# v1_0.net
KiCad netlist of a schematic drawn in EAGLE
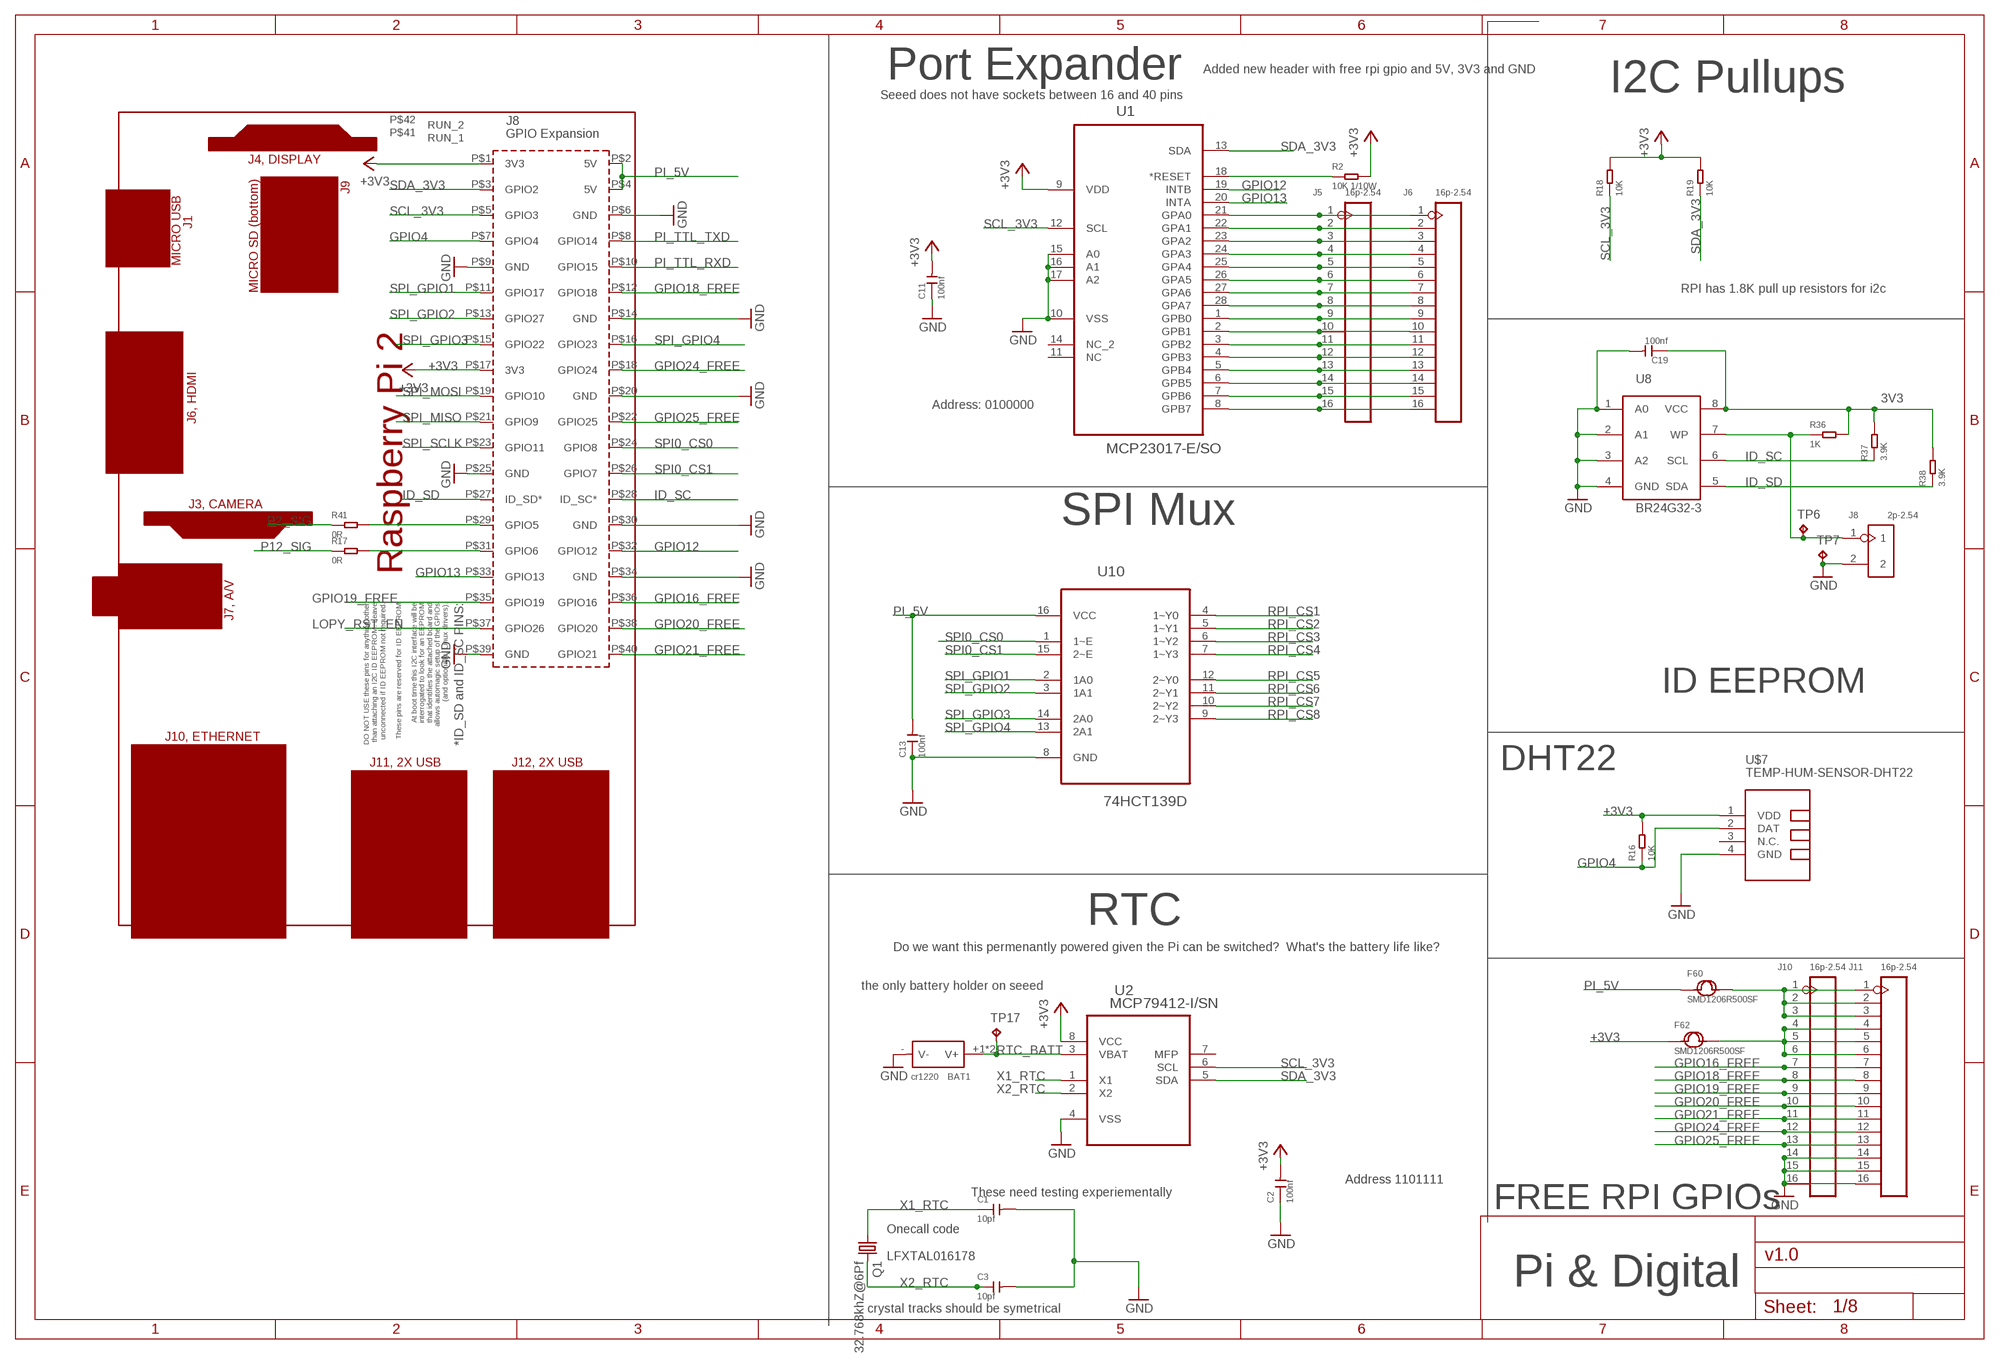
[diagram p0: schematic, sheet 1]
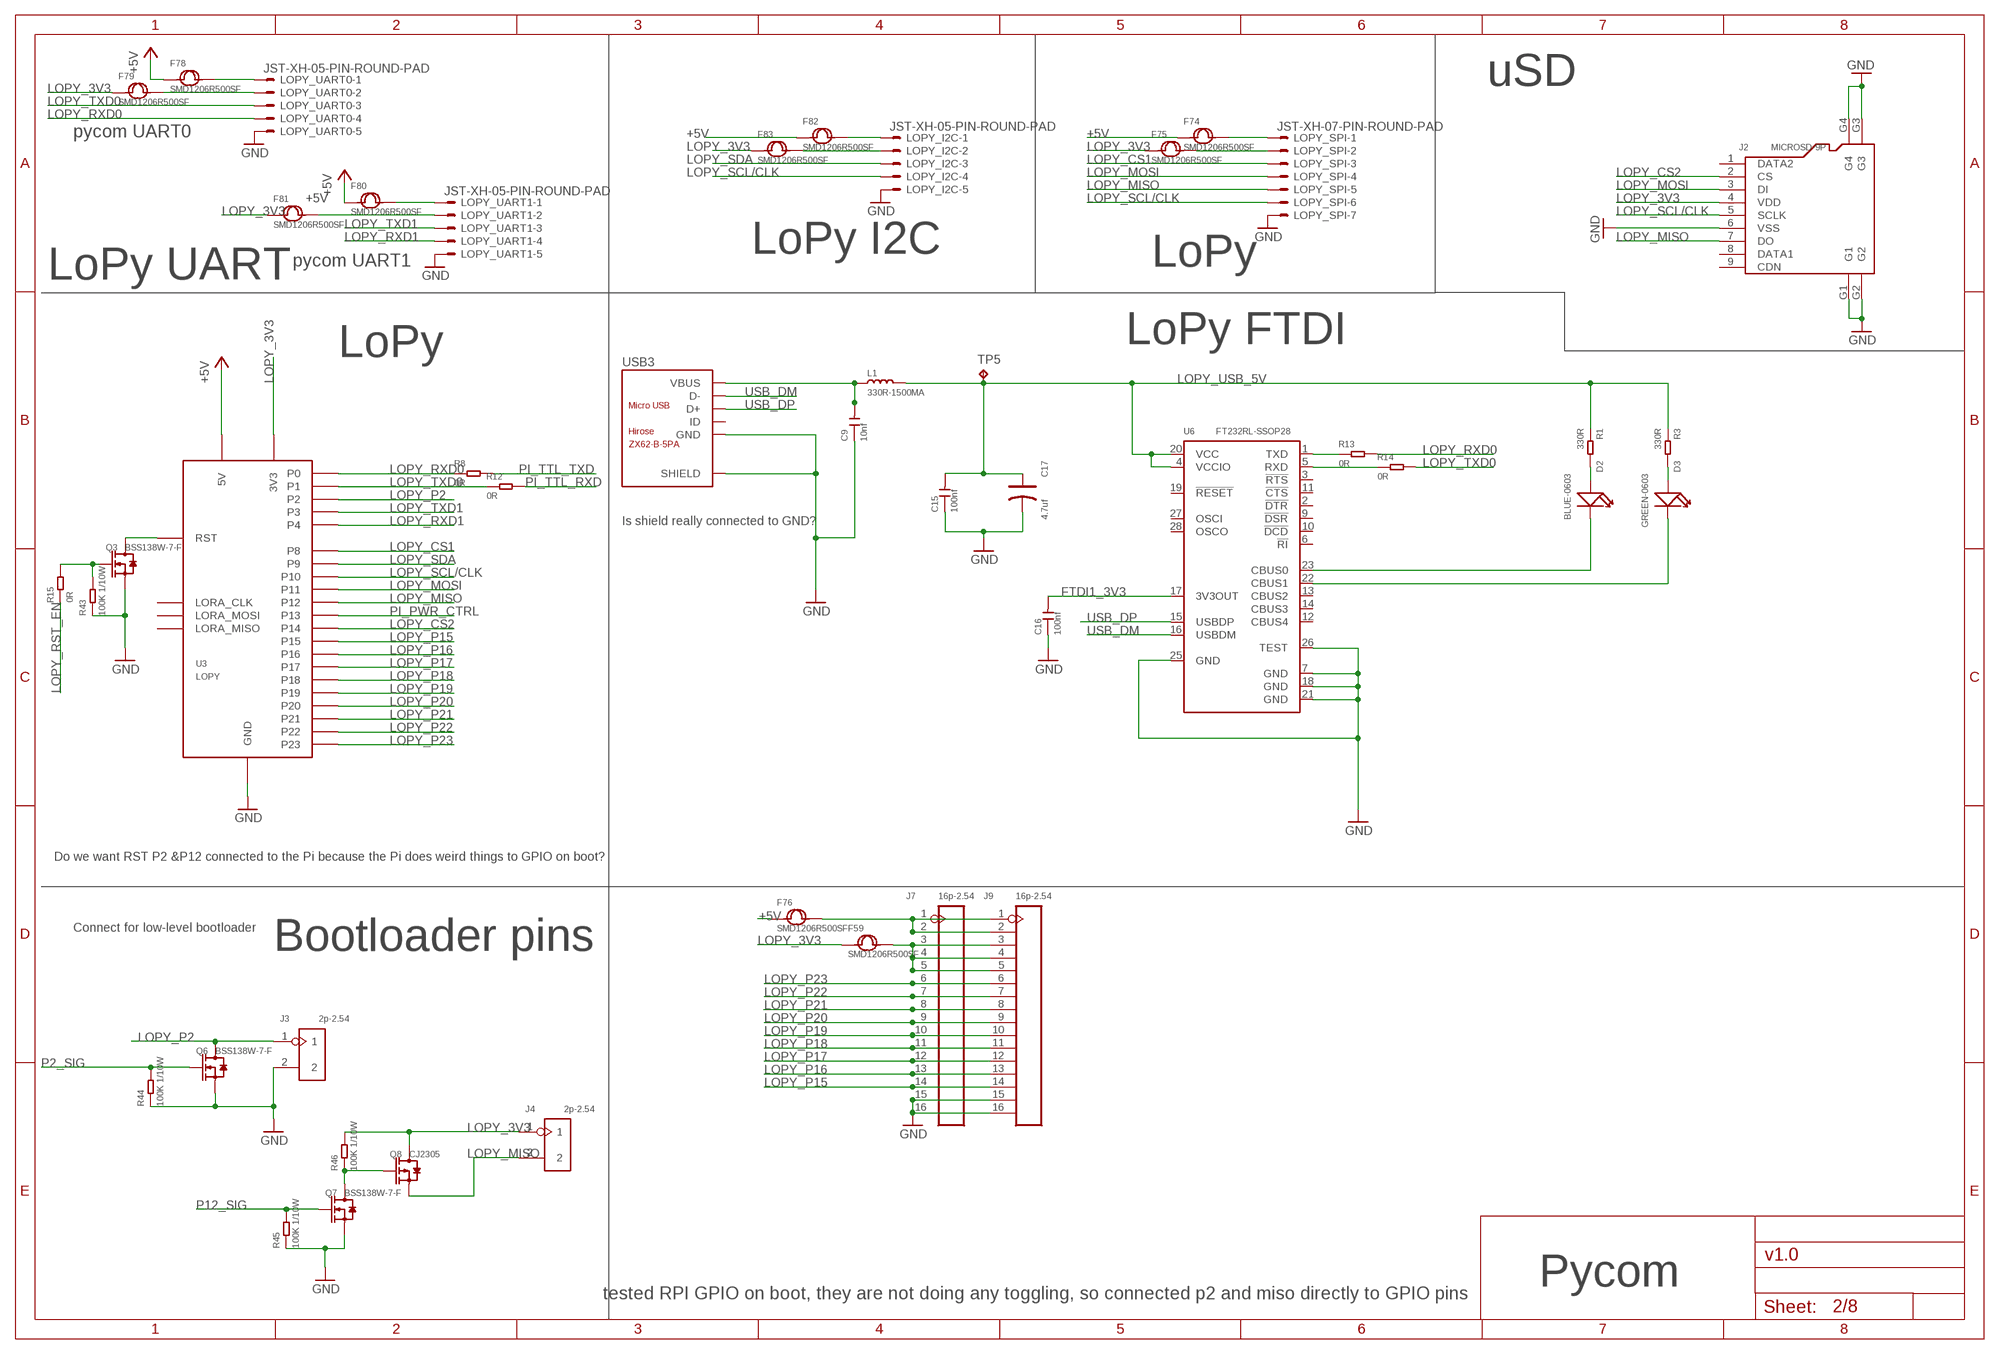
[diagram p1: schematic, sheet 2]
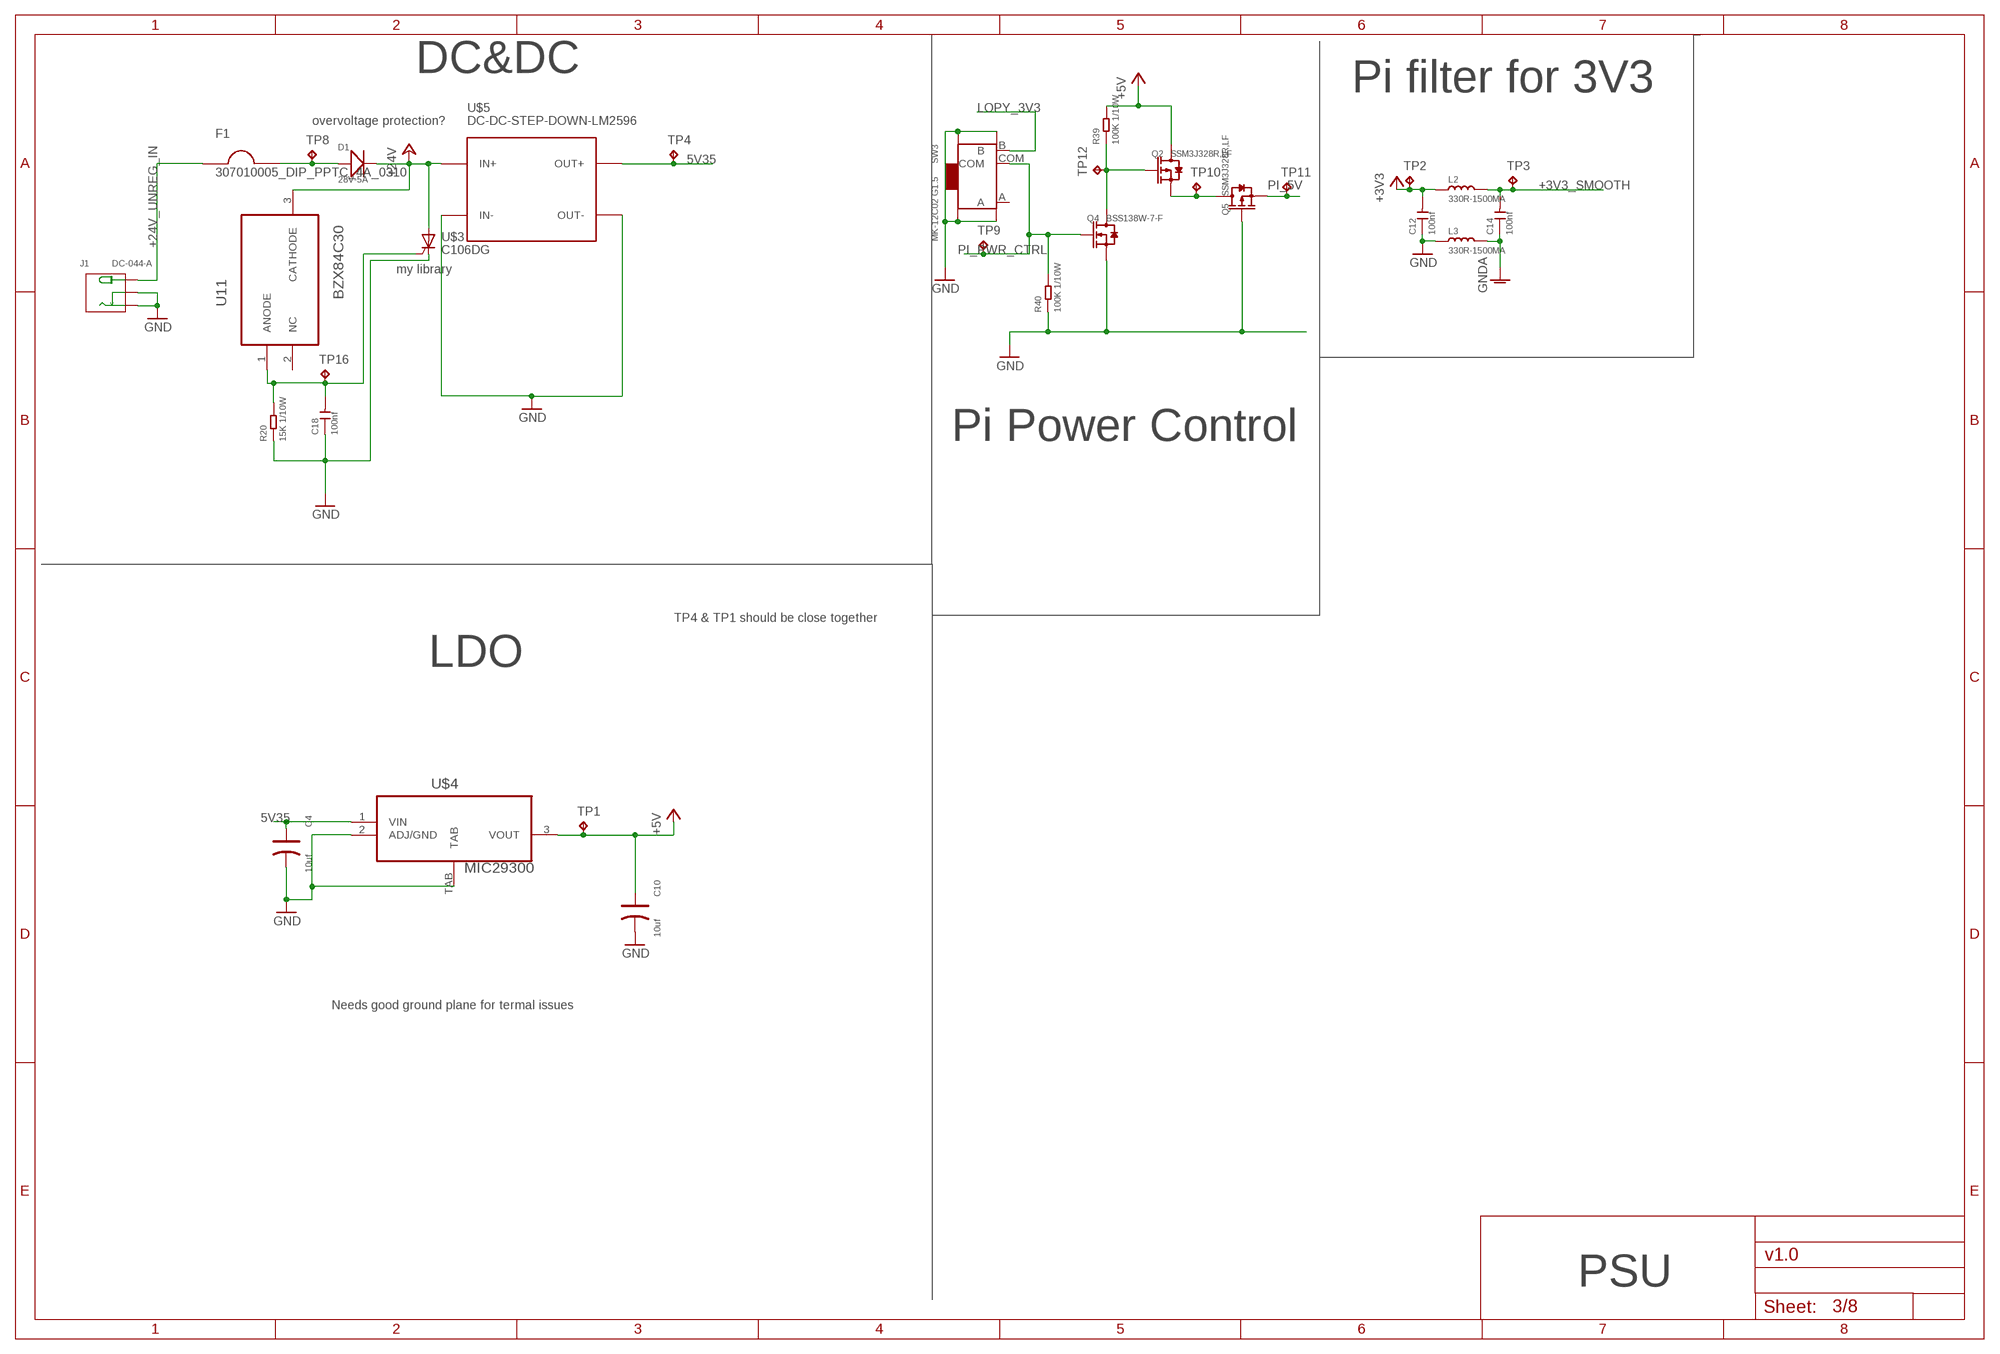
[diagram p2: schematic, sheet 3]
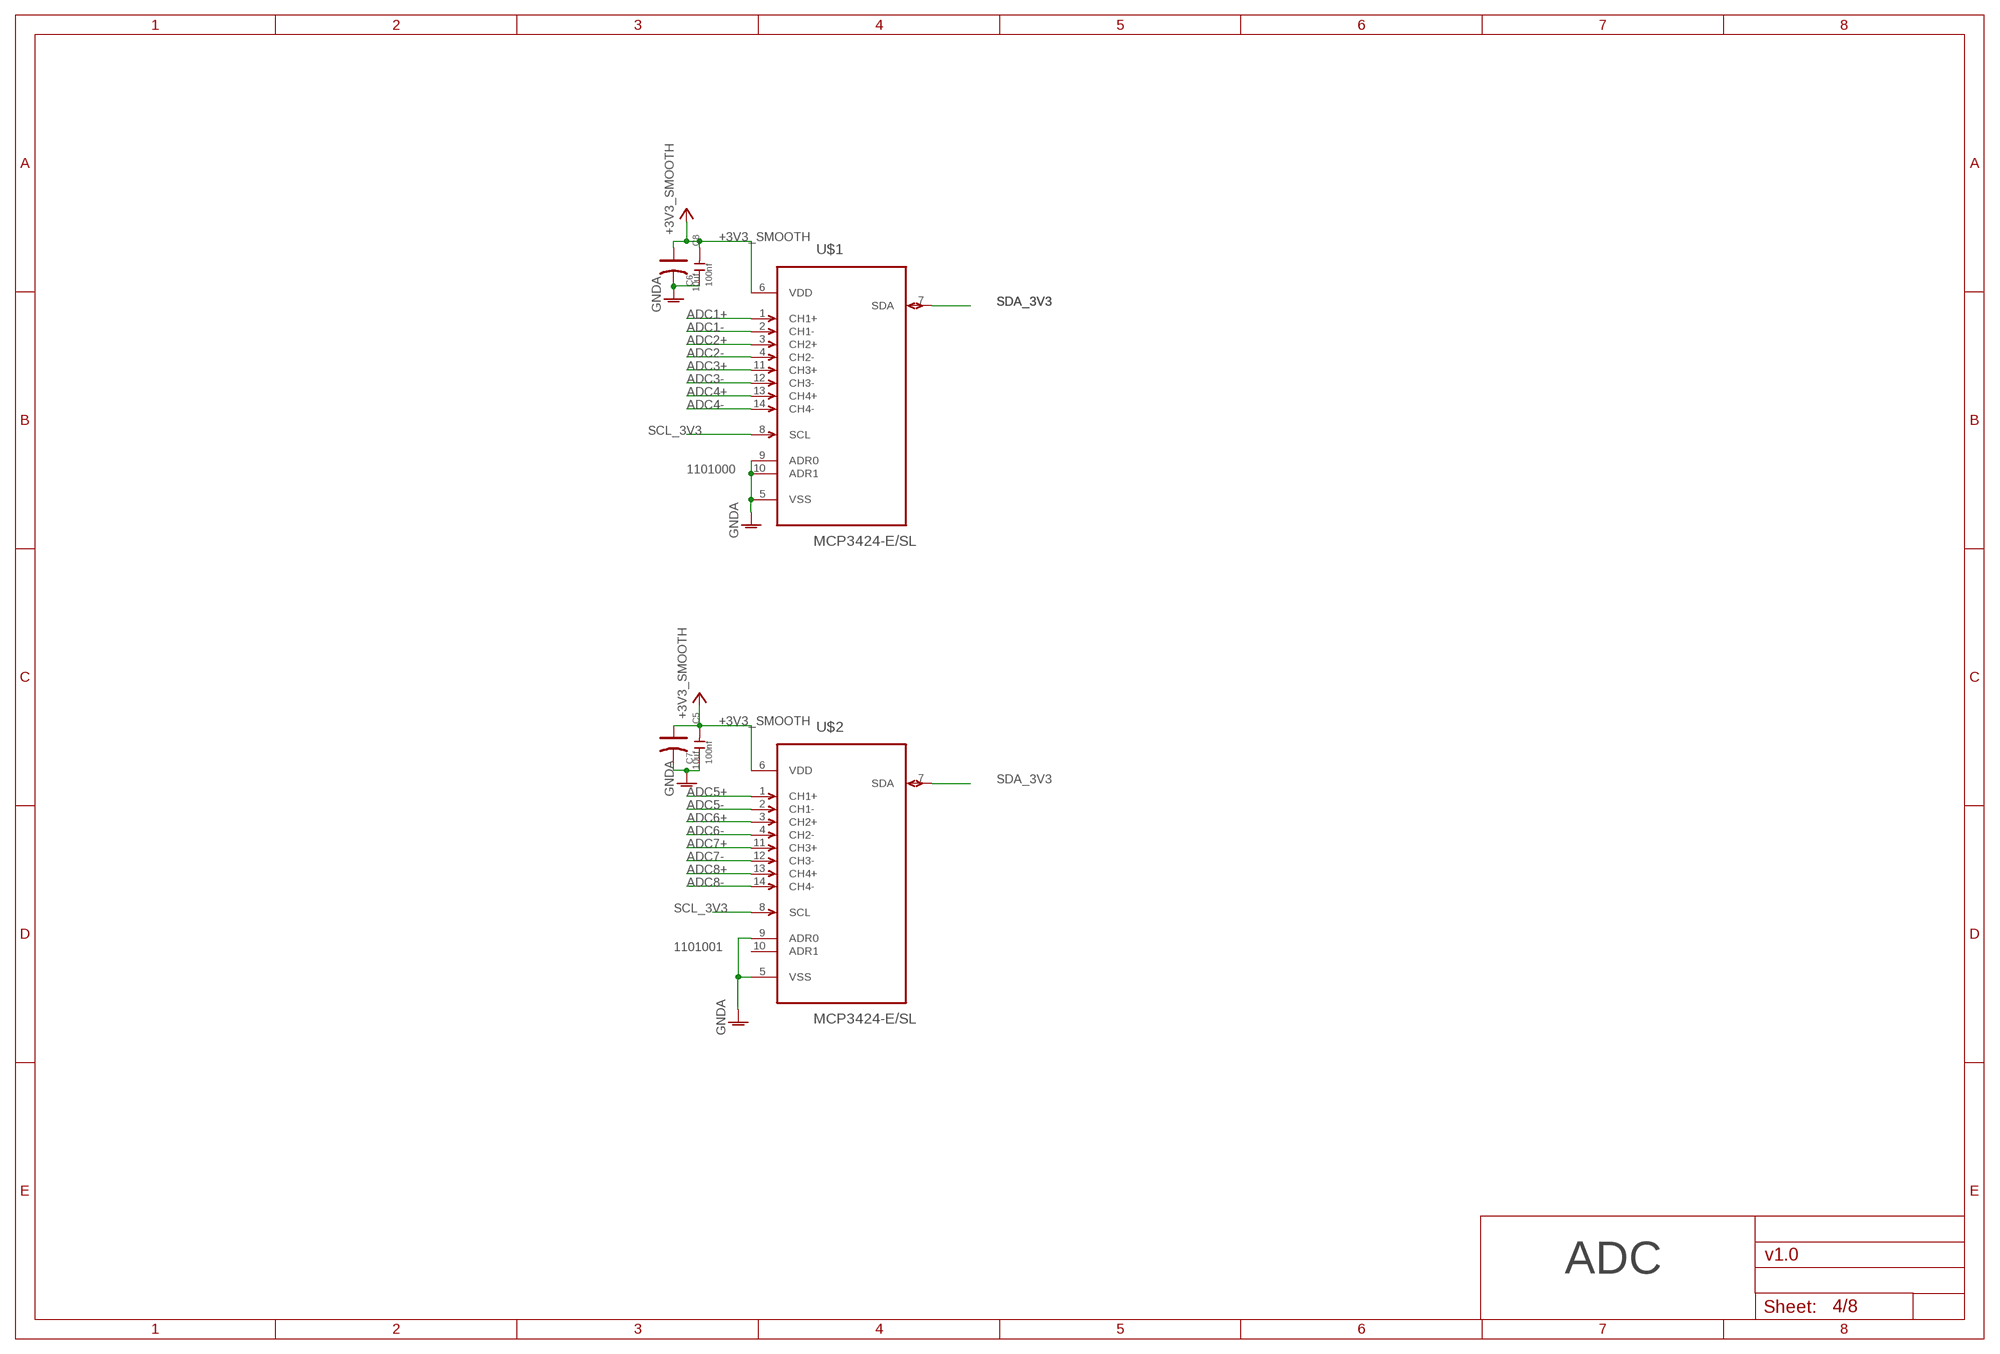
[diagram p3: schematic, sheet 4]
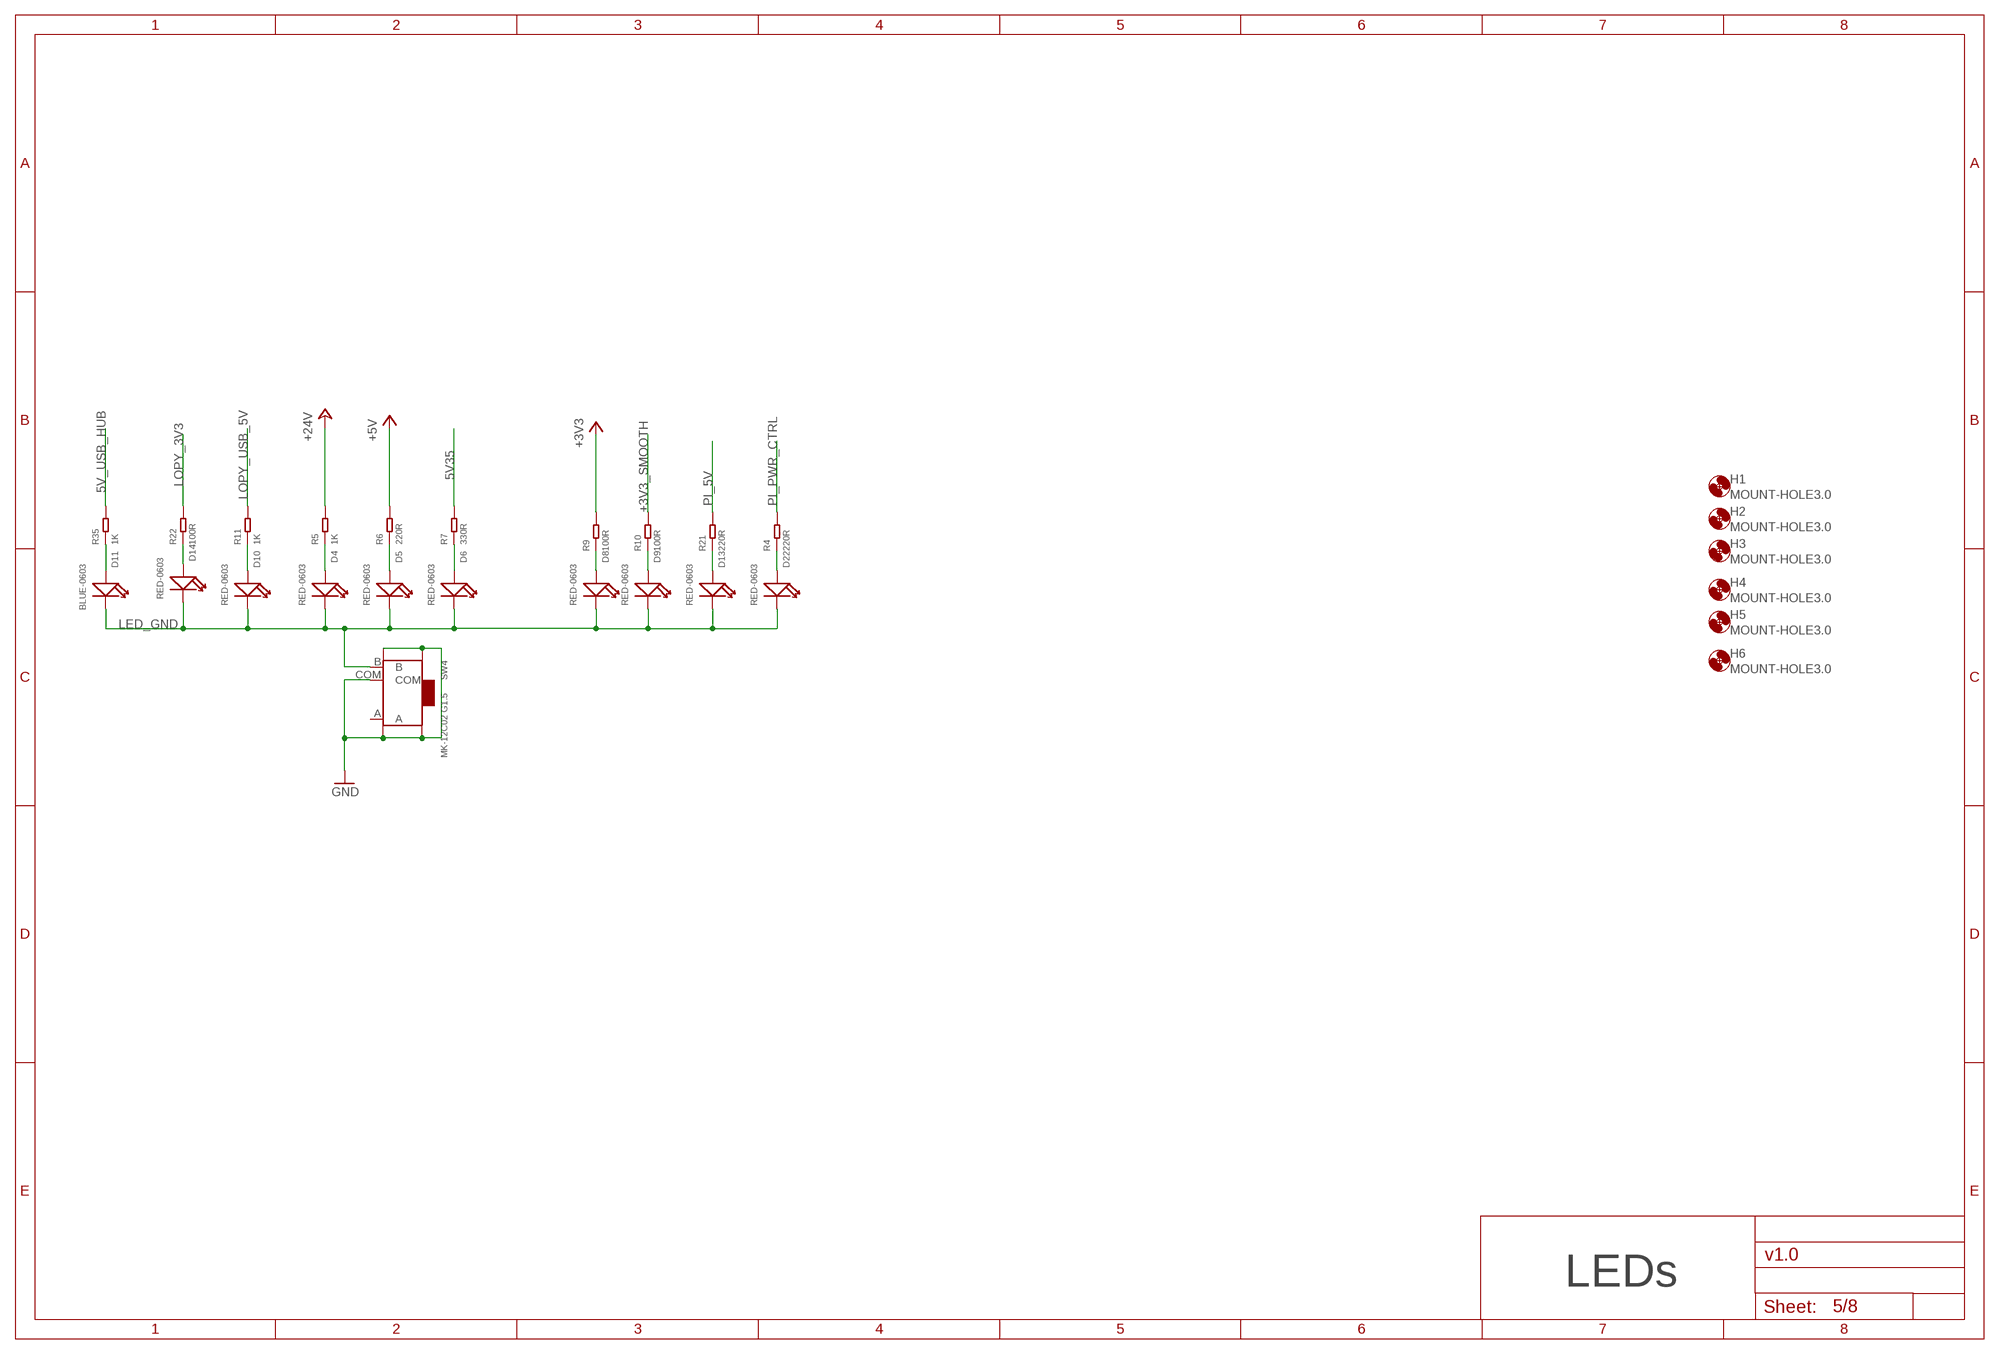
[diagram p4: schematic, sheet 5]
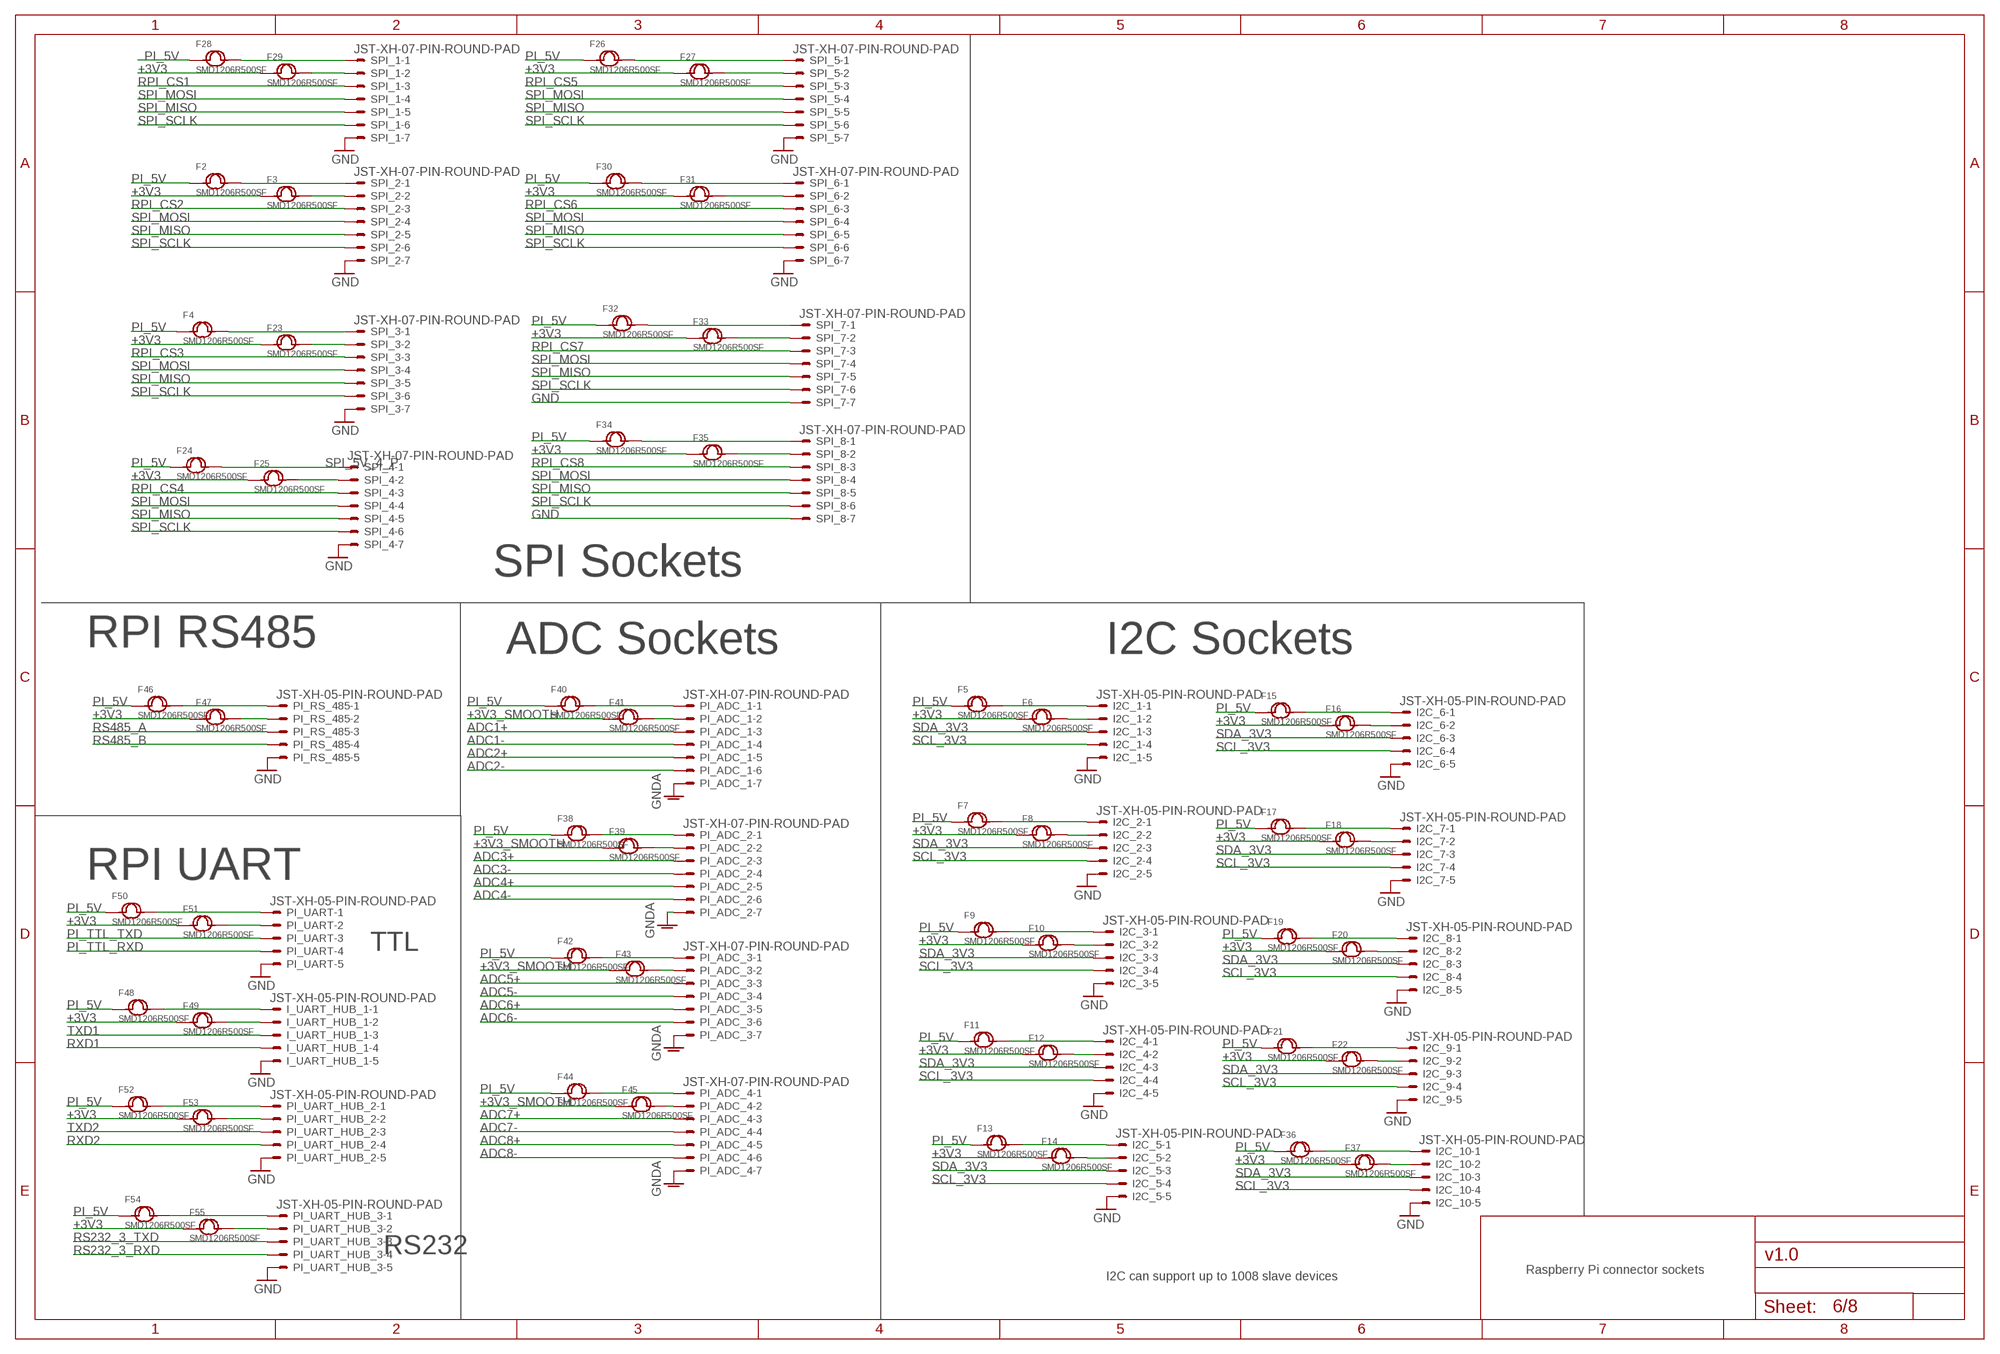
[diagram p5: schematic, sheet 6]
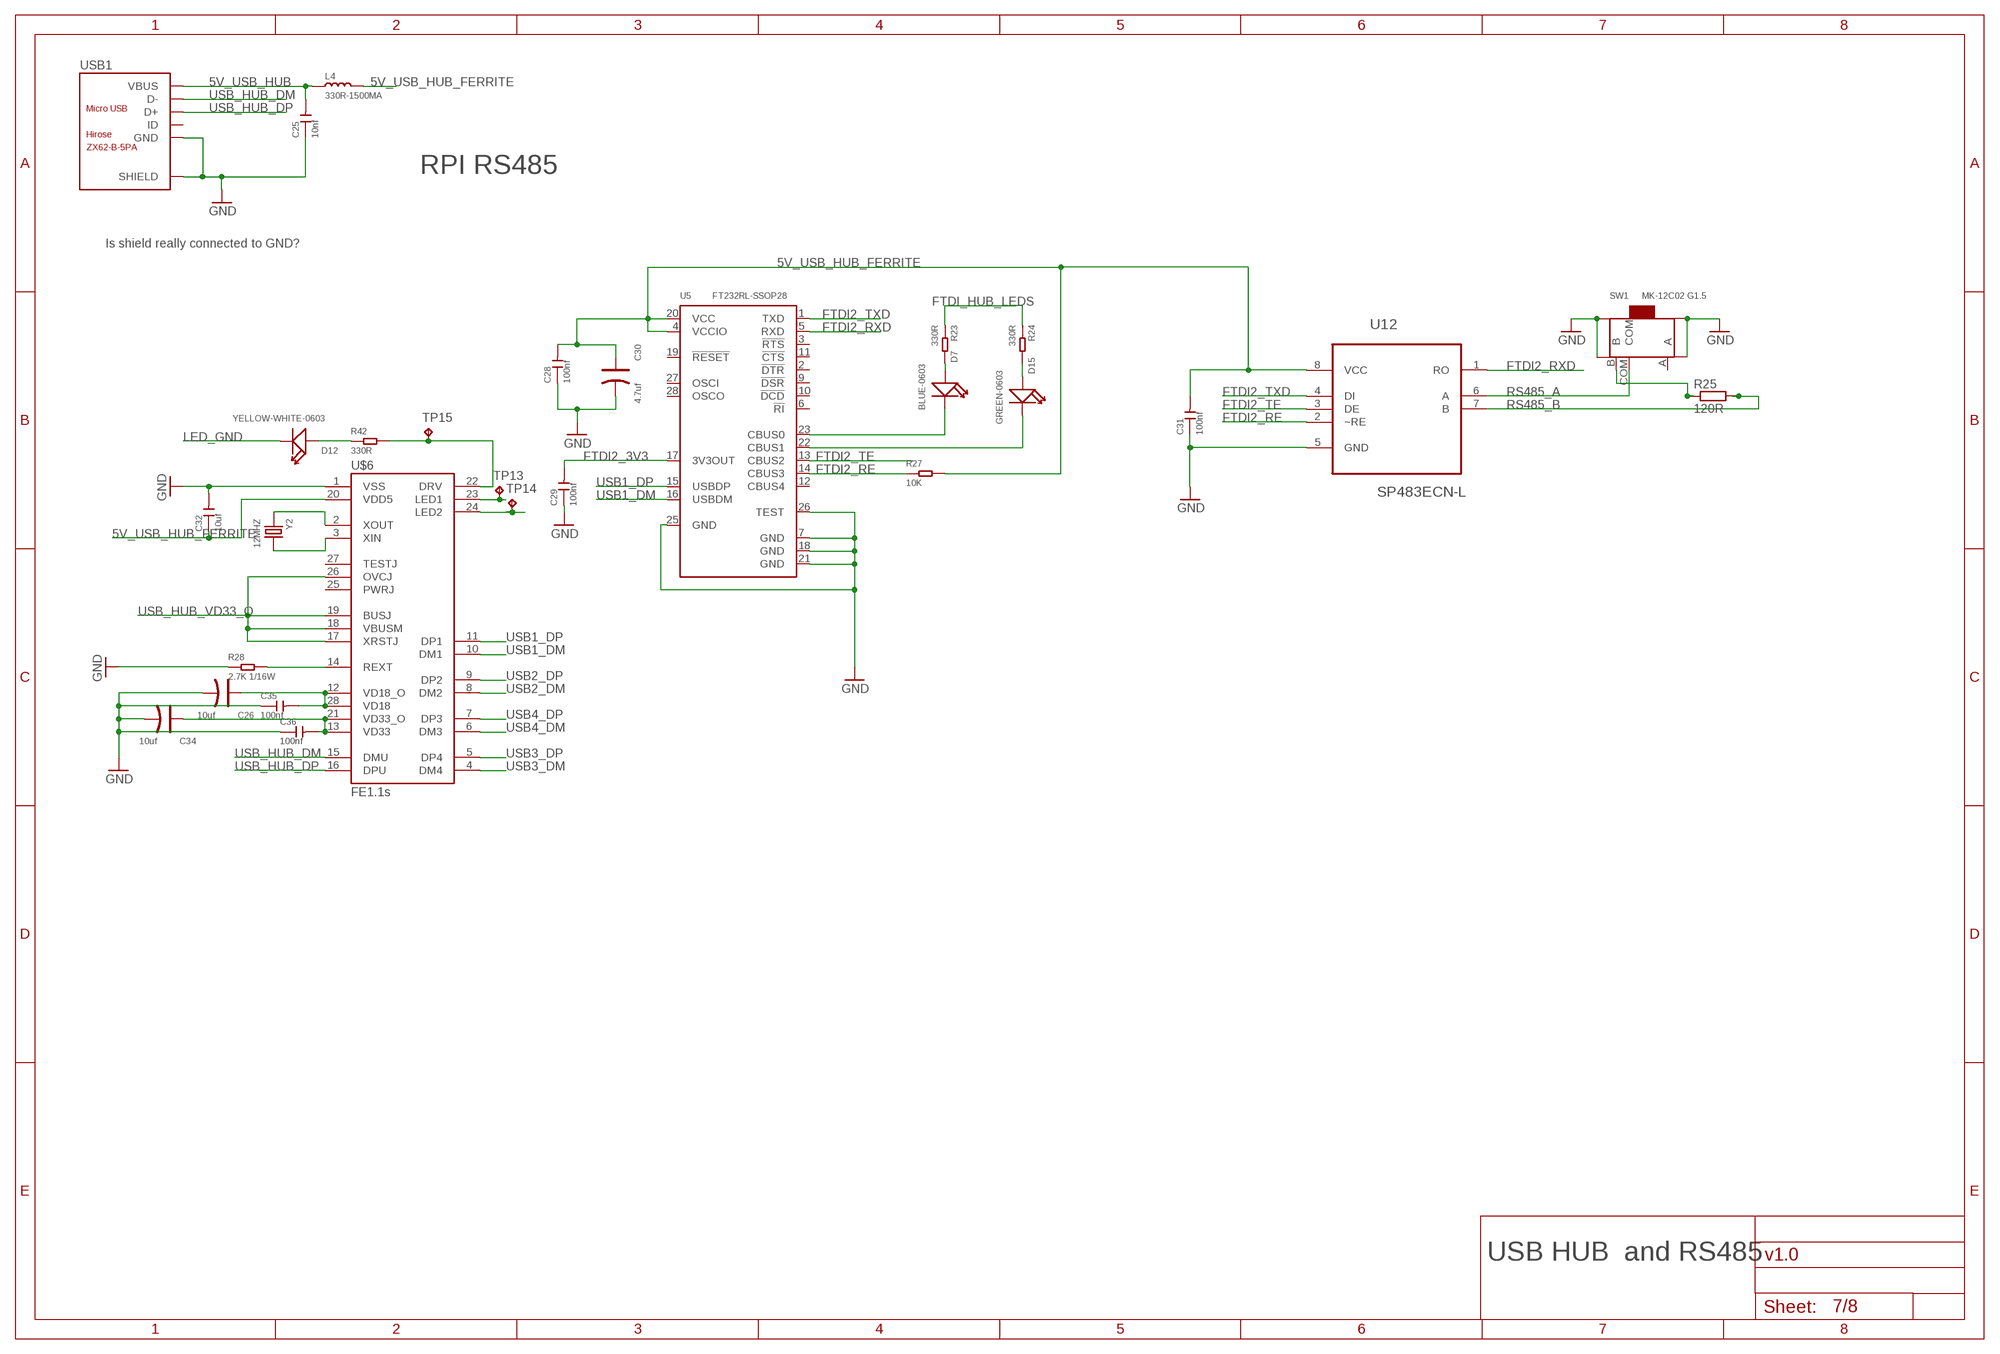
[diagram p6: schematic, sheet 7]
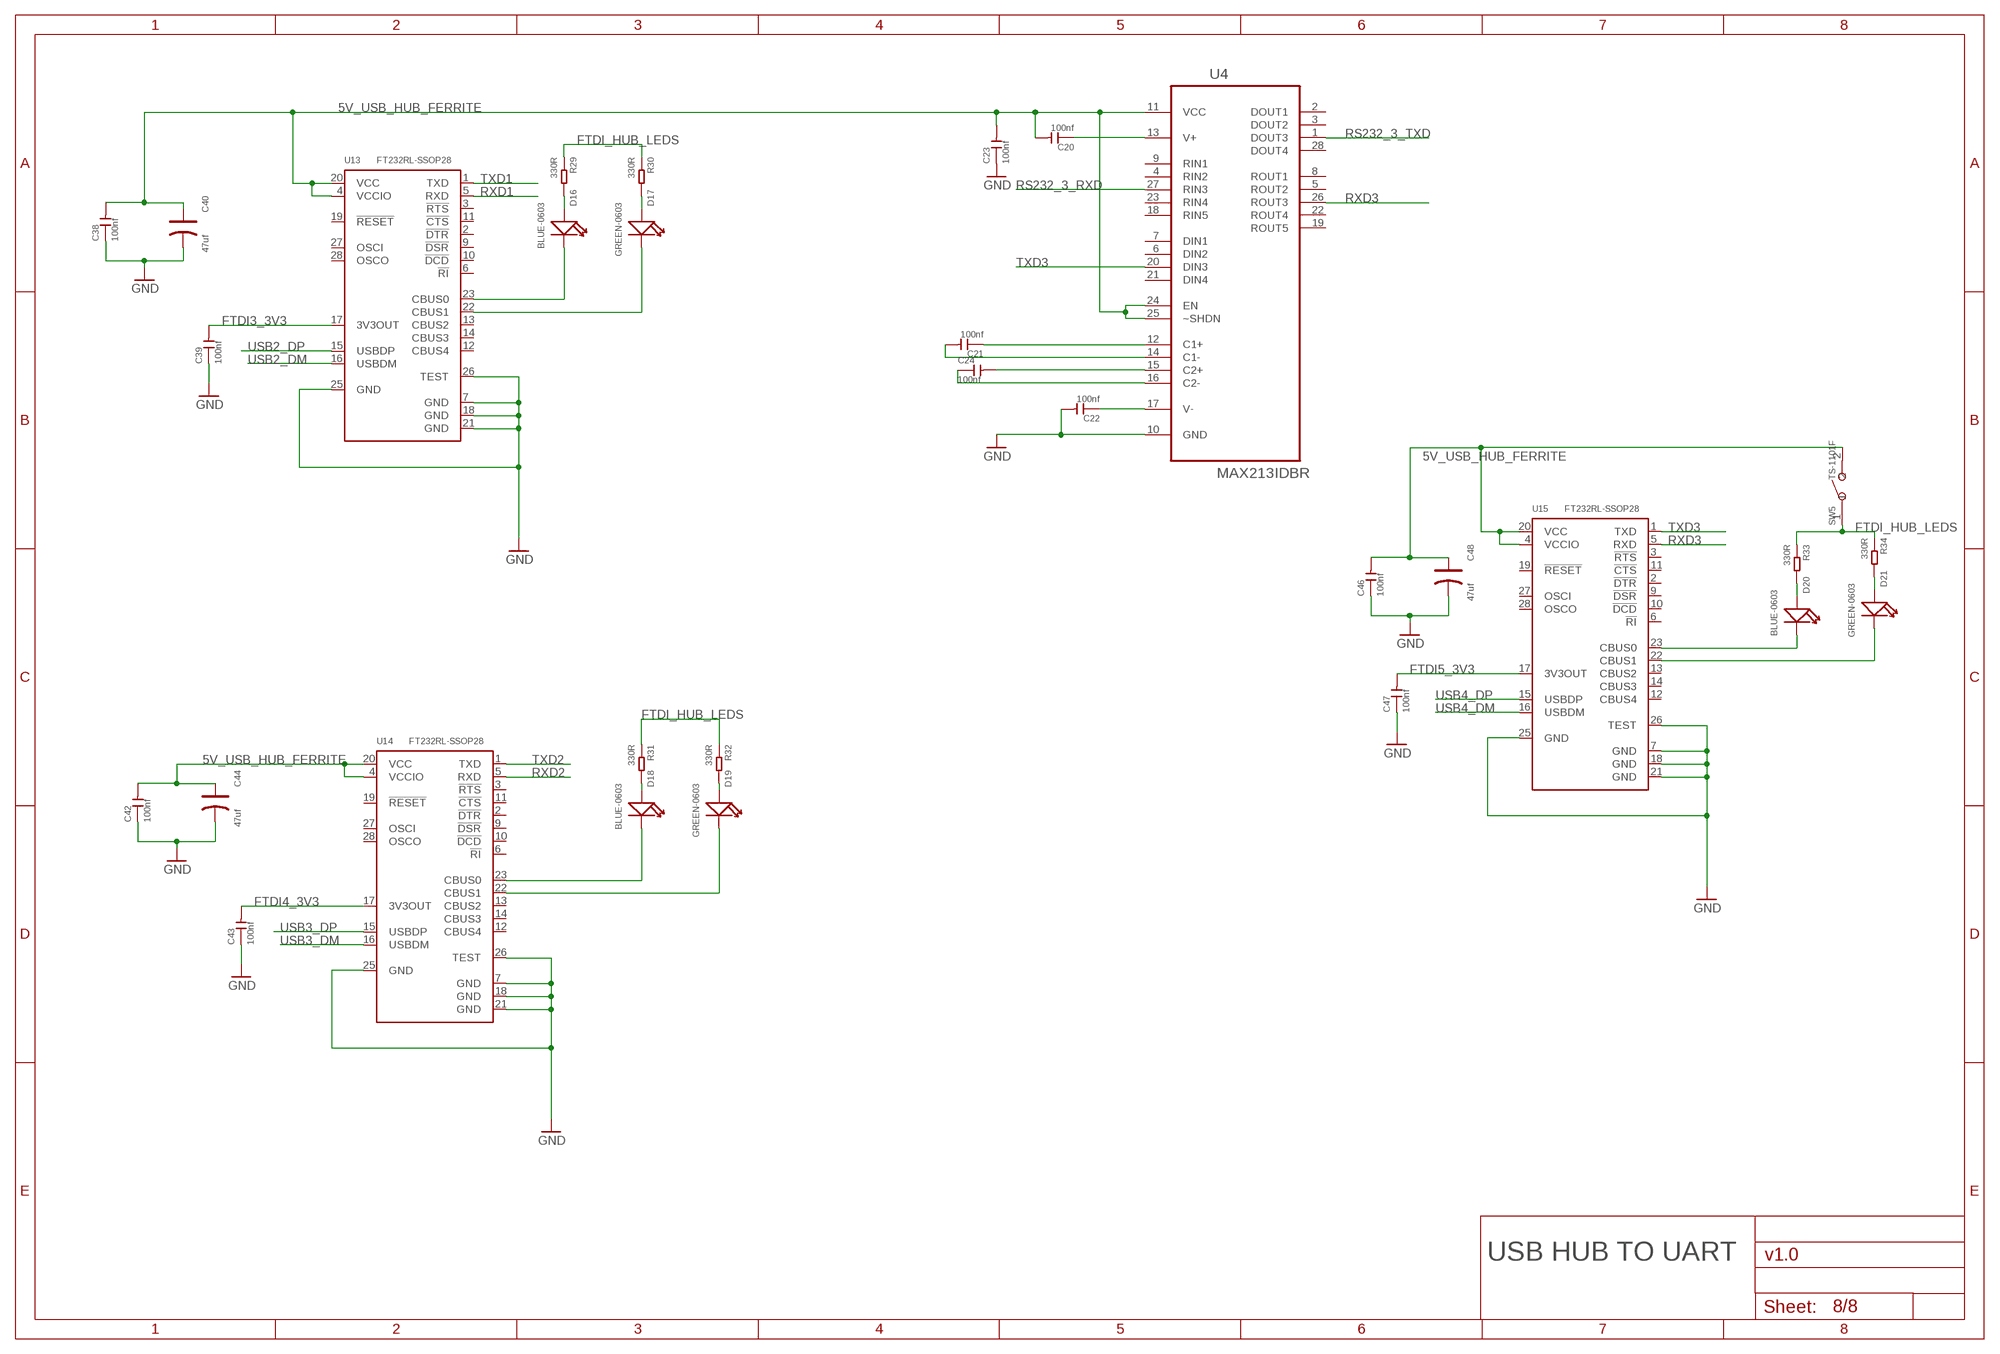
[diagram p7: schematic, sheet 8]

(export (version "E")
  (design (tool "Eeschema 10.0.6"))
  (components
    (comp (ref "D4")
      (value "RED-0603")
      (footprint "eagle-import:LED-0603")
      (fields (field (name "MPN") "19-217-R6C-AL1M2VY-3T"))
      (libsource (lib "eagle-import") (part "LED-SMD-RED-DIFFUSED(0603)"))
    )
    (comp (ref "D5")
      (value "RED-0603")
      (footprint "eagle-import:LED-0603")
      (fields (field (name "MPN") "19-217-R6C-AL1M2VY-3T"))
      (libsource (lib "eagle-import") (part "LED-SMD-RED-DIFFUSED(0603)"))
    )
    (comp (ref "D6")
      (value "RED-0603")
      (footprint "eagle-import:LED-0603")
      (fields (field (name "MPN") "19-217-R6C-AL1M2VY-3T"))
      (libsource (lib "eagle-import") (part "LED-SMD-RED-DIFFUSED(0603)"))
    )
    (comp (ref "D8")
      (value "RED-0603")
      (footprint "eagle-import:LED-0603")
      (fields (field (name "MPN") "19-217-R6C-AL1M2VY-3T"))
      (libsource (lib "eagle-import") (part "LED-SMD-RED-DIFFUSED(0603)"))
    )
    (comp (ref "D9")
      (value "RED-0603")
      (footprint "eagle-import:LED-0603")
      (fields (field (name "MPN") "19-217-R6C-AL1M2VY-3T"))
      (libsource (lib "eagle-import") (part "LED-SMD-RED-DIFFUSED(0603)"))
    )
    (comp (ref "D10")
      (value "RED-0603")
      (footprint "eagle-import:LED-0603")
      (fields (field (name "MPN") "19-217-R6C-AL1M2VY-3T"))
      (libsource (lib "eagle-import") (part "LED-SMD-RED-DIFFUSED(0603)"))
    )
    (comp (ref "D11")
      (value "BLUE-0603")
      (footprint "eagle-import:LED-0603")
      (fields (field (name "MPN") "19-217-BHC-ZL1M2RY-3T"))
      (libsource (lib "eagle-import") (part "SMD-LED-CLEAR-BLUE(0603)"))
    )
    (comp (ref "D13")
      (value "RED-0603")
      (footprint "eagle-import:LED-0603")
      (fields (field (name "MPN") "19-217-R6C-AL1M2VY-3T"))
      (libsource (lib "eagle-import") (part "LED-SMD-RED-DIFFUSED(0603)"))
    )
    (comp (ref "D14")
      (value "RED-0603")
      (footprint "eagle-import:LED-0603")
      (fields (field (name "MPN") "19-217-R6C-AL1M2VY-3T"))
      (libsource (lib "eagle-import") (part "LED-SMD-RED-DIFFUSED(0603)"))
    )
    (comp (ref "D22")
      (value "RED-0603")
      (footprint "eagle-import:LED-0603")
      (fields (field (name "MPN") "19-217-R6C-AL1M2VY-3T"))
      (libsource (lib "eagle-import") (part "LED-SMD-RED-DIFFUSED(0603)"))
    )
    (comp (ref "H1")
      (value "MOUNT-HOLE3.0")
      (footprint "eagle-import:3,0")
      (libsource (lib "eagle-import") (part "MOUNT-HOLE3.0"))
    )
    (comp (ref "H2")
      (value "MOUNT-HOLE3.0")
      (footprint "eagle-import:3,0")
      (libsource (lib "eagle-import") (part "MOUNT-HOLE3.0"))
    )
    (comp (ref "H3")
      (value "MOUNT-HOLE3.0")
      (footprint "eagle-import:3,0")
      (libsource (lib "eagle-import") (part "MOUNT-HOLE3.0"))
    )
    (comp (ref "H4")
      (value "MOUNT-HOLE3.0")
      (footprint "eagle-import:3,0")
      (libsource (lib "eagle-import") (part "MOUNT-HOLE3.0"))
    )
    (comp (ref "H5")
      (value "MOUNT-HOLE3.0")
      (footprint "eagle-import:3,0")
      (libsource (lib "eagle-import") (part "MOUNT-HOLE3.0"))
    )
    (comp (ref "H6")
      (value "MOUNT-HOLE3.0")
      (footprint "eagle-import:3,0")
      (libsource (lib "eagle-import") (part "MOUNT-HOLE3.0"))
    )
    (comp (ref "R4")
      (value "220R")
      (footprint "eagle-import:R0603")
      (fields (field (name "MPN") "RC0603JR-07220RL"))
      (libsource (lib "eagle-import") (part "SMD-RES-220R-5%-1/10W(0603)"))
    )
    (comp (ref "R5")
      (value "1K")
      (footprint "eagle-import:R0603")
      (fields (field (name "MPN") "RC0603FR-071KL"))
      (libsource (lib "eagle-import") (part "SMD-RES-1K-1%-1/10W(0603)"))
    )
    (comp (ref "R6")
      (value "220R")
      (footprint "eagle-import:R0603")
      (fields (field (name "MPN") "RC0603JR-07220RL"))
      (libsource (lib "eagle-import") (part "SMD-RES-220R-5%-1/10W(0603)"))
    )
    (comp (ref "R7")
      (value "330R")
      (footprint "eagle-import:R0603")
      (fields (field (name "MPN") "RC0603FR-07330RL"))
      (libsource (lib "eagle-import") (part "Seeed-Resistor_474_SMD-RES-330R-1%-1/10W(0603)"))
    )
    (comp (ref "R9")
      (value "100R")
      (footprint "eagle-import:R0603")
      (fields (field (name "MPN") "RC0603JR-07100RL"))
      (libsource (lib "eagle-import") (part "SMD-RES-100R-5%-1/10W(0603)"))
    )
    (comp (ref "R10")
      (value "100R")
      (footprint "eagle-import:R0603")
      (fields (field (name "MPN") "RC0603JR-07100RL"))
      (libsource (lib "eagle-import") (part "SMD-RES-100R-5%-1/10W(0603)"))
    )
    (comp (ref "R11")
      (value "1K")
      (footprint "eagle-import:R0603")
      (fields (field (name "MPN") "RC0603FR-071KL"))
      (libsource (lib "eagle-import") (part "SMD-RES-1K-1%-1/10W(0603)"))
    )
    (comp (ref "R21")
      (value "220R")
      (footprint "eagle-import:R0603")
      (fields (field (name "MPN") "RC0603JR-07220RL"))
      (libsource (lib "eagle-import") (part "SMD-RES-220R-5%-1/10W(0603)"))
    )
    (comp (ref "R22")
      (value "100R")
      (footprint "eagle-import:R0603")
      (fields (field (name "MPN") "RC0603JR-07100RL"))
      (libsource (lib "eagle-import") (part "SMD-RES-100R-5%-1/10W(0603)"))
    )
    (comp (ref "R35")
      (value "1K")
      (footprint "eagle-import:R0603")
      (fields (field (name "MPN") "RC0603FR-071KL"))
      (libsource (lib "eagle-import") (part "SMD-RES-1K-1%-1/10W(0603)"))
    )
    (comp (ref "SW4")
      (value "MK-12C02 G1.5")
      (footprint "eagle-import:SW7-SMD-L6.7X2.7X3.2MM")
      (libsource (lib "eagle-import") (part "SMD-TOGGLE-SWITCH-ON-ON(3+4P-6.7X2.7MM)"))
    )
    (comp (ref "F2")
      (value "SMD1206R500SF")
      (footprint "eagle-import:F1206")
      (libsource (lib "eagle-import") (part "SMD-PPTC-500MA(1206)"))
    )
    (comp (ref "F3")
      (value "SMD1206R500SF")
      (footprint "eagle-import:F1206")
      (libsource (lib "eagle-import") (part "SMD-PPTC-500MA(1206)"))
    )
    (comp (ref "F4")
      (value "SMD1206R500SF")
      (footprint "eagle-import:F1206")
      (libsource (lib "eagle-import") (part "SMD-PPTC-500MA(1206)"))
    )
    (comp (ref "F5")
      (value "SMD1206R500SF")
      (footprint "eagle-import:F1206")
      (libsource (lib "eagle-import") (part "SMD-PPTC-500MA(1206)"))
    )
    (comp (ref "F6")
      (value "SMD1206R500SF")
      (footprint "eagle-import:F1206")
      (libsource (lib "eagle-import") (part "SMD-PPTC-500MA(1206)"))
    )
    (comp (ref "F7")
      (value "SMD1206R500SF")
      (footprint "eagle-import:F1206")
      (libsource (lib "eagle-import") (part "SMD-PPTC-500MA(1206)"))
    )
    (comp (ref "F8")
      (value "SMD1206R500SF")
      (footprint "eagle-import:F1206")
      (libsource (lib "eagle-import") (part "SMD-PPTC-500MA(1206)"))
    )
    (comp (ref "F9")
      (value "SMD1206R500SF")
      (footprint "eagle-import:F1206")
      (libsource (lib "eagle-import") (part "SMD-PPTC-500MA(1206)"))
    )
    (comp (ref "F10")
      (value "SMD1206R500SF")
      (footprint "eagle-import:F1206")
      (libsource (lib "eagle-import") (part "SMD-PPTC-500MA(1206)"))
    )
    (comp (ref "F11")
      (value "SMD1206R500SF")
      (footprint "eagle-import:F1206")
      (libsource (lib "eagle-import") (part "SMD-PPTC-500MA(1206)"))
    )
    (comp (ref "F12")
      (value "SMD1206R500SF")
      (footprint "eagle-import:F1206")
      (libsource (lib "eagle-import") (part "SMD-PPTC-500MA(1206)"))
    )
    (comp (ref "F13")
      (value "SMD1206R500SF")
      (footprint "eagle-import:F1206")
      (libsource (lib "eagle-import") (part "SMD-PPTC-500MA(1206)"))
    )
    (comp (ref "F14")
      (value "SMD1206R500SF")
      (footprint "eagle-import:F1206")
      (libsource (lib "eagle-import") (part "SMD-PPTC-500MA(1206)"))
    )
    (comp (ref "F15")
      (value "SMD1206R500SF")
      (footprint "eagle-import:F1206")
      (libsource (lib "eagle-import") (part "SMD-PPTC-500MA(1206)"))
    )
    (comp (ref "F16")
      (value "SMD1206R500SF")
      (footprint "eagle-import:F1206")
      (libsource (lib "eagle-import") (part "SMD-PPTC-500MA(1206)"))
    )
    (comp (ref "F17")
      (value "SMD1206R500SF")
      (footprint "eagle-import:F1206")
      (libsource (lib "eagle-import") (part "SMD-PPTC-500MA(1206)"))
    )
    (comp (ref "F18")
      (value "SMD1206R500SF")
      (footprint "eagle-import:F1206")
      (libsource (lib "eagle-import") (part "SMD-PPTC-500MA(1206)"))
    )
    (comp (ref "F19")
      (value "SMD1206R500SF")
      (footprint "eagle-import:F1206")
      (libsource (lib "eagle-import") (part "SMD-PPTC-500MA(1206)"))
    )
    (comp (ref "F20")
      (value "SMD1206R500SF")
      (footprint "eagle-import:F1206")
      (libsource (lib "eagle-import") (part "SMD-PPTC-500MA(1206)"))
    )
    (comp (ref "F21")
      (value "SMD1206R500SF")
      (footprint "eagle-import:F1206")
      (libsource (lib "eagle-import") (part "SMD-PPTC-500MA(1206)"))
    )
    (comp (ref "F22")
      (value "SMD1206R500SF")
      (footprint "eagle-import:F1206")
      (libsource (lib "eagle-import") (part "SMD-PPTC-500MA(1206)"))
    )
    (comp (ref "F23")
      (value "SMD1206R500SF")
      (footprint "eagle-import:F1206")
      (libsource (lib "eagle-import") (part "SMD-PPTC-500MA(1206)"))
    )
    (comp (ref "F24")
      (value "SMD1206R500SF")
      (footprint "eagle-import:F1206")
      (libsource (lib "eagle-import") (part "SMD-PPTC-500MA(1206)"))
    )
    (comp (ref "F25")
      (value "SMD1206R500SF")
      (footprint "eagle-import:F1206")
      (libsource (lib "eagle-import") (part "SMD-PPTC-500MA(1206)"))
    )
    (comp (ref "F26")
      (value "SMD1206R500SF")
      (footprint "eagle-import:F1206")
      (libsource (lib "eagle-import") (part "SMD-PPTC-500MA(1206)"))
    )
    (comp (ref "F27")
      (value "SMD1206R500SF")
      (footprint "eagle-import:F1206")
      (libsource (lib "eagle-import") (part "SMD-PPTC-500MA(1206)"))
    )
    (comp (ref "F28")
      (value "SMD1206R500SF")
      (footprint "eagle-import:F1206")
      (libsource (lib "eagle-import") (part "SMD-PPTC-500MA(1206)"))
    )
    (comp (ref "F29")
      (value "SMD1206R500SF")
      (footprint "eagle-import:F1206")
      (libsource (lib "eagle-import") (part "SMD-PPTC-500MA(1206)"))
    )
    (comp (ref "F30")
      (value "SMD1206R500SF")
      (footprint "eagle-import:F1206")
      (libsource (lib "eagle-import") (part "SMD-PPTC-500MA(1206)"))
    )
    (comp (ref "F31")
      (value "SMD1206R500SF")
      (footprint "eagle-import:F1206")
      (libsource (lib "eagle-import") (part "SMD-PPTC-500MA(1206)"))
    )
    (comp (ref "F32")
      (value "SMD1206R500SF")
      (footprint "eagle-import:F1206")
      (libsource (lib "eagle-import") (part "SMD-PPTC-500MA(1206)"))
    )
    (comp (ref "F33")
      (value "SMD1206R500SF")
      (footprint "eagle-import:F1206")
      (libsource (lib "eagle-import") (part "SMD-PPTC-500MA(1206)"))
    )
    (comp (ref "F34")
      (value "SMD1206R500SF")
      (footprint "eagle-import:F1206")
      (libsource (lib "eagle-import") (part "SMD-PPTC-500MA(1206)"))
    )
    (comp (ref "F35")
      (value "SMD1206R500SF")
      (footprint "eagle-import:F1206")
      (libsource (lib "eagle-import") (part "SMD-PPTC-500MA(1206)"))
    )
    (comp (ref "F36")
      (value "SMD1206R500SF")
      (footprint "eagle-import:F1206")
      (libsource (lib "eagle-import") (part "SMD-PPTC-500MA(1206)"))
    )
    (comp (ref "F37")
      (value "SMD1206R500SF")
      (footprint "eagle-import:F1206")
      (libsource (lib "eagle-import") (part "SMD-PPTC-500MA(1206)"))
    )
    (comp (ref "F38")
      (value "SMD1206R500SF")
      (footprint "eagle-import:F1206")
      (libsource (lib "eagle-import") (part "SMD-PPTC-500MA(1206)"))
    )
    (comp (ref "F39")
      (value "SMD1206R500SF")
      (footprint "eagle-import:F1206")
      (libsource (lib "eagle-import") (part "SMD-PPTC-500MA(1206)"))
    )
    (comp (ref "F40")
      (value "SMD1206R500SF")
      (footprint "eagle-import:F1206")
      (libsource (lib "eagle-import") (part "SMD-PPTC-500MA(1206)"))
    )
    (comp (ref "F41")
      (value "SMD1206R500SF")
      (footprint "eagle-import:F1206")
      (libsource (lib "eagle-import") (part "SMD-PPTC-500MA(1206)"))
    )
    (comp (ref "F42")
      (value "SMD1206R500SF")
      (footprint "eagle-import:F1206")
      (libsource (lib "eagle-import") (part "SMD-PPTC-500MA(1206)"))
    )
    (comp (ref "F43")
      (value "SMD1206R500SF")
      (footprint "eagle-import:F1206")
      (libsource (lib "eagle-import") (part "SMD-PPTC-500MA(1206)"))
    )
    (comp (ref "F44")
      (value "SMD1206R500SF")
      (footprint "eagle-import:F1206")
      (libsource (lib "eagle-import") (part "SMD-PPTC-500MA(1206)"))
    )
    (comp (ref "F45")
      (value "SMD1206R500SF")
      (footprint "eagle-import:F1206")
      (libsource (lib "eagle-import") (part "SMD-PPTC-500MA(1206)"))
    )
    (comp (ref "F46")
      (value "SMD1206R500SF")
      (footprint "eagle-import:F1206")
      (libsource (lib "eagle-import") (part "SMD-PPTC-500MA(1206)"))
    )
    (comp (ref "F47")
      (value "SMD1206R500SF")
      (footprint "eagle-import:F1206")
      (libsource (lib "eagle-import") (part "SMD-PPTC-500MA(1206)"))
    )
    (comp (ref "F48")
      (value "SMD1206R500SF")
      (footprint "eagle-import:F1206")
      (libsource (lib "eagle-import") (part "SMD-PPTC-500MA(1206)"))
    )
    (comp (ref "F49")
      (value "SMD1206R500SF")
      (footprint "eagle-import:F1206")
      (libsource (lib "eagle-import") (part "SMD-PPTC-500MA(1206)"))
    )
    (comp (ref "F50")
      (value "SMD1206R500SF")
      (footprint "eagle-import:F1206")
      (libsource (lib "eagle-import") (part "SMD-PPTC-500MA(1206)"))
    )
    (comp (ref "F51")
      (value "SMD1206R500SF")
      (footprint "eagle-import:F1206")
      (libsource (lib "eagle-import") (part "SMD-PPTC-500MA(1206)"))
    )
    (comp (ref "F52")
      (value "SMD1206R500SF")
      (footprint "eagle-import:F1206")
      (libsource (lib "eagle-import") (part "SMD-PPTC-500MA(1206)"))
    )
    (comp (ref "F53")
      (value "SMD1206R500SF")
      (footprint "eagle-import:F1206")
      (libsource (lib "eagle-import") (part "SMD-PPTC-500MA(1206)"))
    )
    (comp (ref "F54")
      (value "SMD1206R500SF")
      (footprint "eagle-import:F1206")
      (libsource (lib "eagle-import") (part "SMD-PPTC-500MA(1206)"))
    )
    (comp (ref "F55")
      (value "SMD1206R500SF")
      (footprint "eagle-import:F1206")
      (libsource (lib "eagle-import") (part "SMD-PPTC-500MA(1206)"))
    )
    (comp (ref "I2C_1")
      (value "JST-XH-05-PIN-ROUND-PAD")
      (footprint "eagle-import:JST-XH-05-PACKAGE-ROUND-PAD")
      (libsource (lib "eagle-import") (part "JST-XH-05-PIN-ROUND-PAD"))
    )
    (comp (ref "I2C_2")
      (value "JST-XH-05-PIN-ROUND-PAD")
      (footprint "eagle-import:JST-XH-05-PACKAGE-ROUND-PAD")
      (libsource (lib "eagle-import") (part "JST-XH-05-PIN-ROUND-PAD"))
    )
    (comp (ref "I2C_3")
      (value "JST-XH-05-PIN-ROUND-PAD")
      (footprint "eagle-import:JST-XH-05-PACKAGE-ROUND-PAD")
      (libsource (lib "eagle-import") (part "JST-XH-05-PIN-ROUND-PAD"))
    )
    (comp (ref "I2C_4")
      (value "JST-XH-05-PIN-ROUND-PAD")
      (footprint "eagle-import:JST-XH-05-PACKAGE-ROUND-PAD")
      (libsource (lib "eagle-import") (part "JST-XH-05-PIN-ROUND-PAD"))
    )
    (comp (ref "I2C_5")
      (value "JST-XH-05-PIN-ROUND-PAD")
      (footprint "eagle-import:JST-XH-05-PACKAGE-ROUND-PAD")
      (libsource (lib "eagle-import") (part "JST-XH-05-PIN-ROUND-PAD"))
    )
    (comp (ref "I2C_6")
      (value "JST-XH-05-PIN-ROUND-PAD")
      (footprint "eagle-import:JST-XH-05-PACKAGE-ROUND-PAD")
      (libsource (lib "eagle-import") (part "JST-XH-05-PIN-ROUND-PAD"))
    )
    (comp (ref "I2C_7")
      (value "JST-XH-05-PIN-ROUND-PAD")
      (footprint "eagle-import:JST-XH-05-PACKAGE-ROUND-PAD")
      (libsource (lib "eagle-import") (part "JST-XH-05-PIN-ROUND-PAD"))
    )
    (comp (ref "I2C_8")
      (value "JST-XH-05-PIN-ROUND-PAD")
      (footprint "eagle-import:JST-XH-05-PACKAGE-ROUND-PAD")
      (libsource (lib "eagle-import") (part "JST-XH-05-PIN-ROUND-PAD"))
    )
    (comp (ref "I2C_9")
      (value "JST-XH-05-PIN-ROUND-PAD")
      (footprint "eagle-import:JST-XH-05-PACKAGE-ROUND-PAD")
      (libsource (lib "eagle-import") (part "JST-XH-05-PIN-ROUND-PAD"))
    )
    (comp (ref "I2C_10")
      (value "JST-XH-05-PIN-ROUND-PAD")
      (footprint "eagle-import:JST-XH-05-PACKAGE-ROUND-PAD")
      (libsource (lib "eagle-import") (part "JST-XH-05-PIN-ROUND-PAD"))
    )
    (comp (ref "I_UART_HUB_1")
      (value "JST-XH-05-PIN-ROUND-PAD")
      (footprint "eagle-import:JST-XH-05-PACKAGE-ROUND-PAD")
      (libsource (lib "eagle-import") (part "JST-XH-05-PIN-ROUND-PAD"))
    )
    (comp (ref "PI_ADC_1")
      (value "JST-XH-07-PIN-ROUND-PAD")
      (footprint "eagle-import:JST-XH-07-PACKAGE-ROUND-PAD")
      (libsource (lib "eagle-import") (part "JST-XH-07-PIN-ROUND-PAD"))
    )
    (comp (ref "PI_ADC_2")
      (value "JST-XH-07-PIN-ROUND-PAD")
      (footprint "eagle-import:JST-XH-07-PACKAGE-ROUND-PAD")
      (libsource (lib "eagle-import") (part "JST-XH-07-PIN-ROUND-PAD"))
    )
    (comp (ref "PI_ADC_3")
      (value "JST-XH-07-PIN-ROUND-PAD")
      (footprint "eagle-import:JST-XH-07-PACKAGE-ROUND-PAD")
      (libsource (lib "eagle-import") (part "JST-XH-07-PIN-ROUND-PAD"))
    )
    (comp (ref "PI_ADC_4")
      (value "JST-XH-07-PIN-ROUND-PAD")
      (footprint "eagle-import:JST-XH-07-PACKAGE-ROUND-PAD")
      (libsource (lib "eagle-import") (part "JST-XH-07-PIN-ROUND-PAD"))
    )
    (comp (ref "PI_RS_485")
      (value "JST-XH-05-PIN-ROUND-PAD")
      (footprint "eagle-import:JST-XH-05-PACKAGE-ROUND-PAD")
      (libsource (lib "eagle-import") (part "JST-XH-05-PIN-ROUND-PAD"))
    )
    (comp (ref "PI_UART")
      (value "JST-XH-05-PIN-ROUND-PAD")
      (footprint "eagle-import:JST-XH-05-PACKAGE-ROUND-PAD")
      (libsource (lib "eagle-import") (part "JST-XH-05-PIN-ROUND-PAD"))
    )
    (comp (ref "PI_UART_HUB_2")
      (value "JST-XH-05-PIN-ROUND-PAD")
      (footprint "eagle-import:JST-XH-05-PACKAGE-ROUND-PAD")
      (libsource (lib "eagle-import") (part "JST-XH-05-PIN-ROUND-PAD"))
    )
    (comp (ref "PI_UART_HUB_3")
      (value "JST-XH-05-PIN-ROUND-PAD")
      (footprint "eagle-import:JST-XH-05-PACKAGE-ROUND-PAD")
      (libsource (lib "eagle-import") (part "JST-XH-05-PIN-ROUND-PAD"))
    )
    (comp (ref "SPI_1")
      (value "JST-XH-07-PIN-ROUND-PAD")
      (footprint "eagle-import:JST-XH-07-PACKAGE-ROUND-PAD")
      (libsource (lib "eagle-import") (part "JST-XH-07-PIN-ROUND-PAD"))
    )
    (comp (ref "SPI_2")
      (value "JST-XH-07-PIN-ROUND-PAD")
      (footprint "eagle-import:JST-XH-07-PACKAGE-ROUND-PAD")
      (libsource (lib "eagle-import") (part "JST-XH-07-PIN-ROUND-PAD"))
    )
    (comp (ref "SPI_3")
      (value "JST-XH-07-PIN-ROUND-PAD")
      (footprint "eagle-import:JST-XH-07-PACKAGE-ROUND-PAD")
      (libsource (lib "eagle-import") (part "JST-XH-07-PIN-ROUND-PAD"))
    )
    (comp (ref "SPI_4")
      (value "JST-XH-07-PIN-ROUND-PAD")
      (footprint "eagle-import:JST-XH-07-PACKAGE-ROUND-PAD")
      (libsource (lib "eagle-import") (part "JST-XH-07-PIN-ROUND-PAD"))
    )
    (comp (ref "SPI_5")
      (value "JST-XH-07-PIN-ROUND-PAD")
      (footprint "eagle-import:JST-XH-07-PACKAGE-ROUND-PAD")
      (libsource (lib "eagle-import") (part "JST-XH-07-PIN-ROUND-PAD"))
    )
    (comp (ref "SPI_6")
      (value "JST-XH-07-PIN-ROUND-PAD")
      (footprint "eagle-import:JST-XH-07-PACKAGE-ROUND-PAD")
      (libsource (lib "eagle-import") (part "JST-XH-07-PIN-ROUND-PAD"))
    )
    (comp (ref "SPI_7")
      (value "JST-XH-07-PIN-ROUND-PAD")
      (footprint "eagle-import:JST-XH-07-PACKAGE-ROUND-PAD")
      (libsource (lib "eagle-import") (part "JST-XH-07-PIN-ROUND-PAD"))
    )
    (comp (ref "SPI_8")
      (value "JST-XH-07-PIN-ROUND-PAD")
      (footprint "eagle-import:JST-XH-07-PACKAGE-ROUND-PAD")
      (libsource (lib "eagle-import") (part "JST-XH-07-PIN-ROUND-PAD"))
    )
    (comp (ref "BAT1")
      (value "cr1220")
      (footprint "eagle-import:BAT2P-13.5-CR1220")
      (libsource (lib "eagle-import") (part "DIP-BATTERY-CELL-HOLDER(1220)"))
    )
    (comp (ref "C1")
      (value "10pf")
      (footprint "eagle-import:C0603")
      (fields (field (name "MPN") "CC0603JRNPO9BN100"))
      (libsource (lib "eagle-import") (part "CERAMIC-10PF-50V-5%-NPO(0603)"))
    )
    (comp (ref "C2")
      (value "100nf")
      (footprint "eagle-import:C0603")
      (fields (field (name "MPN") "CC0603KRX7R9BB104"))
      (libsource (lib "eagle-import") (part "Seeed-Capacitor-2016_450_CERAMIC-100NF-50V-10%-X7R(0603)"))
    )
    (comp (ref "C3")
      (value "10pf")
      (footprint "eagle-import:C0603")
      (fields (field (name "MPN") "CC0603JRNPO9BN100"))
      (libsource (lib "eagle-import") (part "CERAMIC-10PF-50V-5%-NPO(0603)"))
    )
    (comp (ref "C11")
      (value "100nf")
      (footprint "eagle-import:C0603")
      (fields (field (name "MPN") "CC0603KRX7R9BB104"))
      (libsource (lib "eagle-import") (part "Seeed-Capacitor-2016_450_CERAMIC-100NF-50V-10%-X7R(0603)"))
    )
    (comp (ref "C13")
      (value "100nf")
      (footprint "eagle-import:C0603")
      (fields (field (name "MPN") "CC0603KRX7R9BB104"))
      (libsource (lib "eagle-import") (part "Seeed-Capacitor-2016_450_CERAMIC-100NF-50V-10%-X7R(0603)"))
    )
    (comp (ref "C19")
      (value "100nf")
      (footprint "eagle-import:C0603")
      (fields (field (name "MPN") "CC0603KRX7R9BB104"))
      (libsource (lib "eagle-import") (part "CERAMIC-100NF-50V-10%-X7R(0603)"))
    )
    (comp (ref "F60")
      (value "SMD1206R500SF")
      (footprint "eagle-import:F1206")
      (libsource (lib "eagle-import") (part "SMD-PPTC-500MA(1206)"))
    )
    (comp (ref "F62")
      (value "SMD1206R500SF")
      (footprint "eagle-import:F1206")
      (libsource (lib "eagle-import") (part "SMD-PPTC-500MA(1206)"))
    )
    (comp (ref "J5")
      (value "16p-2.54")
      (footprint "eagle-import:H16-2.54")
      (fields (field (name "MPN") "P125-1116A0BS116AX"))
      (libsource (lib "eagle-import") (part "DIP-BLACK-MALE-HEADER-VERT(16P-2.54)"))
    )
    (comp (ref "J6")
      (value "16p-2.54")
      (footprint "eagle-import:H16-2.54")
      (fields (field (name "MPN") "P125-1116A0BS116AX"))
      (libsource (lib "eagle-import") (part "DIP-BLACK-MALE-HEADER-VERT(16P-2.54)"))
    )
    (comp (ref "J8")
      (value "2p-2.54")
      (footprint "eagle-import:H2-2.54")
      (fields (field (name "MPN") "RF130-1023ABS0741"))
      (libsource (lib "eagle-import") (part "DIP-BLACK-ROUND-FEMALE-HEADER-VERT(2P-2.54)"))
    )
    (comp (ref "J10")
      (value "16p-2.54")
      (footprint "eagle-import:H16-2.54")
      (fields (field (name "MPN") "P125-1116A0BS116AX"))
      (libsource (lib "eagle-import") (part "DIP-BLACK-MALE-HEADER-VERT(16P-2.54)"))
    )
    (comp (ref "J11")
      (value "16p-2.54")
      (footprint "eagle-import:H16-2.54")
      (fields (field (name "MPN") "P125-1116A0BS116AX"))
      (libsource (lib "eagle-import") (part "DIP-BLACK-MALE-HEADER-VERT(16P-2.54)"))
    )
    (comp (ref "PCB1")
      (value "RPI2")
      (footprint "eagle-import:RPI2")
      (libsource (lib "eagle-import") (part "RPI2"))
    )
    (comp (ref "Q1")
      (value "32.768khZ@6Pf")
      (footprint "eagle-import:85SMX")
      (libsource (lib "eagle-import") (part "LFXTAL016178"))
    )
    (comp (ref "R2")
      (value "10K 1/10W")
      (footprint "eagle-import:R0603")
      (fields (field (name "MPN") "RC0603JR-0710KL"))
      (libsource (lib "eagle-import") (part "SMD-RES-10K-5%-1/10W(0603)"))
    )
    (comp (ref "R16")
      (value "10K")
      (footprint "eagle-import:R0603")
      (fields (field (name "MPN") "RC0603FR-0710KL"))
      (libsource (lib "eagle-import") (part "SMD-RES-10K-1%-1/10W(0603)"))
    )
    (comp (ref "R17")
      (value "0R")
      (footprint "eagle-import:R0603")
      (fields (field (name "MPN") "RC0603JR-070RL"))
      (libsource (lib "eagle-import") (part "Seeed-Resistor_474_SMD-RES-0R-5%-1/10W(0603)"))
    )
    (comp (ref "R18")
      (value "10K")
      (footprint "eagle-import:R0603")
      (fields (field (name "MPN") "RC0603FR-0710KL"))
      (libsource (lib "eagle-import") (part "SMD-RES-10K-1%-1/10W(0603)"))
    )
    (comp (ref "R19")
      (value "10K")
      (footprint "eagle-import:R0603")
      (fields (field (name "MPN") "RC0603FR-0710KL"))
      (libsource (lib "eagle-import") (part "SMD-RES-10K-1%-1/10W(0603)"))
    )
    (comp (ref "R36")
      (value "1K")
      (footprint "eagle-import:R0603")
      (fields (field (name "MPN") "RC0603FR-071KL"))
      (libsource (lib "eagle-import") (part "Seeed-Resistor_474_SMD-RES-1K-1%-1/10W(0603)"))
    )
    (comp (ref "R37")
      (value "3.9K")
      (footprint "eagle-import:R0603")
      (fields (field (name "MPN") "RC0603JR-073K9L"))
      (libsource (lib "eagle-import") (part "SMD-RES-3.9K-5%-1/10W(0603)"))
    )
    (comp (ref "R38")
      (value "3.9K")
      (footprint "eagle-import:R0603")
      (fields (field (name "MPN") "RC0603JR-073K9L"))
      (libsource (lib "eagle-import") (part "SMD-RES-3.9K-5%-1/10W(0603)"))
    )
    (comp (ref "R41")
      (value "0R")
      (footprint "eagle-import:R0603")
      (fields (field (name "MPN") "RC0603JR-070RL"))
      (libsource (lib "eagle-import") (part "Seeed-Resistor_474_SMD-RES-0R-5%-1/10W(0603)"))
    )
    (comp (ref "TP6")
      (value "TPB2,54")
      (footprint "eagle-import:B2,54")
      (libsource (lib "eagle-import") (part "TPB2,54"))
    )
    (comp (ref "TP7")
      (value "TPB2,54")
      (footprint "eagle-import:B2,54")
      (libsource (lib "eagle-import") (part "TPB2,54"))
    )
    (comp (ref "TP17")
      (value "TPB2,54")
      (footprint "eagle-import:B2,54")
      (libsource (lib "eagle-import") (part "TPB2,54"))
    )
    (comp (ref "U$7")
      (value "TEMP-HUM-SENSOR-DHT22")
      (footprint "eagle-import:TEMP-HUM-SENSOR-DHT22")
      (libsource (lib "eagle-import") (part "TEMP-HUM-SENSOR-DHT22"))
    )
    (comp (ref "U1")
      (value "MCP23017-E/SO")
      (footprint "eagle-import:SOIC127P1032X265-28N")
      (libsource (lib "eagle-import") (part "MCP23017-E/SO"))
    )
    (comp (ref "U2")
      (value "MCP79412-I/SN")
      (footprint "eagle-import:SOIC127P600X175-8N")
      (libsource (lib "eagle-import") (part "MCP79412-I/SN"))
    )
    (comp (ref "U8")
      (value "BR24G32-3")
      (footprint "eagle-import:SOP8")
      (libsource (lib "eagle-import") (part "BR24G32-3"))
    )
    (comp (ref "U10")
      (value "74HCT139D")
      (footprint "eagle-import:SOIC127P600X175-16N")
      (libsource (lib "eagle-import") (part "74HCT139D"))
    )
    (comp (ref "C5")
      (value "10uf")
      (footprint "eagle-import:AVX-A")
      (fields (field (name "MPN") "TAJA106K010RNJ"))
      (libsource (lib "eagle-import") (part "TANTALUM-SMD-10UF-10V-10%(AVX-A)"))
    )
    (comp (ref "C6")
      (value "100nf")
      (footprint "eagle-import:C0603")
      (fields (field (name "MPN") "CC0603KRX7R9BB104"))
      (libsource (lib "eagle-import") (part "Seeed-Capacitor-2016_450_CERAMIC-100NF-50V-10%-X7R(0603)"))
    )
    (comp (ref "C7")
      (value "100nf")
      (footprint "eagle-import:C0603")
      (fields (field (name "MPN") "CC0603KRX7R9BB104"))
      (libsource (lib "eagle-import") (part "Seeed-Capacitor-2016_450_CERAMIC-100NF-50V-10%-X7R(0603)"))
    )
    (comp (ref "C8")
      (value "10uf")
      (footprint "eagle-import:AVX-A")
      (fields (field (name "MPN") "TAJA106K010RNJ"))
      (libsource (lib "eagle-import") (part "TANTALUM-SMD-10UF-10V-10%(AVX-A)"))
    )
    (comp (ref "U$1")
      (value "MCP3424-E/SL")
      (footprint "eagle-import:SOIC127P600X175-14N")
      (libsource (lib "eagle-import") (part "MCP3424-E/SL"))
    )
    (comp (ref "U$2")
      (value "MCP3424-E/SL")
      (footprint "eagle-import:SOIC127P600X175-14N")
      (libsource (lib "eagle-import") (part "MCP3424-E/SL"))
    )
    (comp (ref "C20")
      (value "100nf")
      (footprint "eagle-import:C0603")
      (fields (field (name "MPN") "CC0603KRX7R9BB104"))
      (libsource (lib "eagle-import") (part "Seeed-Capacitor_464_CERAMIC-100NF-50V-10%-X7R(0603)"))
    )
    (comp (ref "C21")
      (value "100nf")
      (footprint "eagle-import:C0603")
      (fields (field (name "MPN") "CC0603KRX7R9BB104"))
      (libsource (lib "eagle-import") (part "Seeed-Capacitor_464_CERAMIC-100NF-50V-10%-X7R(0603)"))
    )
    (comp (ref "C22")
      (value "100nf")
      (footprint "eagle-import:C0603")
      (fields (field (name "MPN") "CC0603KRX7R9BB104"))
      (libsource (lib "eagle-import") (part "Seeed-Capacitor_464_CERAMIC-100NF-50V-10%-X7R(0603)"))
    )
    (comp (ref "C23")
      (value "100nf")
      (footprint "eagle-import:C0603")
      (fields (field (name "MPN") "CC0603KRX7R9BB104"))
      (libsource (lib "eagle-import") (part "Seeed-Capacitor_464_CERAMIC-100NF-50V-10%-X7R(0603)"))
    )
    (comp (ref "C24")
      (value "100nf")
      (footprint "eagle-import:C0603")
      (fields (field (name "MPN") "CC0603KRX7R9BB104"))
      (libsource (lib "eagle-import") (part "Seeed-Capacitor_464_CERAMIC-100NF-50V-10%-X7R(0603)"))
    )
    (comp (ref "C38")
      (value "100nf")
      (footprint "eagle-import:C0603")
      (fields (field (name "MPN") "CC0603KRX7R9BB104"))
      (libsource (lib "eagle-import") (part "CERAMIC-100NF-50V-10%-X7R(0603)"))
    )
    (comp (ref "C39")
      (value "100nf")
      (footprint "eagle-import:C0603")
      (fields (field (name "MPN") "CC0603KRX7R9BB104"))
      (libsource (lib "eagle-import") (part "CERAMIC-100NF-50V-10%-X7R(0603)"))
    )
    (comp (ref "C40")
      (value "47uf")
      (footprint "eagle-import:AVX-A")
      (fields (field (name "MPN") "TAJA476*006#NJ"))
      (libsource (lib "eagle-import") (part "TANTALUM-SMD-47UF-6.3V(AVX-A)"))
    )
    (comp (ref "C42")
      (value "100nf")
      (footprint "eagle-import:C0603")
      (fields (field (name "MPN") "CC0603KRX7R9BB104"))
      (libsource (lib "eagle-import") (part "CERAMIC-100NF-50V-10%-X7R(0603)"))
    )
    (comp (ref "C43")
      (value "100nf")
      (footprint "eagle-import:C0603")
      (fields (field (name "MPN") "CC0603KRX7R9BB104"))
      (libsource (lib "eagle-import") (part "CERAMIC-100NF-50V-10%-X7R(0603)"))
    )
    (comp (ref "C44")
      (value "47uf")
      (footprint "eagle-import:AVX-A")
      (fields (field (name "MPN") "TAJA476*006#NJ"))
      (libsource (lib "eagle-import") (part "TANTALUM-SMD-47UF-6.3V(AVX-A)"))
    )
    (comp (ref "C46")
      (value "100nf")
      (footprint "eagle-import:C0603")
      (fields (field (name "MPN") "CC0603KRX7R9BB104"))
      (libsource (lib "eagle-import") (part "CERAMIC-100NF-50V-10%-X7R(0603)"))
    )
    (comp (ref "C47")
      (value "100nf")
      (footprint "eagle-import:C0603")
      (fields (field (name "MPN") "CC0603KRX7R9BB104"))
      (libsource (lib "eagle-import") (part "CERAMIC-100NF-50V-10%-X7R(0603)"))
    )
    (comp (ref "C48")
      (value "47uf")
      (footprint "eagle-import:AVX-A")
      (fields (field (name "MPN") "TAJA476*006#NJ"))
      (libsource (lib "eagle-import") (part "TANTALUM-SMD-47UF-6.3V(AVX-A)"))
    )
    (comp (ref "D16")
      (value "BLUE-0603")
      (footprint "eagle-import:LED-0603")
      (fields (field (name "MPN") "19-217-BHC-ZL1M2RY-3T"))
      (libsource (lib "eagle-import") (part "Seeed-LED_472_SMD-LED-CLEAR-BLUE(0603)"))
    )
    (comp (ref "D17")
      (value "GREEN-0603")
      (footprint "eagle-import:LED-0603")
      (fields (field (name "MPN") "19-217-G7C-AN1P2-3T"))
      (libsource (lib "eagle-import") (part "SMD-LED-CLEAR-GREEN(0603)"))
    )
    (comp (ref "D18")
      (value "BLUE-0603")
      (footprint "eagle-import:LED-0603")
      (fields (field (name "MPN") "19-217-BHC-ZL1M2RY-3T"))
      (libsource (lib "eagle-import") (part "Seeed-LED_472_SMD-LED-CLEAR-BLUE(0603)"))
    )
    (comp (ref "D19")
      (value "GREEN-0603")
      (footprint "eagle-import:LED-0603")
      (fields (field (name "MPN") "19-217-G7C-AN1P2-3T"))
      (libsource (lib "eagle-import") (part "SMD-LED-CLEAR-GREEN(0603)"))
    )
    (comp (ref "D20")
      (value "BLUE-0603")
      (footprint "eagle-import:LED-0603")
      (fields (field (name "MPN") "19-217-BHC-ZL1M2RY-3T"))
      (libsource (lib "eagle-import") (part "Seeed-LED_472_SMD-LED-CLEAR-BLUE(0603)"))
    )
    (comp (ref "D21")
      (value "GREEN-0603")
      (footprint "eagle-import:LED-0603")
      (fields (field (name "MPN") "19-217-G7C-AN1P2-3T"))
      (libsource (lib "eagle-import") (part "SMD-LED-CLEAR-GREEN(0603)"))
    )
    (comp (ref "R29")
      (value "330R")
      (footprint "eagle-import:R0603")
      (fields (field (name "MPN") "RC0603FR-07330RL"))
      (libsource (lib "eagle-import") (part "Seeed-Resistor_474_SMD-RES-330R-1%-1/10W(0603)"))
    )
    (comp (ref "R30")
      (value "330R")
      (footprint "eagle-import:R0603")
      (fields (field (name "MPN") "RC0603FR-07330RL"))
      (libsource (lib "eagle-import") (part "Seeed-Resistor_474_SMD-RES-330R-1%-1/10W(0603)"))
    )
    (comp (ref "R31")
      (value "330R")
      (footprint "eagle-import:R0603")
      (fields (field (name "MPN") "RC0603FR-07330RL"))
      (libsource (lib "eagle-import") (part "Seeed-Resistor_474_SMD-RES-330R-1%-1/10W(0603)"))
    )
    (comp (ref "R32")
      (value "330R")
      (footprint "eagle-import:R0603")
      (fields (field (name "MPN") "RC0603FR-07330RL"))
      (libsource (lib "eagle-import") (part "Seeed-Resistor_474_SMD-RES-330R-1%-1/10W(0603)"))
    )
    (comp (ref "R33")
      (value "330R")
      (footprint "eagle-import:R0603")
      (fields (field (name "MPN") "RC0603FR-07330RL"))
      (libsource (lib "eagle-import") (part "Seeed-Resistor_474_SMD-RES-330R-1%-1/10W(0603)"))
    )
    (comp (ref "R34")
      (value "330R")
      (footprint "eagle-import:R0603")
      (fields (field (name "MPN") "RC0603FR-07330RL"))
      (libsource (lib "eagle-import") (part "Seeed-Resistor_474_SMD-RES-330R-1%-1/10W(0603)"))
    )
    (comp (ref "SW5")
      (value "TS-1101F")
      (footprint "eagle-import:SW2-5.0-6.0X3.0X4.3MM")
      (libsource (lib "eagle-import") (part "DIP-BUTTON(2P-6.0X3.0X4.3MM)-TS-1101F"))
    )
    (comp (ref "U4")
      (value "MAX213IDBR")
      (footprint "eagle-import:SOP65P780X200-28N")
      (libsource (lib "eagle-import") (part "MAX213IDBR"))
    )
    (comp (ref "U13")
      (value "FT232RL-SSOP28")
      (footprint "eagle-import:SSOP28-0.65-10.2X5.2MM")
      (fields (field (name "MPN") "FT232RL"))
      (libsource (lib "eagle-import") (part "INTERFACE-FT232RL(SSOP28)"))
    )
    (comp (ref "U14")
      (value "FT232RL-SSOP28")
      (footprint "eagle-import:SSOP28-0.65-10.2X5.2MM")
      (fields (field (name "MPN") "FT232RL"))
      (libsource (lib "eagle-import") (part "INTERFACE-FT232RL(SSOP28)"))
    )
    (comp (ref "U15")
      (value "FT232RL-SSOP28")
      (footprint "eagle-import:SSOP28-0.65-10.2X5.2MM")
      (fields (field (name "MPN") "FT232RL"))
      (libsource (lib "eagle-import") (part "INTERFACE-FT232RL(SSOP28)"))
    )
    (comp (ref "C25")
      (value "10nf")
      (footprint "eagle-import:C0603")
      (fields (field (name "MPN") "CC0603KRX7R9BB103"))
      (libsource (lib "eagle-import") (part "CERAMIC-10NF-50V-10%-X7R(0603)"))
    )
    (comp (ref "C26")
      (value "10uf")
      (footprint "eagle-import:AVX-A")
      (fields (field (name "MPN") "TAJA106K016RNJ"))
      (libsource (lib "eagle-import") (part "TANTALUM-SMD-10UF-16V-10%(AVX-A)"))
    )
    (comp (ref "C28")
      (value "100nf")
      (footprint "eagle-import:C0603")
      (fields (field (name "MPN") "CC0603KRX7R9BB104"))
      (libsource (lib "eagle-import") (part "CERAMIC-100NF-50V-10%-X7R(0603)"))
    )
    (comp (ref "C29")
      (value "100nf")
      (footprint "eagle-import:C0603")
      (fields (field (name "MPN") "CC0603KRX7R9BB104"))
      (libsource (lib "eagle-import") (part "CERAMIC-100NF-50V-10%-X7R(0603)"))
    )
    (comp (ref "C30")
      (value "4.7uf")
      (footprint "eagle-import:AVX-A")
      (fields (field (name "MPN") "TAJA475*016#NJ"))
      (libsource (lib "eagle-import") (part "TANTALUM-SMD-4.7UF-16V(AVX-A)"))
    )
    (comp (ref "C31")
      (value "100nf")
      (footprint "eagle-import:C0805")
      (fields (field (name "MPN") "CC0805KRX7R9BB104"))
      (libsource (lib "eagle-import") (part "CERAMIC-100NF-50V-10%-X7R(0805)"))
    )
    (comp (ref "C32")
      (value "10uf")
      (footprint "eagle-import:C0805")
      (fields (field (name "MPN") "CC0805KKX5R8BB106"))
      (libsource (lib "eagle-import") (part "CERAMIC-10UF-25V-10%-X5R(0805)"))
    )
    (comp (ref "C34")
      (value "10uf")
      (footprint "eagle-import:AVX-A")
      (fields (field (name "MPN") "TAJA106K016RNJ"))
      (libsource (lib "eagle-import") (part "TANTALUM-SMD-10UF-16V-10%(AVX-A)"))
    )
    (comp (ref "C35")
      (value "100nf")
      (footprint "eagle-import:C0603")
      (fields (field (name "MPN") "CC0603KRX7R9BB104"))
      (libsource (lib "eagle-import") (part "CERAMIC-100NF-50V-10%-X7R(0603)"))
    )
    (comp (ref "C36")
      (value "100nf")
      (footprint "eagle-import:C0603")
      (fields (field (name "MPN") "CC0603KRX7R9BB104"))
      (libsource (lib "eagle-import") (part "CERAMIC-100NF-50V-10%-X7R(0603)"))
    )
    (comp (ref "D7")
      (value "BLUE-0603")
      (footprint "eagle-import:LED-0603")
      (fields (field (name "MPN") "19-217-BHC-ZL1M2RY-3T"))
      (libsource (lib "eagle-import") (part "Seeed-LED_472_SMD-LED-CLEAR-BLUE(0603)"))
    )
    (comp (ref "D12")
      (value "YELLOW-WHITE-0603")
      (footprint "eagle-import:LED-0603")
      (fields (field (name "MPN") "ADL-0603W"))
      (libsource (lib "eagle-import") (part "SMD-LED-YELLOW-WHITE(0603)"))
    )
    (comp (ref "D15")
      (value "GREEN-0603")
      (footprint "eagle-import:LED-0603")
      (fields (field (name "MPN") "19-217-G7C-AN1P2-3T"))
      (libsource (lib "eagle-import") (part "SMD-LED-CLEAR-GREEN(0603)"))
    )
    (comp (ref "L4")
      (value "330R-1500MA")
      (footprint "eagle-import:L0805")
      (fields (field (name "MPN") "BLM21PG331SN1D"))
      (libsource (lib "eagle-import") (part "SMD-FERRITE-BEAD-330R-1500MA(0805)'0805'"))
    )
    (comp (ref "R23")
      (value "330R")
      (footprint "eagle-import:R0603")
      (fields (field (name "MPN") "RC0603FR-07330RL"))
      (libsource (lib "eagle-import") (part "Seeed-Resistor_474_SMD-RES-330R-1%-1/10W(0603)"))
    )
    (comp (ref "R24")
      (value "330R")
      (footprint "eagle-import:R0603")
      (fields (field (name "MPN") "RC0603FR-07330RL"))
      (libsource (lib "eagle-import") (part "Seeed-Resistor_474_SMD-RES-330R-1%-1/10W(0603)"))
    )
    (comp (ref "R25")
      (value "120R")
      (footprint "eagle-import:R0603")
      (libsource (lib "eagle-import") (part "R-EU_R0603"))
    )
    (comp (ref "R27")
      (value "10K")
      (footprint "eagle-import:R0603")
      (fields (field (name "MPN") "RC0603FR-0710KL"))
      (libsource (lib "eagle-import") (part "SMD-RES-10K-1%-1/10W(0603)"))
    )
    (comp (ref "R28")
      (value "2.7K 1/16W")
      (footprint "eagle-import:R0402")
      (fields (field (name "MPN") "RC0402FR-072K7L"))
      (libsource (lib "eagle-import") (part "SMD-RES-2.7K-1%-1/16W(0402)"))
    )
    (comp (ref "R42")
      (value "330R")
      (footprint "eagle-import:R0603")
      (fields (field (name "MPN") "RC0603FR-07330RL"))
      (libsource (lib "eagle-import") (part "SMD-RES-330R-1%-1/10W(0603)"))
    )
    (comp (ref "SW1")
      (value "MK-12C02 G1.5")
      (footprint "eagle-import:SW7-SMD-L6.7X2.7X3.2MM")
      (libsource (lib "eagle-import") (part "SMD-TOGGLE-SWITCH-ON-ON(3+4P-6.7X2.7MM)"))
    )
    (comp (ref "TP13")
      (value "TPB2,54")
      (footprint "eagle-import:B2,54")
      (libsource (lib "eagle-import") (part "TPB2,54"))
    )
    (comp (ref "TP14")
      (value "TPB2,54")
      (footprint "eagle-import:B2,54")
      (libsource (lib "eagle-import") (part "TPB2,54"))
    )
    (comp (ref "TP15")
      (value "TPB2,54")
      (footprint "eagle-import:B2,54")
      (libsource (lib "eagle-import") (part "TPB2,54"))
    )
    (comp (ref "U$6")
      (value "FE1.1S")
      (footprint "eagle-import:FE1.1S_SSOP-28")
      (libsource (lib "eagle-import") (part "FE1.1S"))
    )
    (comp (ref "U5")
      (value "FT232RL-SSOP28")
      (footprint "eagle-import:SSOP28-0.65-10.2X5.2MM")
      (fields (field (name "MPN") "FT232RL"))
      (libsource (lib "eagle-import") (part "INTERFACE-FT232RL(SSOP28)"))
    )
    (comp (ref "U12")
      (value "SP483ECN-L")
      (footprint "eagle-import:SOIC127P600X175-8N")
      (libsource (lib "eagle-import") (part "SP483ECN-L"))
    )
    (comp (ref "USB1")
      (value "ZX62-B-5PA")
      (footprint "eagle-import:MICRO-USB5+6P-SMD-0.65-AB")
      (libsource (lib "eagle-import") (part "MICRO-USB-SMD(ZX62-B-5PA)"))
    )
    (comp (ref "Y2")
      (value "12MHZ")
      (footprint "eagle-import:X2-SMD-5.0X3.2X1.3MM")
      (fields (field (name "MPN") "5032/2P"))
      (libsource (lib "eagle-import") (part "SMD-CRYSTAL-12MHZ-20PF-20PPM-40R(2P-5.0X3.2MM)"))
    )
    (comp (ref "C4")
      (value "10uf")
      (footprint "eagle-import:AVX-A")
      (fields (field (name "MPN") "TAJA106K010RNJ"))
      (libsource (lib "eagle-import") (part "Seeed-Capacitor_464_TANTALUM-SMD-10UF-10V-10%(AVX-A)"))
    )
    (comp (ref "C10")
      (value "10uf")
      (footprint "eagle-import:AVX-A")
      (fields (field (name "MPN") "TAJA106K010RNJ"))
      (libsource (lib "eagle-import") (part "Seeed-Capacitor_464_TANTALUM-SMD-10UF-10V-10%(AVX-A)"))
    )
    (comp (ref "C12")
      (value "100nf")
      (footprint "eagle-import:C0603")
      (fields (field (name "MPN") "CC0603KRX7R9BB104"))
      (libsource (lib "eagle-import") (part "Seeed-Capacitor-2016_450_CERAMIC-100NF-50V-10%-X7R(0603)"))
    )
    (comp (ref "C14")
      (value "100nf")
      (footprint "eagle-import:C0603")
      (fields (field (name "MPN") "CC0603KRX7R9BB104"))
      (libsource (lib "eagle-import") (part "Seeed-Capacitor-2016_450_CERAMIC-100NF-50V-10%-X7R(0603)"))
    )
    (comp (ref "C18")
      (value "100nf")
      (footprint "eagle-import:C0603")
      (fields (field (name "MPN") "CC0603KRX7R9BB104"))
      (libsource (lib "eagle-import") (part "Seeed-Capacitor_464_CERAMIC-100NF-50V-10%-X7R(0603)"))
    )
    (comp (ref "D1")
      (value "28V-5A")
      (footprint "eagle-import:DO-214AA")
      (fields (field (name "MPN") "SS54B"))
      (libsource (lib "eagle-import") (part "SMD-DIODE-SCHOTTKY-28V-5A(DO-214AA)"))
    )
    (comp (ref "F1")
      (value "307010005_DIP_PPTC_4A_0310")
      (footprint "eagle-import:TH_5MM_14MM")
      (libsource (lib "eagle-import") (part "307010005_DIP_PPTC_4A_0310"))
    )
    (comp (ref "J1")
      (value "DC-044-A")
      (footprint "eagle-import:DCJ3P-11.6X9.6X7.0MM")
      (fields (field (name "MPN") "JACK-DC-044-A"))
      (libsource (lib "eagle-import") (part "JACK-DC-044-A"))
    )
    (comp (ref "L2")
      (value "330R-1500MA")
      (footprint "eagle-import:L0805")
      (fields (field (name "MPN") "BLM21PG331SN1D"))
      (libsource (lib "eagle-import") (part "Seeed-Inductor-2016_457_SMD-FERRITE-BEAD-330R-1500MA(0805)'0805'"))
    )
    (comp (ref "L3")
      (value "330R-1500MA")
      (footprint "eagle-import:L0805")
      (fields (field (name "MPN") "BLM21PG331SN1D"))
      (libsource (lib "eagle-import") (part "Seeed-Inductor-2016_457_SMD-FERRITE-BEAD-330R-1500MA(0805)'0805'"))
    )
    (comp (ref "Q2")
      (value "SSM3J328R,LF")
      (footprint "eagle-import:SOT-23")
      (libsource (lib "eagle-import") (part "SMD-MOSFET-P-CH-20V-6A-SSM3J328R(SOT-23)"))
    )
    (comp (ref "Q4")
      (value "BSS138W-7-F")
      (footprint "eagle-import:SOT-23")
      (libsource (lib "eagle-import") (part "Seeed-Transistor_477_SMD-MOSFET-N-CH-50V-200MA-BSS138W-7-F(SOT-23)"))
    )
    (comp (ref "Q5")
      (value "SSM3J328R,LF")
      (footprint "eagle-import:SOT-23")
      (libsource (lib "eagle-import") (part "SMD-MOSFET-P-CH-20V-6A-SSM3J328R(SOT-23)"))
    )
    (comp (ref "R20")
      (value "15K 1/10W")
      (footprint "eagle-import:R0603")
      (fields (field (name "MPN") "RC0603FR-0715KL"))
      (libsource (lib "eagle-import") (part "SMD-RES-15K-1%-1/10W(0603)"))
    )
    (comp (ref "R39")
      (value "100K 1/10W")
      (footprint "eagle-import:R0603")
      (fields (field (name "MPN") "RC0603JR-07100KL"))
      (libsource (lib "eagle-import") (part "Seeed-Resistor_474_SMD-RES-100K-5%-1/10W(0603)"))
    )
    (comp (ref "R40")
      (value "100K 1/10W")
      (footprint "eagle-import:R0603")
      (fields (field (name "MPN") "RC0603JR-07100KL"))
      (libsource (lib "eagle-import") (part "Seeed-Resistor_474_SMD-RES-100K-5%-1/10W(0603)"))
    )
    (comp (ref "SW3")
      (value "MK-12C02 G1.5")
      (footprint "eagle-import:SW7-SMD-L6.7X2.7X3.2MM")
      (libsource (lib "eagle-import") (part "SMD-TOGGLE-SWITCH-ON-ON(3+4P-6.7X2.7MM)"))
    )
    (comp (ref "TP1")
      (value "TPB2,54")
      (footprint "eagle-import:B2,54")
      (libsource (lib "eagle-import") (part "TPB2,54"))
    )
    (comp (ref "TP2")
      (value "TPB2,54")
      (footprint "eagle-import:B2,54")
      (libsource (lib "eagle-import") (part "TPB2,54"))
    )
    (comp (ref "TP3")
      (value "TPB2,54")
      (footprint "eagle-import:B2,54")
      (libsource (lib "eagle-import") (part "TPB2,54"))
    )
    (comp (ref "TP4")
      (value "TPB2,54")
      (footprint "eagle-import:B2,54")
      (libsource (lib "eagle-import") (part "TPB2,54"))
    )
    (comp (ref "TP8")
      (value "TPB2,54")
      (footprint "eagle-import:B2,54")
      (libsource (lib "eagle-import") (part "TPB2,54"))
    )
    (comp (ref "TP9")
      (value "TPB2,54")
      (footprint "eagle-import:B2,54")
      (libsource (lib "eagle-import") (part "TPB2,54"))
    )
    (comp (ref "TP10")
      (value "TPB2,54")
      (footprint "eagle-import:B2,54")
      (libsource (lib "eagle-import") (part "TPB2,54"))
    )
    (comp (ref "TP11")
      (value "TPB2,54")
      (footprint "eagle-import:B2,54")
      (libsource (lib "eagle-import") (part "TPB2,54"))
    )
    (comp (ref "TP12")
      (value "TPB2,54")
      (footprint "eagle-import:B2,54")
      (libsource (lib "eagle-import") (part "TPB2,54"))
    )
    (comp (ref "TP16")
      (value "TPB2,54")
      (footprint "eagle-import:B2,54")
      (libsource (lib "eagle-import") (part "TPB2,54"))
    )
    (comp (ref "U$3")
      (value "C106DG")
      (footprint "eagle-import:TO-225AA")
      (libsource (lib "eagle-import") (part "C106DG"))
    )
    (comp (ref "U$4")
      (value "MIC29300")
      (footprint "eagle-import:TO-263")
      (libsource (lib "eagle-import") (part "MIC29300"))
    )
    (comp (ref "U$5")
      (value "DC-DC-STEP-DOWN-LM2596")
      (footprint "eagle-import:DC-DC-STEP-DOWN-LM2596")
      (libsource (lib "eagle-import") (part "DC-DC-STEP-DOWN-LM2596"))
    )
    (comp (ref "U11")
      (value "BZX84C30")
      (footprint "eagle-import:SOT91P240X110-3N")
      (libsource (lib "eagle-import") (part "BZX84C30"))
    )
    (comp (ref "C9")
      (value "10nf")
      (footprint "eagle-import:C0805")
      (fields (field (name "MPN") "CC0805JRX7R9BB103"))
      (libsource (lib "eagle-import") (part "CERAMIC-10NF-50V-5%-X7R(0805)"))
    )
    (comp (ref "C15")
      (value "100nf")
      (footprint "eagle-import:C0603")
      (fields (field (name "MPN") "CC0603KRX7R9BB104"))
      (libsource (lib "eagle-import") (part "CERAMIC-100NF-50V-10%-X7R(0603)"))
    )
    (comp (ref "C16")
      (value "100nf")
      (footprint "eagle-import:C0603")
      (fields (field (name "MPN") "CC0603KRX7R9BB104"))
      (libsource (lib "eagle-import") (part "CERAMIC-100NF-50V-10%-X7R(0603)"))
    )
    (comp (ref "C17")
      (value "4.7uf")
      (footprint "eagle-import:AVX-A")
      (fields (field (name "MPN") "TAJA475*016#NJ"))
      (libsource (lib "eagle-import") (part "Seeed-Capacitor_464_TANTALUM-SMD-4.7UF-16V(AVX-A)"))
    )
    (comp (ref "D2")
      (value "BLUE-0603")
      (footprint "eagle-import:LED-0603")
      (fields (field (name "MPN") "19-217-BHC-ZL1M2RY-3T"))
      (libsource (lib "eagle-import") (part "Seeed-LED_472_SMD-LED-CLEAR-BLUE(0603)"))
    )
    (comp (ref "D3")
      (value "GREEN-0603")
      (footprint "eagle-import:LED-0603")
      (fields (field (name "MPN") "19-217-G7C-AN1P2-3T"))
      (libsource (lib "eagle-import") (part "SMD-LED-CLEAR-GREEN(0603)"))
    )
    (comp (ref "F59")
      (value "SMD1206R500SF")
      (footprint "eagle-import:F1206")
      (libsource (lib "eagle-import") (part "SMD-PPTC-500MA(1206)"))
    )
    (comp (ref "F74")
      (value "SMD1206R500SF")
      (footprint "eagle-import:F1206")
      (libsource (lib "eagle-import") (part "SMD-PPTC-500MA(1206)"))
    )
    (comp (ref "F75")
      (value "SMD1206R500SF")
      (footprint "eagle-import:F1206")
      (libsource (lib "eagle-import") (part "SMD-PPTC-500MA(1206)"))
    )
    (comp (ref "F76")
      (value "SMD1206R500SF")
      (footprint "eagle-import:F1206")
      (libsource (lib "eagle-import") (part "SMD-PPTC-500MA(1206)"))
    )
    (comp (ref "F78")
      (value "SMD1206R500SF")
      (footprint "eagle-import:F1206")
      (libsource (lib "eagle-import") (part "SMD-PPTC-500MA(1206)"))
    )
    (comp (ref "F79")
      (value "SMD1206R500SF")
      (footprint "eagle-import:F1206")
      (libsource (lib "eagle-import") (part "SMD-PPTC-500MA(1206)"))
    )
    (comp (ref "F80")
      (value "SMD1206R500SF")
      (footprint "eagle-import:F1206")
      (libsource (lib "eagle-import") (part "SMD-PPTC-500MA(1206)"))
    )
    (comp (ref "F81")
      (value "SMD1206R500SF")
      (footprint "eagle-import:F1206")
      (libsource (lib "eagle-import") (part "SMD-PPTC-500MA(1206)"))
    )
    (comp (ref "F82")
      (value "SMD1206R500SF")
      (footprint "eagle-import:F1206")
      (libsource (lib "eagle-import") (part "SMD-PPTC-500MA(1206)"))
    )
    (comp (ref "F83")
      (value "SMD1206R500SF")
      (footprint "eagle-import:F1206")
      (libsource (lib "eagle-import") (part "SMD-PPTC-500MA(1206)"))
    )
    (comp (ref "J2")
      (value "MICROSD-9P")
      (footprint "eagle-import:MICRO-SD9+4P-SMD-16.1X14.5X1.85MM")
      (libsource (lib "eagle-import") (part "MICRO-SD-CARD-HOLDER-9P"))
    )
    (comp (ref "J3")
      (value "2p-2.54")
      (footprint "eagle-import:H2-2.54")
      (fields (field (name "MPN") "P125-1102A0BS116A1"))
      (libsource (lib "eagle-import") (part "DIP-BLACK-MALE-HEADER-VERT(2P-2.54)"))
    )
    (comp (ref "J4")
      (value "2p-2.54")
      (footprint "eagle-import:H2-2.54")
      (fields (field (name "MPN") "P125-1102A0BS116A1"))
      (libsource (lib "eagle-import") (part "DIP-BLACK-MALE-HEADER-VERT(2P-2.54)"))
    )
    (comp (ref "J7")
      (value "16p-2.54")
      (footprint "eagle-import:H16-2.54")
      (fields (field (name "MPN") "P125-1116A0BS116AX"))
      (libsource (lib "eagle-import") (part "DIP-BLACK-MALE-HEADER-VERT(16P-2.54)"))
    )
    (comp (ref "J9")
      (value "16p-2.54")
      (footprint "eagle-import:H16-2.54")
      (fields (field (name "MPN") "P125-1116A0BS116AX"))
      (libsource (lib "eagle-import") (part "DIP-BLACK-MALE-HEADER-VERT(16P-2.54)"))
    )
    (comp (ref "L1")
      (value "330R-1500MA")
      (footprint "eagle-import:L0805")
      (fields (field (name "MPN") "BLM21PG331SN1D"))
      (libsource (lib "eagle-import") (part "SMD-FERRITE-BEAD-330R-1500MA(0805)'0805'"))
    )
    (comp (ref "LOPY_I2C")
      (value "JST-XH-05-PIN-ROUND-PAD")
      (footprint "eagle-import:JST-XH-05-PACKAGE-ROUND-PAD")
      (libsource (lib "eagle-import") (part "JST-XH-05-PIN-ROUND-PAD"))
    )
    (comp (ref "LOPY_SPI")
      (value "JST-XH-07-PIN-ROUND-PAD")
      (footprint "eagle-import:JST-XH-07-PACKAGE-ROUND-PAD")
      (libsource (lib "eagle-import") (part "JST-XH-07-PIN-ROUND-PAD"))
    )
    (comp (ref "LOPY_UART0")
      (value "JST-XH-05-PIN-ROUND-PAD")
      (footprint "eagle-import:JST-XH-05-PACKAGE-ROUND-PAD")
      (libsource (lib "eagle-import") (part "JST-XH-05-PIN-ROUND-PAD"))
    )
    (comp (ref "LOPY_UART1")
      (value "JST-XH-05-PIN-ROUND-PAD")
      (footprint "eagle-import:JST-XH-05-PACKAGE-ROUND-PAD")
      (libsource (lib "eagle-import") (part "JST-XH-05-PIN-ROUND-PAD"))
    )
    (comp (ref "Q3")
      (value "BSS138W-7-F")
      (footprint "eagle-import:SOT-23")
      (libsource (lib "eagle-import") (part "SMD-MOSFET-N-CH-50V-200MA-BSS138W-7-F(SOT-23)"))
    )
    (comp (ref "Q6")
      (value "BSS138W-7-F")
      (footprint "eagle-import:SOT-23")
      (libsource (lib "eagle-import") (part "SMD-MOSFET-N-CH-50V-200MA-BSS138W-7-F(SOT-23)"))
    )
    (comp (ref "Q7")
      (value "BSS138W-7-F")
      (footprint "eagle-import:SOT-23")
      (libsource (lib "eagle-import") (part "SMD-MOSFET-N-CH-50V-200MA-BSS138W-7-F(SOT-23)"))
    )
    (comp (ref "Q8")
      (value "CJ2305")
      (footprint "eagle-import:SOT-23")
      (libsource (lib "eagle-import") (part "SMD-MOSFET-P-CH-8V-4.1A-CJ2305(SOT-23)"))
    )
    (comp (ref "R1")
      (value "330R")
      (footprint "eagle-import:R0603")
      (fields (field (name "MPN") "RC0603FR-07330RL"))
      (libsource (lib "eagle-import") (part "Seeed-Resistor_474_SMD-RES-330R-1%-1/10W(0603)"))
    )
    (comp (ref "R3")
      (value "330R")
      (footprint "eagle-import:R0603")
      (fields (field (name "MPN") "RC0603FR-07330RL"))
      (libsource (lib "eagle-import") (part "Seeed-Resistor_474_SMD-RES-330R-1%-1/10W(0603)"))
    )
    (comp (ref "R8")
      (value "0R")
      (footprint "eagle-import:R0603")
      (fields (field (name "MPN") "RC0603JR-070RL"))
      (libsource (lib "eagle-import") (part "SMD-RES-0R-5%-1/10W(0603)"))
    )
    (comp (ref "R12")
      (value "0R")
      (footprint "eagle-import:R0603")
      (fields (field (name "MPN") "RC0603JR-070RL"))
      (libsource (lib "eagle-import") (part "SMD-RES-0R-5%-1/10W(0603)"))
    )
    (comp (ref "R13")
      (value "0R")
      (footprint "eagle-import:R0603")
      (fields (field (name "MPN") "RC0603JR-070RL"))
      (libsource (lib "eagle-import") (part "SMD-RES-0R-5%-1/10W(0603)"))
    )
    (comp (ref "R14")
      (value "0R")
      (footprint "eagle-import:R0603")
      (fields (field (name "MPN") "RC0603JR-070RL"))
      (libsource (lib "eagle-import") (part "SMD-RES-0R-5%-1/10W(0603)"))
    )
    (comp (ref "R15")
      (value "0R")
      (footprint "eagle-import:R0603")
      (fields (field (name "MPN") "RC0603JR-070RL"))
      (libsource (lib "eagle-import") (part "SMD-RES-0R-5%-1/10W(0603)"))
    )
    (comp (ref "R43")
      (value "100K 1/10W")
      (footprint "eagle-import:R0603")
      (fields (field (name "MPN") "RC0603JR-07100KL"))
      (libsource (lib "eagle-import") (part "SMD-RES-100K-5%-1/10W(0603)"))
    )
    (comp (ref "R44")
      (value "100K 1/10W")
      (footprint "eagle-import:R0603")
      (fields (field (name "MPN") "RC0603JR-07100KL"))
      (libsource (lib "eagle-import") (part "SMD-RES-100K-5%-1/10W(0603)"))
    )
    (comp (ref "R45")
      (value "100K 1/10W")
      (footprint "eagle-import:R0603")
      (fields (field (name "MPN") "RC0603JR-07100KL"))
      (libsource (lib "eagle-import") (part "SMD-RES-100K-5%-1/10W(0603)"))
    )
    (comp (ref "R46")
      (value "100K 1/10W")
      (footprint "eagle-import:R0603")
      (fields (field (name "MPN") "RC0603JR-07100KL"))
      (libsource (lib "eagle-import") (part "SMD-RES-100K-5%-1/10W(0603)"))
    )
    (comp (ref "TP5")
      (value "TPB2,54")
      (footprint "eagle-import:B2,54")
      (libsource (lib "eagle-import") (part "TPB2,54"))
    )
    (comp (ref "U3")
      (value "LOPY")
      (footprint "eagle-import:LOPY")
      (libsource (lib "eagle-import") (part "LOPY"))
    )
    (comp (ref "U6")
      (value "FT232RL-SSOP28")
      (footprint "eagle-import:SSOP28-0.65-10.2X5.2MM")
      (fields (field (name "MPN") "FT232RL"))
      (libsource (lib "eagle-import") (part "INTERFACE-FT232RL(SSOP28)"))
    )
    (comp (ref "USB3")
      (value "ZX62-B-5PA")
      (footprint "eagle-import:MICRO-USB5+6P-SMD-0.65-AB")
      (libsource (lib "eagle-import") (part "MICRO-USB-SMD(ZX62-B-5PA)"))
    )
  )
  (nets
    (net (code "1") (name "+3V3") (class "Default")
      (node (ref "C11") (pin "2") (pinfunction "2_2") (pintype "passive"))
      (node (ref "C12") (pin "2") (pinfunction "2_2") (pintype "passive"))
      (node (ref "C2") (pin "2") (pinfunction "2_2") (pintype "passive"))
      (node (ref "F10") (pin "1") (pinfunction "1_1") (pintype "bidirectional"))
      (node (ref "F12") (pin "1") (pinfunction "1_1") (pintype "bidirectional"))
      (node (ref "F14") (pin "1") (pinfunction "1_1") (pintype "bidirectional"))
      (node (ref "F16") (pin "1") (pinfunction "1_1") (pintype "bidirectional"))
      (node (ref "F18") (pin "1") (pinfunction "1_1") (pintype "bidirectional"))
      (node (ref "F20") (pin "1") (pinfunction "1_1") (pintype "bidirectional"))
      (node (ref "F22") (pin "1") (pinfunction "1_1") (pintype "bidirectional"))
      (node (ref "F23") (pin "1") (pinfunction "1_1") (pintype "bidirectional"))
      (node (ref "F25") (pin "1") (pinfunction "1_1") (pintype "bidirectional"))
      (node (ref "F27") (pin "1") (pinfunction "1_1") (pintype "bidirectional"))
      (node (ref "F29") (pin "1") (pinfunction "1_1") (pintype "bidirectional"))
      (node (ref "F3") (pin "1") (pinfunction "1_1") (pintype "bidirectional"))
      (node (ref "F31") (pin "1") (pinfunction "1_1") (pintype "bidirectional"))
      (node (ref "F33") (pin "1") (pinfunction "1_1") (pintype "bidirectional"))
      (node (ref "F35") (pin "1") (pinfunction "1_1") (pintype "bidirectional"))
      (node (ref "F37") (pin "1") (pinfunction "1_1") (pintype "bidirectional"))
      (node (ref "F47") (pin "1") (pinfunction "1_1") (pintype "bidirectional"))
      (node (ref "F49") (pin "1") (pinfunction "1_1") (pintype "bidirectional"))
      (node (ref "F51") (pin "1") (pinfunction "1_1") (pintype "bidirectional"))
      (node (ref "F53") (pin "1") (pinfunction "1_1") (pintype "bidirectional"))
      (node (ref "F55") (pin "1") (pinfunction "1_1") (pintype "bidirectional"))
      (node (ref "F6") (pin "1") (pinfunction "1_1") (pintype "bidirectional"))
      (node (ref "F62") (pin "1") (pinfunction "1_1") (pintype "bidirectional"))
      (node (ref "F8") (pin "1") (pinfunction "1_1") (pintype "bidirectional"))
      (node (ref "L2") (pin "1") (pinfunction "1_1") (pintype "passive"))
      (node (ref "PCB1") (pin "P$1") (pinfunction "3V3_P$1") (pintype "bidirectional"))
      (node (ref "PCB1") (pin "P$17") (pinfunction "3V3_P$17") (pintype "bidirectional"))
      (node (ref "R16") (pin "2") (pinfunction "2_2") (pintype "passive"))
      (node (ref "R18") (pin "2") (pinfunction "2_2") (pintype "passive"))
      (node (ref "R19") (pin "2") (pinfunction "2_2") (pintype "passive"))
      (node (ref "R2") (pin "2") (pinfunction "2_2") (pintype "passive"))
      (node (ref "R9") (pin "2") (pinfunction "2_2") (pintype "passive"))
      (node (ref "TP2") (pin "TP") (pinfunction "TP_TP") (pintype "input"))
      (node (ref "U$7") (pin "1") (pinfunction "VDD_1") (pintype "power_in"))
      (node (ref "U1") (pin "9") (pinfunction "VDD_9") (pintype "power_in"))
      (node (ref "U2") (pin "8") (pinfunction "VCC_8") (pintype "power_in"))
    )
    (net (code "2") (name "+3V3_SMOOTH") (class "Default")
      (node (ref "C14") (pin "2") (pinfunction "2_2") (pintype "passive"))
      (node (ref "C5") (pin "+") (pinfunction "+_+") (pintype "passive"))
      (node (ref "C6") (pin "2") (pinfunction "2_2") (pintype "passive"))
      (node (ref "C7") (pin "2") (pinfunction "2_2") (pintype "passive"))
      (node (ref "C8") (pin "+") (pinfunction "+_+") (pintype "passive"))
      (node (ref "F39") (pin "1") (pinfunction "1_1") (pintype "bidirectional"))
      (node (ref "F41") (pin "1") (pinfunction "1_1") (pintype "bidirectional"))
      (node (ref "F43") (pin "1") (pinfunction "1_1") (pintype "bidirectional"))
      (node (ref "F45") (pin "1") (pinfunction "1_1") (pintype "bidirectional"))
      (node (ref "L2") (pin "2") (pinfunction "2_2") (pintype "passive"))
      (node (ref "R10") (pin "2") (pinfunction "2_2") (pintype "passive"))
      (node (ref "TP3") (pin "TP") (pinfunction "TP_TP") (pintype "input"))
      (node (ref "U$1") (pin "6") (pinfunction "VDD_6") (pintype "power_in"))
      (node (ref "U$2") (pin "6") (pinfunction "VDD_6") (pintype "power_in"))
    )
    (net (code "3") (name "+5V") (class "Default")
      (node (ref "C10") (pin "+") (pinfunction "+_+") (pintype "passive"))
      (node (ref "F74") (pin "1") (pinfunction "1_1") (pintype "bidirectional"))
      (node (ref "F76") (pin "1") (pinfunction "1_1") (pintype "bidirectional"))
      (node (ref "F78") (pin "1") (pinfunction "1_1") (pintype "bidirectional"))
      (node (ref "F80") (pin "1") (pinfunction "1_1") (pintype "bidirectional"))
      (node (ref "F82") (pin "1") (pinfunction "1_1") (pintype "bidirectional"))
      (node (ref "Q2") (pin "3") (pinfunction "D_3") (pintype "passive"))
      (node (ref "R39") (pin "2") (pinfunction "2_2") (pintype "passive"))
      (node (ref "R6") (pin "2") (pinfunction "2_2") (pintype "passive"))
      (node (ref "TP1") (pin "TP") (pinfunction "TP_TP") (pintype "input"))
      (node (ref "U$4") (pin "3") (pinfunction "VOUT_3") (pintype "output"))
      (node (ref "U3") (pin "P$28") (pinfunction "5V_P$28") (pintype "power_in"))
    )
    (net (code "4") (name "+24V") (class "Default")
      (node (ref "D1") (pin "-") (pinfunction "-_-") (pintype "passive"))
      (node (ref "R5") (pin "2") (pinfunction "2_2") (pintype "passive"))
      (node (ref "U$3") (pin "1") (pinfunction "A_1") (pintype "passive"))
      (node (ref "U$5") (pin "IN+") (pinfunction "IN+_IN+") (pintype "bidirectional"))
      (node (ref "U11") (pin "3") (pinfunction "CATHODE_3") (pintype "passive"))
    )
    (net (code "5") (name "+24V_UNREG_IN") (class "Default")
      (node (ref "F1") (pin "P$1") (pinfunction "P$1_P$1") (pintype "passive"))
      (node (ref "J1") (pin "+") (pinfunction "+_+") (pintype "bidirectional"))
    )
    (net (code "6") (name "3V3") (class "Default")
      (node (ref "C19") (pin "1") (pinfunction "1_1") (pintype "passive"))
      (node (ref "R36") (pin "2") (pinfunction "2_2") (pintype "passive"))
      (node (ref "R37") (pin "2") (pinfunction "2_2") (pintype "passive"))
      (node (ref "R38") (pin "2") (pinfunction "2_2") (pintype "passive"))
      (node (ref "U8") (pin "8") (pinfunction "VCC_8") (pintype "power_in"))
    )
    (net (code "7") (name "5V35") (class "Default")
      (node (ref "C4") (pin "+") (pinfunction "+_+") (pintype "passive"))
      (node (ref "R7") (pin "2") (pinfunction "2_2") (pintype "passive"))
      (node (ref "TP4") (pin "TP") (pinfunction "TP_TP") (pintype "input"))
      (node (ref "U$4") (pin "1") (pinfunction "VIN_1") (pintype "input"))
      (node (ref "U$5") (pin "OUT+") (pinfunction "OUT+_OUT+") (pintype "bidirectional"))
    )
    (net (code "8") (name "5V_USB_HUB") (class "Default")
      (node (ref "C25") (pin "2") (pinfunction "2_2") (pintype "passive"))
      (node (ref "L4") (pin "1") (pinfunction "1_1") (pintype "passive"))
      (node (ref "R35") (pin "2") (pinfunction "2_2") (pintype "passive"))
      (node (ref "USB1") (pin "1") (pinfunction "VBUS_1") (pintype "power_in"))
    )
    (net (code "9") (name "5V_USB_HUB_FERRITE") (class "Default")
      (node (ref "C20") (pin "2") (pinfunction "2_2") (pintype "passive"))
      (node (ref "C23") (pin "2") (pinfunction "2_2") (pintype "passive"))
      (node (ref "C28") (pin "2") (pinfunction "2_2") (pintype "passive"))
      (node (ref "C30") (pin "+") (pinfunction "+_+") (pintype "passive"))
      (node (ref "C31") (pin "2") (pinfunction "2_2") (pintype "passive"))
      (node (ref "C32") (pin "1") (pinfunction "1_1") (pintype "passive"))
      (node (ref "C38") (pin "2") (pinfunction "2_2") (pintype "passive"))
      (node (ref "C40") (pin "+") (pinfunction "+_+") (pintype "passive"))
      (node (ref "C42") (pin "2") (pinfunction "2_2") (pintype "passive"))
      (node (ref "C44") (pin "+") (pinfunction "+_+") (pintype "passive"))
      (node (ref "C46") (pin "2") (pinfunction "2_2") (pintype "passive"))
      (node (ref "C48") (pin "+") (pinfunction "+_+") (pintype "passive"))
      (node (ref "L4") (pin "2") (pinfunction "2_2") (pintype "passive"))
      (node (ref "R27") (pin "2") (pinfunction "2_2") (pintype "passive"))
      (node (ref "SW5") (pin "2") (pinfunction "2_2") (pintype "bidirectional"))
      (node (ref "U$6") (pin "20") (pinfunction "VDD5_20") (pintype "bidirectional"))
      (node (ref "U12") (pin "8") (pinfunction "VCC_8") (pintype "power_in"))
      (node (ref "U13") (pin "20") (pinfunction "VCC_20") (pintype "input"))
      (node (ref "U13") (pin "4") (pinfunction "VCCIO_4") (pintype "input"))
      (node (ref "U14") (pin "20") (pinfunction "VCC_20") (pintype "input"))
      (node (ref "U14") (pin "4") (pinfunction "VCCIO_4") (pintype "input"))
      (node (ref "U15") (pin "20") (pinfunction "VCC_20") (pintype "input"))
      (node (ref "U15") (pin "4") (pinfunction "VCCIO_4") (pintype "input"))
      (node (ref "U4") (pin "11") (pinfunction "VCC_11") (pintype "power_in"))
      (node (ref "U4") (pin "24") (pinfunction "EN_24") (pintype "input"))
      (node (ref "U4") (pin "25") (pinfunction "~{SHDN}_25") (pintype "input"))
      (node (ref "U5") (pin "20") (pinfunction "VCC_20") (pintype "input"))
      (node (ref "U5") (pin "4") (pinfunction "VCCIO_4") (pintype "input"))
    )
    (net (code "10") (name "ADC1+") (class "Default")
      (node (ref "PI_ADC_1") (pin "3") (pinfunction "S_3") (pintype "passive"))
      (node (ref "U$1") (pin "1") (pinfunction "CH1+_1") (pintype "input"))
    )
    (net (code "11") (name "ADC1-") (class "Default")
      (node (ref "PI_ADC_1") (pin "4") (pinfunction "S_4") (pintype "passive"))
      (node (ref "U$1") (pin "2") (pinfunction "CH1-_2") (pintype "input"))
    )
    (net (code "12") (name "ADC2+") (class "Default")
      (node (ref "PI_ADC_1") (pin "5") (pinfunction "S_5") (pintype "passive"))
      (node (ref "U$1") (pin "3") (pinfunction "CH2+_3") (pintype "input"))
    )
    (net (code "13") (name "ADC2-") (class "Default")
      (node (ref "PI_ADC_1") (pin "6") (pinfunction "S_6") (pintype "passive"))
      (node (ref "U$1") (pin "4") (pinfunction "CH2-_4") (pintype "input"))
    )
    (net (code "14") (name "ADC3+") (class "Default")
      (node (ref "PI_ADC_2") (pin "3") (pinfunction "S_3") (pintype "passive"))
      (node (ref "U$1") (pin "11") (pinfunction "CH3+_11") (pintype "input"))
    )
    (net (code "15") (name "ADC3-") (class "Default")
      (node (ref "PI_ADC_2") (pin "4") (pinfunction "S_4") (pintype "passive"))
      (node (ref "U$1") (pin "12") (pinfunction "CH3-_12") (pintype "input"))
    )
    (net (code "16") (name "ADC4+") (class "Default")
      (node (ref "PI_ADC_2") (pin "5") (pinfunction "S_5") (pintype "passive"))
      (node (ref "U$1") (pin "13") (pinfunction "CH4+_13") (pintype "input"))
    )
    (net (code "17") (name "ADC4-") (class "Default")
      (node (ref "PI_ADC_2") (pin "6") (pinfunction "S_6") (pintype "passive"))
      (node (ref "U$1") (pin "14") (pinfunction "CH4-_14") (pintype "input"))
    )
    (net (code "18") (name "ADC5+") (class "Default")
      (node (ref "PI_ADC_3") (pin "3") (pinfunction "S_3") (pintype "passive"))
      (node (ref "U$2") (pin "1") (pinfunction "CH1+_1") (pintype "input"))
    )
    (net (code "19") (name "ADC5-") (class "Default")
      (node (ref "PI_ADC_3") (pin "4") (pinfunction "S_4") (pintype "passive"))
      (node (ref "U$2") (pin "2") (pinfunction "CH1-_2") (pintype "input"))
    )
    (net (code "20") (name "ADC6+") (class "Default")
      (node (ref "PI_ADC_3") (pin "5") (pinfunction "S_5") (pintype "passive"))
      (node (ref "U$2") (pin "3") (pinfunction "CH2+_3") (pintype "input"))
    )
    (net (code "21") (name "ADC6-") (class "Default")
      (node (ref "PI_ADC_3") (pin "6") (pinfunction "S_6") (pintype "passive"))
      (node (ref "U$2") (pin "4") (pinfunction "CH2-_4") (pintype "input"))
    )
    (net (code "22") (name "ADC7+") (class "Default")
      (node (ref "PI_ADC_4") (pin "3") (pinfunction "S_3") (pintype "passive"))
      (node (ref "U$2") (pin "11") (pinfunction "CH3+_11") (pintype "input"))
    )
    (net (code "23") (name "ADC7-") (class "Default")
      (node (ref "PI_ADC_4") (pin "4") (pinfunction "S_4") (pintype "passive"))
      (node (ref "U$2") (pin "12") (pinfunction "CH3-_12") (pintype "input"))
    )
    (net (code "24") (name "ADC8+") (class "Default")
      (node (ref "PI_ADC_4") (pin "5") (pinfunction "S_5") (pintype "passive"))
      (node (ref "U$2") (pin "13") (pinfunction "CH4+_13") (pintype "input"))
    )
    (net (code "25") (name "ADC8-") (class "Default")
      (node (ref "PI_ADC_4") (pin "6") (pinfunction "S_6") (pintype "passive"))
      (node (ref "U$2") (pin "14") (pinfunction "CH4-_14") (pintype "input"))
    )
    (net (code "26") (name "FTDI1_3V3") (class "Default")
      (node (ref "C16") (pin "2") (pinfunction "2_2") (pintype "passive"))
      (node (ref "U6") (pin "17") (pinfunction "3V3OUT_17") (pintype "input"))
    )
    (net (code "27") (name "FTDI2_3V3") (class "Default")
      (node (ref "C29") (pin "2") (pinfunction "2_2") (pintype "passive"))
      (node (ref "U5") (pin "17") (pinfunction "3V3OUT_17") (pintype "input"))
    )
    (net (code "28") (name "FTDI2_RE") (class "Default")
      (node (ref "R27") (pin "1") (pinfunction "1_1") (pintype "passive"))
      (node (ref "U12") (pin "2") (pinfunction "~{RE}_2") (pintype "input"))
      (node (ref "U5") (pin "14") (pinfunction "CBUS3_14") (pintype "input"))
    )
    (net (code "29") (name "FTDI2_RXD") (class "Default")
      (node (ref "U12") (pin "1") (pinfunction "RO_1") (pintype "output"))
      (node (ref "U5") (pin "5") (pinfunction "RXD_5") (pintype "input"))
    )
    (net (code "30") (name "FTDI2_TE") (class "Default")
      (node (ref "U12") (pin "3") (pinfunction "DE_3") (pintype "input"))
      (node (ref "U5") (pin "13") (pinfunction "CBUS2_13") (pintype "input"))
    )
    (net (code "31") (name "FTDI2_TXD") (class "Default")
      (node (ref "U12") (pin "4") (pinfunction "DI_4") (pintype "input"))
      (node (ref "U5") (pin "1") (pinfunction "TXD_1") (pintype "input"))
    )
    (net (code "32") (name "FTDI3_3V3") (class "Default")
      (node (ref "C39") (pin "2") (pinfunction "2_2") (pintype "passive"))
      (node (ref "U13") (pin "17") (pinfunction "3V3OUT_17") (pintype "input"))
    )
    (net (code "33") (name "FTDI4_3V3") (class "Default")
      (node (ref "C43") (pin "2") (pinfunction "2_2") (pintype "passive"))
      (node (ref "U14") (pin "17") (pinfunction "3V3OUT_17") (pintype "input"))
    )
    (net (code "34") (name "FTDI5_3V3") (class "Default")
      (node (ref "C47") (pin "2") (pinfunction "2_2") (pintype "passive"))
      (node (ref "U15") (pin "17") (pinfunction "3V3OUT_17") (pintype "input"))
    )
    (net (code "35") (name "FTDI_HUB_LEDS") (class "Default")
      (node (ref "R23") (pin "1") (pinfunction "1_1") (pintype "passive"))
      (node (ref "R24") (pin "1") (pinfunction "1_1") (pintype "passive"))
      (node (ref "R29") (pin "1") (pinfunction "1_1") (pintype "passive"))
      (node (ref "R30") (pin "1") (pinfunction "1_1") (pintype "passive"))
      (node (ref "R31") (pin "1") (pinfunction "1_1") (pintype "passive"))
      (node (ref "R32") (pin "1") (pinfunction "1_1") (pintype "passive"))
      (node (ref "R33") (pin "1") (pinfunction "1_1") (pintype "passive"))
      (node (ref "R34") (pin "1") (pinfunction "1_1") (pintype "passive"))
      (node (ref "SW5") (pin "1") (pinfunction "1_1") (pintype "bidirectional"))
    )
    (net (code "36") (name "GND") (class "Default")
      (node (ref "BAT1") (pin "-") (pinfunction "V-_-") (pintype "bidirectional"))
      (node (ref "C1") (pin "2") (pinfunction "2_2") (pintype "passive"))
      (node (ref "C10") (pin "-") (pinfunction "-_-") (pintype "passive"))
      (node (ref "C11") (pin "1") (pinfunction "1_1") (pintype "passive"))
      (node (ref "C12") (pin "1") (pinfunction "1_1") (pintype "passive"))
      (node (ref "C13") (pin "1") (pinfunction "1_1") (pintype "passive"))
      (node (ref "C15") (pin "1") (pinfunction "1_1") (pintype "passive"))
      (node (ref "C16") (pin "1") (pinfunction "1_1") (pintype "passive"))
      (node (ref "C17") (pin "-") (pinfunction "-_-") (pintype "passive"))
      (node (ref "C18") (pin "1") (pinfunction "1_1") (pintype "passive"))
      (node (ref "C19") (pin "2") (pinfunction "2_2") (pintype "passive"))
      (node (ref "C2") (pin "1") (pinfunction "1_1") (pintype "passive"))
      (node (ref "C22") (pin "2") (pinfunction "2_2") (pintype "passive"))
      (node (ref "C23") (pin "1") (pinfunction "1_1") (pintype "passive"))
      (node (ref "C25") (pin "1") (pinfunction "1_1") (pintype "passive"))
      (node (ref "C26") (pin "-") (pinfunction "-_-") (pintype "passive"))
      (node (ref "C28") (pin "1") (pinfunction "1_1") (pintype "passive"))
      (node (ref "C29") (pin "1") (pinfunction "1_1") (pintype "passive"))
      (node (ref "C3") (pin "2") (pinfunction "2_2") (pintype "passive"))
      (node (ref "C30") (pin "-") (pinfunction "-_-") (pintype "passive"))
      (node (ref "C31") (pin "1") (pinfunction "1_1") (pintype "passive"))
      (node (ref "C32") (pin "2") (pinfunction "2_2") (pintype "passive"))
      (node (ref "C34") (pin "-") (pinfunction "-_-") (pintype "passive"))
      (node (ref "C35") (pin "1") (pinfunction "1_1") (pintype "passive"))
      (node (ref "C36") (pin "1") (pinfunction "1_1") (pintype "passive"))
      (node (ref "C38") (pin "1") (pinfunction "1_1") (pintype "passive"))
      (node (ref "C39") (pin "1") (pinfunction "1_1") (pintype "passive"))
      (node (ref "C4") (pin "-") (pinfunction "-_-") (pintype "passive"))
      (node (ref "C40") (pin "-") (pinfunction "-_-") (pintype "passive"))
      (node (ref "C42") (pin "1") (pinfunction "1_1") (pintype "passive"))
      (node (ref "C43") (pin "1") (pinfunction "1_1") (pintype "passive"))
      (node (ref "C44") (pin "-") (pinfunction "-_-") (pintype "passive"))
      (node (ref "C46") (pin "1") (pinfunction "1_1") (pintype "passive"))
      (node (ref "C47") (pin "1") (pinfunction "1_1") (pintype "passive"))
      (node (ref "C48") (pin "-") (pinfunction "-_-") (pintype "passive"))
      (node (ref "C9") (pin "1") (pinfunction "1_1") (pintype "passive"))
      (node (ref "I2C_1") (pin "5") (pinfunction "S_5") (pintype "passive"))
      (node (ref "I2C_10") (pin "5") (pinfunction "S_5") (pintype "passive"))
      (node (ref "I2C_2") (pin "5") (pinfunction "S_5") (pintype "passive"))
      (node (ref "I2C_3") (pin "5") (pinfunction "S_5") (pintype "passive"))
      (node (ref "I2C_4") (pin "5") (pinfunction "S_5") (pintype "passive"))
      (node (ref "I2C_5") (pin "5") (pinfunction "S_5") (pintype "passive"))
      (node (ref "I2C_6") (pin "5") (pinfunction "S_5") (pintype "passive"))
      (node (ref "I2C_7") (pin "5") (pinfunction "S_5") (pintype "passive"))
      (node (ref "I2C_8") (pin "5") (pinfunction "S_5") (pintype "passive"))
      (node (ref "I2C_9") (pin "5") (pinfunction "S_5") (pintype "passive"))
      (node (ref "I_UART_HUB_1") (pin "5") (pinfunction "S_5") (pintype "passive"))
      (node (ref "J1") (pin "-") (pinfunction "-_-") (pintype "bidirectional"))
      (node (ref "J1") (pin "CDN") (pinfunction "CDN_CDN") (pintype "bidirectional"))
      (node (ref "J10") (pin "14") (pinfunction "14_14") (pintype "passive"))
      (node (ref "J10") (pin "15") (pinfunction "15_15") (pintype "passive"))
      (node (ref "J10") (pin "16") (pinfunction "16_16") (pintype "passive"))
      (node (ref "J11") (pin "14") (pinfunction "14_14") (pintype "passive"))
      (node (ref "J11") (pin "15") (pinfunction "15_15") (pintype "passive"))
      (node (ref "J11") (pin "16") (pinfunction "16_16") (pintype "passive"))
      (node (ref "J2") (pin "6") (pinfunction "VSS_6") (pintype "bidirectional"))
      (node (ref "J2") (pin "G1") (pinfunction "G1_G1") (pintype "bidirectional"))
      (node (ref "J2") (pin "G2") (pinfunction "G2_G2") (pintype "bidirectional"))
      (node (ref "J2") (pin "G3") (pinfunction "G3_G3") (pintype "bidirectional"))
      (node (ref "J2") (pin "G4") (pinfunction "G4_G4") (pintype "bidirectional"))
      (node (ref "J3") (pin "2") (pinfunction "2_2") (pintype "bidirectional"))
      (node (ref "J7") (pin "15") (pinfunction "15_15") (pintype "passive"))
      (node (ref "J7") (pin "16") (pinfunction "16_16") (pintype "passive"))
      (node (ref "J8") (pin "2") (pinfunction "2_2") (pintype "bidirectional"))
      (node (ref "J9") (pin "15") (pinfunction "15_15") (pintype "passive"))
      (node (ref "J9") (pin "16") (pinfunction "16_16") (pintype "passive"))
      (node (ref "L3") (pin "1") (pinfunction "1_1") (pintype "passive"))
      (node (ref "LOPY_I2C") (pin "5") (pinfunction "S_5") (pintype "passive"))
      (node (ref "LOPY_SPI") (pin "7") (pinfunction "S_7") (pintype "passive"))
      (node (ref "LOPY_UART0") (pin "5") (pinfunction "S_5") (pintype "passive"))
      (node (ref "LOPY_UART1") (pin "5") (pinfunction "S_5") (pintype "passive"))
      (node (ref "PCB1") (pin "P$14") (pinfunction "GND_P$14") (pintype "bidirectional"))
      (node (ref "PCB1") (pin "P$20") (pinfunction "GND_P$20") (pintype "bidirectional"))
      (node (ref "PCB1") (pin "P$25") (pinfunction "GND_P$25") (pintype "bidirectional"))
      (node (ref "PCB1") (pin "P$30") (pinfunction "GND_P$30") (pintype "bidirectional"))
      (node (ref "PCB1") (pin "P$34") (pinfunction "GND_P$34") (pintype "bidirectional"))
      (node (ref "PCB1") (pin "P$39") (pinfunction "GND_P$39") (pintype "bidirectional"))
      (node (ref "PCB1") (pin "P$6") (pinfunction "GND_P$6") (pintype "bidirectional"))
      (node (ref "PCB1") (pin "P$9") (pinfunction "GND_P$9") (pintype "bidirectional"))
      (node (ref "PI_RS_485") (pin "5") (pinfunction "S_5") (pintype "passive"))
      (node (ref "PI_UART") (pin "5") (pinfunction "S_5") (pintype "passive"))
      (node (ref "PI_UART_HUB_2") (pin "5") (pinfunction "S_5") (pintype "passive"))
      (node (ref "PI_UART_HUB_3") (pin "5") (pinfunction "S_5") (pintype "passive"))
      (node (ref "Q3") (pin "2") (pinfunction "S_2") (pintype "passive"))
      (node (ref "Q4") (pin "2") (pinfunction "S_2") (pintype "passive"))
      (node (ref "Q5") (pin "1") (pinfunction "G_1") (pintype "passive"))
      (node (ref "Q6") (pin "2") (pinfunction "S_2") (pintype "passive"))
      (node (ref "Q7") (pin "2") (pinfunction "S_2") (pintype "passive"))
      (node (ref "R20") (pin "1") (pinfunction "1_1") (pintype "passive"))
      (node (ref "R28") (pin "1") (pinfunction "1_1") (pintype "passive"))
      (node (ref "R40") (pin "1") (pinfunction "1_1") (pintype "passive"))
      (node (ref "R43") (pin "1") (pinfunction "1_1") (pintype "passive"))
      (node (ref "R44") (pin "1") (pinfunction "1_1") (pintype "passive"))
      (node (ref "R45") (pin "1") (pinfunction "1_1") (pintype "passive"))
      (node (ref "SPI_1") (pin "7") (pinfunction "S_7") (pintype "passive"))
      (node (ref "SPI_2") (pin "7") (pinfunction "S_7") (pintype "passive"))
      (node (ref "SPI_3") (pin "7") (pinfunction "S_7") (pintype "passive"))
      (node (ref "SPI_4") (pin "7") (pinfunction "S_7") (pintype "passive"))
      (node (ref "SPI_5") (pin "7") (pinfunction "S_7") (pintype "passive"))
      (node (ref "SPI_6") (pin "7") (pinfunction "S_7") (pintype "passive"))
      (node (ref "SPI_7") (pin "7") (pinfunction "S_7") (pintype "passive"))
      (node (ref "SPI_8") (pin "7") (pinfunction "S_7") (pintype "passive"))
      (node (ref "SW1") (pin "SS1") (pinfunction "SS1_SS1") (pintype "bidirectional"))
      (node (ref "SW1") (pin "SS2") (pinfunction "SS2_SS2") (pintype "bidirectional"))
      (node (ref "SW1") (pin "SS3") (pinfunction "SS3_SS3") (pintype "bidirectional"))
      (node (ref "SW1") (pin "SS4") (pinfunction "SS4_SS4") (pintype "bidirectional"))
      (node (ref "SW3") (pin "SS1") (pinfunction "SS1_SS1") (pintype "bidirectional"))
      (node (ref "SW3") (pin "SS2") (pinfunction "SS2_SS2") (pintype "bidirectional"))
      (node (ref "SW3") (pin "SS3") (pinfunction "SS3_SS3") (pintype "bidirectional"))
      (node (ref "SW3") (pin "SS4") (pinfunction "SS4_SS4") (pintype "bidirectional"))
      (node (ref "SW4") (pin "COM") (pinfunction "COM_COM") (pintype "bidirectional"))
      (node (ref "SW4") (pin "SS1") (pinfunction "SS1_SS1") (pintype "bidirectional"))
      (node (ref "SW4") (pin "SS2") (pinfunction "SS2_SS2") (pintype "bidirectional"))
      (node (ref "SW4") (pin "SS3") (pinfunction "SS3_SS3") (pintype "bidirectional"))
      (node (ref "SW4") (pin "SS4") (pinfunction "SS4_SS4") (pintype "bidirectional"))
      (node (ref "TP7") (pin "TP") (pinfunction "TP_TP") (pintype "input"))
      (node (ref "U$3") (pin "2") (pinfunction "C_2") (pintype "passive"))
      (node (ref "U$4") (pin "2") (pinfunction "ADJ/GND_2") (pintype "passive"))
      (node (ref "U$4") (pin "TAB") (pinfunction "TAB_TAB") (pintype "power_in"))
      (node (ref "U$5") (pin "IN-") (pinfunction "IN-_IN-") (pintype "bidirectional"))
      (node (ref "U$5") (pin "OUT-") (pinfunction "OUT-_OUT-") (pintype "bidirectional"))
      (node (ref "U$6") (pin "1") (pinfunction "VSS_1") (pintype "bidirectional"))
      (node (ref "U$7") (pin "4") (pinfunction "GND_4") (pintype "power_in"))
      (node (ref "U1") (pin "10") (pinfunction "VSS_10") (pintype "power_in"))
      (node (ref "U1") (pin "15") (pinfunction "A0_15") (pintype "input"))
      (node (ref "U1") (pin "16") (pinfunction "A1_16") (pintype "input"))
      (node (ref "U1") (pin "17") (pinfunction "A2_17") (pintype "input"))
      (node (ref "U10") (pin "8") (pinfunction "GND_8") (pintype "passive"))
      (node (ref "U12") (pin "5") (pinfunction "GND_5") (pintype "passive"))
      (node (ref "U13") (pin "18") (pinfunction "GND_18") (pintype "input"))
      (node (ref "U13") (pin "21") (pinfunction "GND_21") (pintype "input"))
      (node (ref "U13") (pin "25") (pinfunction "GND_25") (pintype "input"))
      (node (ref "U13") (pin "26") (pinfunction "TEST_26") (pintype "input"))
      (node (ref "U13") (pin "7") (pinfunction "GND_7") (pintype "input"))
      (node (ref "U14") (pin "18") (pinfunction "GND_18") (pintype "input"))
      (node (ref "U14") (pin "21") (pinfunction "GND_21") (pintype "input"))
      (node (ref "U14") (pin "25") (pinfunction "GND_25") (pintype "input"))
      (node (ref "U14") (pin "26") (pinfunction "TEST_26") (pintype "input"))
      (node (ref "U14") (pin "7") (pinfunction "GND_7") (pintype "input"))
      (node (ref "U15") (pin "18") (pinfunction "GND_18") (pintype "input"))
      (node (ref "U15") (pin "21") (pinfunction "GND_21") (pintype "input"))
      (node (ref "U15") (pin "25") (pinfunction "GND_25") (pintype "input"))
      (node (ref "U15") (pin "26") (pinfunction "TEST_26") (pintype "input"))
      (node (ref "U15") (pin "7") (pinfunction "GND_7") (pintype "input"))
      (node (ref "U2") (pin "4") (pinfunction "VSS_4") (pintype "power_in"))
      (node (ref "U3") (pin "P$27") (pinfunction "GND_P$27") (pintype "power_in"))
      (node (ref "U4") (pin "10") (pinfunction "GND_10") (pintype "passive"))
      (node (ref "U5") (pin "18") (pinfunction "GND_18") (pintype "input"))
      (node (ref "U5") (pin "21") (pinfunction "GND_21") (pintype "input"))
      (node (ref "U5") (pin "25") (pinfunction "GND_25") (pintype "input"))
      (node (ref "U5") (pin "26") (pinfunction "TEST_26") (pintype "input"))
      (node (ref "U5") (pin "7") (pinfunction "GND_7") (pintype "input"))
      (node (ref "U6") (pin "18") (pinfunction "GND_18") (pintype "input"))
      (node (ref "U6") (pin "21") (pinfunction "GND_21") (pintype "input"))
      (node (ref "U6") (pin "25") (pinfunction "GND_25") (pintype "input"))
      (node (ref "U6") (pin "26") (pinfunction "TEST_26") (pintype "input"))
      (node (ref "U6") (pin "7") (pinfunction "GND_7") (pintype "input"))
      (node (ref "U8") (pin "1") (pinfunction "A0_1") (pintype "input"))
      (node (ref "U8") (pin "2") (pinfunction "A1_2") (pintype "input"))
      (node (ref "U8") (pin "3") (pinfunction "A2_3") (pintype "input"))
      (node (ref "U8") (pin "4") (pinfunction "GND_4") (pintype "power_in"))
      (node (ref "USB1") (pin "5") (pinfunction "GND_5") (pintype "power_in"))
      (node (ref "USB1") (pin "P1") (pinfunction "SHIELD_P1") (pintype "power_in"))
      (node (ref "USB1") (pin "P2") (pinfunction "SHIELD_P2") (pintype "power_in"))
      (node (ref "USB1") (pin "P3") (pinfunction "SHIELD_P3") (pintype "power_in"))
      (node (ref "USB1") (pin "P4") (pinfunction "SHIELD_P4") (pintype "power_in"))
      (node (ref "USB1") (pin "P5") (pinfunction "SHIELD_P5") (pintype "power_in"))
      (node (ref "USB1") (pin "P6") (pinfunction "SHIELD_P6") (pintype "power_in"))
      (node (ref "USB3") (pin "5") (pinfunction "GND_5") (pintype "power_in"))
      (node (ref "USB3") (pin "P1") (pinfunction "SHIELD_P1") (pintype "power_in"))
      (node (ref "USB3") (pin "P2") (pinfunction "SHIELD_P2") (pintype "power_in"))
      (node (ref "USB3") (pin "P3") (pinfunction "SHIELD_P3") (pintype "power_in"))
      (node (ref "USB3") (pin "P4") (pinfunction "SHIELD_P4") (pintype "power_in"))
      (node (ref "USB3") (pin "P5") (pinfunction "SHIELD_P5") (pintype "power_in"))
      (node (ref "USB3") (pin "P6") (pinfunction "SHIELD_P6") (pintype "power_in"))
    )
    (net (code "37") (name "GNDA") (class "Default")
      (node (ref "C14") (pin "1") (pinfunction "1_1") (pintype "passive"))
      (node (ref "C5") (pin "-") (pinfunction "-_-") (pintype "passive"))
      (node (ref "C6") (pin "1") (pinfunction "1_1") (pintype "passive"))
      (node (ref "C7") (pin "1") (pinfunction "1_1") (pintype "passive"))
      (node (ref "C8") (pin "-") (pinfunction "-_-") (pintype "passive"))
      (node (ref "L3") (pin "2") (pinfunction "2_2") (pintype "passive"))
      (node (ref "PI_ADC_1") (pin "7") (pinfunction "S_7") (pintype "passive"))
      (node (ref "PI_ADC_2") (pin "7") (pinfunction "S_7") (pintype "passive"))
      (node (ref "PI_ADC_3") (pin "7") (pinfunction "S_7") (pintype "passive"))
      (node (ref "PI_ADC_4") (pin "7") (pinfunction "S_7") (pintype "passive"))
      (node (ref "U$1") (pin "10") (pinfunction "ADR1_10") (pintype "input"))
      (node (ref "U$1") (pin "5") (pinfunction "VSS_5") (pintype "power_in"))
      (node (ref "U$1") (pin "9") (pinfunction "ADR0_9") (pintype "input"))
      (node (ref "U$2") (pin "5") (pinfunction "VSS_5") (pintype "power_in"))
      (node (ref "U$2") (pin "9") (pinfunction "ADR0_9") (pintype "input"))
    )
    (net (code "38") (name "GPIO4") (class "Default")
      (node (ref "PCB1") (pin "P$7") (pinfunction "GPIO4_P$7") (pintype "bidirectional"))
      (node (ref "R16") (pin "1") (pinfunction "1_1") (pintype "passive"))
      (node (ref "U$7") (pin "2") (pinfunction "DAT_2") (pintype "bidirectional"))
    )
    (net (code "39") (name "GPIO12") (class "Default")
      (node (ref "PCB1") (pin "P$32") (pinfunction "GPIO12_P$32") (pintype "bidirectional"))
      (node (ref "U1") (pin "19") (pinfunction "INTB_19") (pintype "output"))
    )
    (net (code "40") (name "GPIO13") (class "Default")
      (node (ref "PCB1") (pin "P$33") (pinfunction "GPIO13_P$33") (pintype "bidirectional"))
      (node (ref "U1") (pin "20") (pinfunction "INTA_20") (pintype "output"))
    )
    (net (code "41") (name "GPIO16_FREE") (class "Default")
      (node (ref "J10") (pin "7") (pinfunction "7_7") (pintype "passive"))
      (node (ref "J11") (pin "7") (pinfunction "7_7") (pintype "passive"))
      (node (ref "PCB1") (pin "P$36") (pinfunction "GPIO16_P$36") (pintype "bidirectional"))
    )
    (net (code "42") (name "GPIO18_FREE") (class "Default")
      (node (ref "J10") (pin "8") (pinfunction "8_8") (pintype "passive"))
      (node (ref "J11") (pin "8") (pinfunction "8_8") (pintype "passive"))
      (node (ref "PCB1") (pin "P$12") (pinfunction "GPIO18_P$12") (pintype "bidirectional"))
    )
    (net (code "43") (name "GPIO19_FREE") (class "Default")
      (node (ref "J10") (pin "9") (pinfunction "9_9") (pintype "passive"))
      (node (ref "J11") (pin "9") (pinfunction "9_9") (pintype "passive"))
      (node (ref "PCB1") (pin "P$35") (pinfunction "GPIO19_P$35") (pintype "bidirectional"))
    )
    (net (code "44") (name "GPIO20_FREE") (class "Default")
      (node (ref "J10") (pin "10") (pinfunction "10_10") (pintype "passive"))
      (node (ref "J11") (pin "10") (pinfunction "10_10") (pintype "passive"))
      (node (ref "PCB1") (pin "P$38") (pinfunction "GPIO20_P$38") (pintype "bidirectional"))
    )
    (net (code "45") (name "GPIO21_FREE") (class "Default")
      (node (ref "J10") (pin "11") (pinfunction "11_11") (pintype "passive"))
      (node (ref "J11") (pin "11") (pinfunction "11_11") (pintype "passive"))
      (node (ref "PCB1") (pin "P$40") (pinfunction "GPIO21_P$40") (pintype "bidirectional"))
    )
    (net (code "46") (name "GPIO24_FREE") (class "Default")
      (node (ref "J10") (pin "12") (pinfunction "12_12") (pintype "passive"))
      (node (ref "J11") (pin "12") (pinfunction "12_12") (pintype "passive"))
      (node (ref "PCB1") (pin "P$18") (pinfunction "GPIO24_P$18") (pintype "bidirectional"))
    )
    (net (code "47") (name "GPIO25_FREE") (class "Default")
      (node (ref "J10") (pin "13") (pinfunction "13_13") (pintype "passive"))
      (node (ref "J11") (pin "13") (pinfunction "13_13") (pintype "passive"))
      (node (ref "PCB1") (pin "P$22") (pinfunction "GPIO25_P$22") (pintype "bidirectional"))
    )
    (net (code "48") (name "ID_SC") (class "Default")
      (node (ref "PCB1") (pin "P$28") (pinfunction "ID_SC*_P$28") (pintype "bidirectional"))
      (node (ref "R37") (pin "1") (pinfunction "1_1") (pintype "passive"))
      (node (ref "U8") (pin "6") (pinfunction "SCL_6") (pintype "bidirectional"))
    )
    (net (code "49") (name "ID_SD") (class "Default")
      (node (ref "PCB1") (pin "P$27") (pinfunction "ID_SD*_P$27") (pintype "bidirectional"))
      (node (ref "R38") (pin "1") (pinfunction "1_1") (pintype "passive"))
      (node (ref "U8") (pin "5") (pinfunction "SDA_5") (pintype "bidirectional"))
    )
    (net (code "50") (name "LED_GND") (class "Default")
      (node (ref "D10") (pin "-") (pinfunction "-_-") (pintype "passive"))
      (node (ref "D11") (pin "-") (pinfunction "-_-") (pintype "passive"))
      (node (ref "D12") (pin "-") (pinfunction "-_-") (pintype "passive"))
      (node (ref "D13") (pin "-") (pinfunction "-_-") (pintype "passive"))
      (node (ref "D14") (pin "-") (pinfunction "-_-") (pintype "passive"))
      (node (ref "D22") (pin "-") (pinfunction "-_-") (pintype "passive"))
      (node (ref "D4") (pin "-") (pinfunction "-_-") (pintype "passive"))
      (node (ref "D5") (pin "-") (pinfunction "-_-") (pintype "passive"))
      (node (ref "D6") (pin "-") (pinfunction "-_-") (pintype "passive"))
      (node (ref "D8") (pin "-") (pinfunction "-_-") (pintype "passive"))
      (node (ref "D9") (pin "-") (pinfunction "-_-") (pintype "passive"))
      (node (ref "SW4") (pin "B") (pinfunction "B_B") (pintype "bidirectional"))
    )
    (net (code "51") (name "LOPY_3V3") (class "Default")
      (node (ref "F59") (pin "1") (pinfunction "1_1") (pintype "bidirectional"))
      (node (ref "F75") (pin "1") (pinfunction "1_1") (pintype "bidirectional"))
      (node (ref "F79") (pin "1") (pinfunction "1_1") (pintype "bidirectional"))
      (node (ref "F81") (pin "1") (pinfunction "1_1") (pintype "bidirectional"))
      (node (ref "F83") (pin "1") (pinfunction "1_1") (pintype "bidirectional"))
      (node (ref "J2") (pin "4") (pinfunction "VDD_4") (pintype "bidirectional"))
      (node (ref "J4") (pin "1") (pinfunction "1_1") (pintype "bidirectional"))
      (node (ref "Q8") (pin "3") (pinfunction "D_3") (pintype "passive"))
      (node (ref "R22") (pin "2") (pinfunction "2_2") (pintype "passive"))
      (node (ref "R46") (pin "2") (pinfunction "2_2") (pintype "passive"))
      (node (ref "SW3") (pin "B") (pinfunction "B_B") (pintype "bidirectional"))
      (node (ref "U3") (pin "P$26") (pinfunction "3V3_P$26") (pintype "power_in"))
    )
    (net (code "52") (name "LOPY_CS1") (class "Default")
      (node (ref "LOPY_SPI") (pin "3") (pinfunction "S_3") (pintype "passive"))
      (node (ref "U3") (pin "P$10") (pinfunction "P8_P$10") (pintype "bidirectional"))
    )
    (net (code "53") (name "LOPY_CS2") (class "Default")
      (node (ref "J2") (pin "2") (pinfunction "CS_2") (pintype "bidirectional"))
      (node (ref "U3") (pin "P$16") (pinfunction "P14_P$16") (pintype "input"))
    )
    (net (code "54") (name "LOPY_MISO") (class "Default")
      (node (ref "J2") (pin "7") (pinfunction "DO_7") (pintype "bidirectional"))
      (node (ref "J4") (pin "2") (pinfunction "2_2") (pintype "bidirectional"))
      (node (ref "LOPY_SPI") (pin "5") (pinfunction "S_5") (pintype "passive"))
      (node (ref "Q8") (pin "2") (pinfunction "S_2") (pintype "passive"))
      (node (ref "U3") (pin "P$14") (pinfunction "P12_P$14") (pintype "bidirectional"))
    )
    (net (code "55") (name "LOPY_MOSI") (class "Default")
      (node (ref "J2") (pin "3") (pinfunction "DI_3") (pintype "bidirectional"))
      (node (ref "LOPY_SPI") (pin "4") (pinfunction "S_4") (pintype "passive"))
      (node (ref "U3") (pin "P$13") (pinfunction "P11_P$13") (pintype "bidirectional"))
    )
    (net (code "56") (name "LOPY_P2") (class "Default")
      (node (ref "J3") (pin "1") (pinfunction "1_1") (pintype "bidirectional"))
      (node (ref "Q6") (pin "3") (pinfunction "D_3") (pintype "passive"))
      (node (ref "U3") (pin "P$4") (pinfunction "P2_P$4") (pintype "bidirectional"))
    )
    (net (code "57") (name "LOPY_P15") (class "Default")
      (node (ref "J7") (pin "14") (pinfunction "14_14") (pintype "passive"))
      (node (ref "J9") (pin "14") (pinfunction "14_14") (pintype "passive"))
      (node (ref "U3") (pin "P$17") (pinfunction "P15_P$17") (pintype "input"))
    )
    (net (code "58") (name "LOPY_P16") (class "Default")
      (node (ref "J7") (pin "13") (pinfunction "13_13") (pintype "passive"))
      (node (ref "J9") (pin "13") (pinfunction "13_13") (pintype "passive"))
      (node (ref "U3") (pin "P$18") (pinfunction "P16_P$18") (pintype "input"))
    )
    (net (code "59") (name "LOPY_P17") (class "Default")
      (node (ref "J7") (pin "12") (pinfunction "12_12") (pintype "passive"))
      (node (ref "J9") (pin "12") (pinfunction "12_12") (pintype "passive"))
      (node (ref "U3") (pin "P$19") (pinfunction "P17_P$19") (pintype "input"))
    )
    (net (code "60") (name "LOPY_P18") (class "Default")
      (node (ref "J7") (pin "11") (pinfunction "11_11") (pintype "passive"))
      (node (ref "J9") (pin "11") (pinfunction "11_11") (pintype "passive"))
      (node (ref "U3") (pin "P$20") (pinfunction "P18_P$20") (pintype "input"))
    )
    (net (code "61") (name "LOPY_P19") (class "Default")
      (node (ref "J7") (pin "10") (pinfunction "10_10") (pintype "passive"))
      (node (ref "J9") (pin "10") (pinfunction "10_10") (pintype "passive"))
      (node (ref "U3") (pin "P$21") (pinfunction "P19_P$21") (pintype "bidirectional"))
    )
    (net (code "62") (name "LOPY_P20") (class "Default")
      (node (ref "J7") (pin "9") (pinfunction "9_9") (pintype "passive"))
      (node (ref "J9") (pin "9") (pinfunction "9_9") (pintype "passive"))
      (node (ref "U3") (pin "P$22") (pinfunction "P20_P$22") (pintype "bidirectional"))
    )
    (net (code "63") (name "LOPY_P21") (class "Default")
      (node (ref "J7") (pin "8") (pinfunction "8_8") (pintype "passive"))
      (node (ref "J9") (pin "8") (pinfunction "8_8") (pintype "passive"))
      (node (ref "U3") (pin "P$23") (pinfunction "P21_P$23") (pintype "bidirectional"))
    )
    (net (code "64") (name "LOPY_P22") (class "Default")
      (node (ref "J7") (pin "7") (pinfunction "7_7") (pintype "passive"))
      (node (ref "J9") (pin "7") (pinfunction "7_7") (pintype "passive"))
      (node (ref "U3") (pin "P$24") (pinfunction "P22_P$24") (pintype "bidirectional"))
    )
    (net (code "65") (name "LOPY_P23") (class "Default")
      (node (ref "J7") (pin "6") (pinfunction "6_6") (pintype "passive"))
      (node (ref "J9") (pin "6") (pinfunction "6_6") (pintype "passive"))
      (node (ref "U3") (pin "P$25") (pinfunction "P23_P$25") (pintype "bidirectional"))
    )
    (net (code "66") (name "LOPY_RST_EN") (class "Default")
      (node (ref "PCB1") (pin "P$37") (pinfunction "GPIO26_P$37") (pintype "bidirectional"))
      (node (ref "R15") (pin "1") (pinfunction "1_1") (pintype "passive"))
    )
    (net (code "67") (name "LOPY_RXD0") (class "Default")
      (node (ref "LOPY_UART0") (pin "4") (pinfunction "S_4") (pintype "passive"))
      (node (ref "R13") (pin "2") (pinfunction "2_2") (pintype "passive"))
      (node (ref "R8") (pin "1") (pinfunction "1_1") (pintype "passive"))
      (node (ref "U3") (pin "P$2") (pinfunction "P0_P$2") (pintype "bidirectional"))
    )
    (net (code "68") (name "LOPY_RXD1") (class "Default")
      (node (ref "LOPY_UART1") (pin "4") (pinfunction "S_4") (pintype "passive"))
      (node (ref "U3") (pin "P$6") (pinfunction "P4_P$6") (pintype "bidirectional"))
    )
    (net (code "69") (name "LOPY_SCL{slash}CLK") (class "Default")
      (node (ref "J2") (pin "5") (pinfunction "SCLK_5") (pintype "bidirectional"))
      (node (ref "LOPY_I2C") (pin "4") (pinfunction "S_4") (pintype "passive"))
      (node (ref "LOPY_SPI") (pin "6") (pinfunction "S_6") (pintype "passive"))
      (node (ref "U3") (pin "P$12") (pinfunction "P10_P$12") (pintype "bidirectional"))
    )
    (net (code "70") (name "LOPY_SDA") (class "Default")
      (node (ref "LOPY_I2C") (pin "3") (pinfunction "S_3") (pintype "passive"))
      (node (ref "U3") (pin "P$11") (pinfunction "P9_P$11") (pintype "bidirectional"))
    )
    (net (code "71") (name "LOPY_TXD0") (class "Default")
      (node (ref "LOPY_UART0") (pin "3") (pinfunction "S_3") (pintype "passive"))
      (node (ref "R12") (pin "1") (pinfunction "1_1") (pintype "passive"))
      (node (ref "R14") (pin "2") (pinfunction "2_2") (pintype "passive"))
      (node (ref "U3") (pin "P$3") (pinfunction "P1_P$3") (pintype "bidirectional"))
    )
    (net (code "72") (name "LOPY_TXD1") (class "Default")
      (node (ref "LOPY_UART1") (pin "3") (pinfunction "S_3") (pintype "passive"))
      (node (ref "U3") (pin "P$5") (pinfunction "P3_P$5") (pintype "bidirectional"))
    )
    (net (code "73") (name "LOPY_USB_5V") (class "Default")
      (node (ref "C15") (pin "2") (pinfunction "2_2") (pintype "passive"))
      (node (ref "C17") (pin "+") (pinfunction "+_+") (pintype "passive"))
      (node (ref "L1") (pin "2") (pinfunction "2_2") (pintype "passive"))
      (node (ref "R1") (pin "1") (pinfunction "1_1") (pintype "passive"))
      (node (ref "R11") (pin "2") (pinfunction "2_2") (pintype "passive"))
      (node (ref "R3") (pin "1") (pinfunction "1_1") (pintype "passive"))
      (node (ref "TP5") (pin "TP") (pinfunction "TP_TP") (pintype "input"))
      (node (ref "U6") (pin "20") (pinfunction "VCC_20") (pintype "input"))
      (node (ref "U6") (pin "4") (pinfunction "VCCIO_4") (pintype "input"))
    )
    (net (code "74") (name "Net-(D1-Pad+)") (class "Default")
      (node (ref "D1") (pin "+") (pinfunction "+_+") (pintype "passive"))
      (node (ref "F1") (pin "P$2") (pinfunction "P$2_P$2") (pintype "passive"))
      (node (ref "TP8") (pin "TP") (pinfunction "TP_TP") (pintype "input"))
    )
    (net (code "75") (name "Net-(D2-Pad+)") (class "Default")
      (node (ref "D2") (pin "+") (pinfunction "+_+") (pintype "passive"))
      (node (ref "R1") (pin "2") (pinfunction "2_2") (pintype "passive"))
    )
    (net (code "76") (name "Net-(D3-Pad+)") (class "Default")
      (node (ref "D3") (pin "+") (pinfunction "+_+") (pintype "passive"))
      (node (ref "R3") (pin "2") (pinfunction "2_2") (pintype "passive"))
    )
    (net (code "77") (name "Net-(D4-Pad+)") (class "Default")
      (node (ref "D4") (pin "+") (pinfunction "+_+") (pintype "passive"))
      (node (ref "R5") (pin "1") (pinfunction "1_1") (pintype "passive"))
    )
    (net (code "78") (name "Net-(D5-Pad+)") (class "Default")
      (node (ref "D5") (pin "+") (pinfunction "+_+") (pintype "passive"))
      (node (ref "R6") (pin "1") (pinfunction "1_1") (pintype "passive"))
    )
    (net (code "79") (name "Net-(D6-Pad+)") (class "Default")
      (node (ref "D6") (pin "+") (pinfunction "+_+") (pintype "passive"))
      (node (ref "R7") (pin "1") (pinfunction "1_1") (pintype "passive"))
    )
    (net (code "80") (name "Net-(D7-Pad+)") (class "Default")
      (node (ref "D7") (pin "+") (pinfunction "+_+") (pintype "passive"))
      (node (ref "R23") (pin "2") (pinfunction "2_2") (pintype "passive"))
    )
    (net (code "81") (name "Net-(D8-Pad+)") (class "Default")
      (node (ref "D8") (pin "+") (pinfunction "+_+") (pintype "passive"))
      (node (ref "R9") (pin "1") (pinfunction "1_1") (pintype "passive"))
    )
    (net (code "82") (name "Net-(D9-Pad+)") (class "Default")
      (node (ref "D9") (pin "+") (pinfunction "+_+") (pintype "passive"))
      (node (ref "R10") (pin "1") (pinfunction "1_1") (pintype "passive"))
    )
    (net (code "83") (name "Net-(D10-Pad+)") (class "Default")
      (node (ref "D10") (pin "+") (pinfunction "+_+") (pintype "passive"))
      (node (ref "R11") (pin "1") (pinfunction "1_1") (pintype "passive"))
    )
    (net (code "84") (name "Net-(D11-Pad+)") (class "Default")
      (node (ref "D11") (pin "+") (pinfunction "+_+") (pintype "passive"))
      (node (ref "R35") (pin "1") (pinfunction "1_1") (pintype "passive"))
    )
    (net (code "85") (name "Net-(D12-Pad+)") (class "Default")
      (node (ref "D12") (pin "+") (pinfunction "+_+") (pintype "passive"))
      (node (ref "R42") (pin "1") (pinfunction "1_1") (pintype "passive"))
    )
    (net (code "86") (name "Net-(D13-Pad+)") (class "Default")
      (node (ref "D13") (pin "+") (pinfunction "+_+") (pintype "passive"))
      (node (ref "R21") (pin "1") (pinfunction "1_1") (pintype "passive"))
    )
    (net (code "87") (name "Net-(D14-Pad+)") (class "Default")
      (node (ref "D14") (pin "+") (pinfunction "+_+") (pintype "passive"))
      (node (ref "R22") (pin "1") (pinfunction "1_1") (pintype "passive"))
    )
    (net (code "88") (name "Net-(D15-Pad+)") (class "Default")
      (node (ref "D15") (pin "+") (pinfunction "+_+") (pintype "passive"))
      (node (ref "R24") (pin "2") (pinfunction "2_2") (pintype "passive"))
    )
    (net (code "89") (name "Net-(D16-Pad+)") (class "Default")
      (node (ref "D16") (pin "+") (pinfunction "+_+") (pintype "passive"))
      (node (ref "R29") (pin "2") (pinfunction "2_2") (pintype "passive"))
    )
    (net (code "90") (name "Net-(D17-Pad+)") (class "Default")
      (node (ref "D17") (pin "+") (pinfunction "+_+") (pintype "passive"))
      (node (ref "R30") (pin "2") (pinfunction "2_2") (pintype "passive"))
    )
    (net (code "91") (name "Net-(D18-Pad+)") (class "Default")
      (node (ref "D18") (pin "+") (pinfunction "+_+") (pintype "passive"))
      (node (ref "R31") (pin "2") (pinfunction "2_2") (pintype "passive"))
    )
    (net (code "92") (name "Net-(D19-Pad+)") (class "Default")
      (node (ref "D19") (pin "+") (pinfunction "+_+") (pintype "passive"))
      (node (ref "R32") (pin "2") (pinfunction "2_2") (pintype "passive"))
    )
    (net (code "93") (name "Net-(D20-Pad+)") (class "Default")
      (node (ref "D20") (pin "+") (pinfunction "+_+") (pintype "passive"))
      (node (ref "R33") (pin "2") (pinfunction "2_2") (pintype "passive"))
    )
    (net (code "94") (name "Net-(D21-Pad+)") (class "Default")
      (node (ref "D21") (pin "+") (pinfunction "+_+") (pintype "passive"))
      (node (ref "R34") (pin "2") (pinfunction "2_2") (pintype "passive"))
    )
    (net (code "95") (name "Net-(D22-Pad+)") (class "Default")
      (node (ref "D22") (pin "+") (pinfunction "+_+") (pintype "passive"))
      (node (ref "R4") (pin "1") (pinfunction "1_1") (pintype "passive"))
    )
    (net (code "96") (name "Net-(F59-Pad2)") (class "Default")
      (node (ref "F59") (pin "2") (pinfunction "2_2") (pintype "bidirectional"))
      (node (ref "J7") (pin "3") (pinfunction "3_3") (pintype "passive"))
      (node (ref "J7") (pin "4") (pinfunction "4_4") (pintype "passive"))
      (node (ref "J7") (pin "5") (pinfunction "5_5") (pintype "passive"))
      (node (ref "J9") (pin "3") (pinfunction "3_3") (pintype "passive"))
      (node (ref "J9") (pin "4") (pinfunction "4_4") (pintype "passive"))
      (node (ref "J9") (pin "5") (pinfunction "5_5") (pintype "passive"))
    )
    (net (code "97") (name "Net-(F60-Pad2)") (class "Default")
      (node (ref "F60") (pin "2") (pinfunction "2_2") (pintype "bidirectional"))
      (node (ref "J10") (pin "1") (pinfunction "1_1") (pintype "passive"))
      (node (ref "J10") (pin "2") (pinfunction "2_2") (pintype "passive"))
      (node (ref "J10") (pin "3") (pinfunction "3_3") (pintype "passive"))
      (node (ref "J11") (pin "1") (pinfunction "1_1") (pintype "passive"))
      (node (ref "J11") (pin "2") (pinfunction "2_2") (pintype "passive"))
      (node (ref "J11") (pin "3") (pinfunction "3_3") (pintype "passive"))
    )
    (net (code "98") (name "Net-(F62-Pad2)") (class "Default")
      (node (ref "F62") (pin "2") (pinfunction "2_2") (pintype "bidirectional"))
      (node (ref "J10") (pin "4") (pinfunction "4_4") (pintype "passive"))
      (node (ref "J10") (pin "5") (pinfunction "5_5") (pintype "passive"))
      (node (ref "J10") (pin "6") (pinfunction "6_6") (pintype "passive"))
      (node (ref "J11") (pin "4") (pinfunction "4_4") (pintype "passive"))
      (node (ref "J11") (pin "5") (pinfunction "5_5") (pintype "passive"))
      (node (ref "J11") (pin "6") (pinfunction "6_6") (pintype "passive"))
    )
    (net (code "99") (name "Net-(F76-Pad2)") (class "Default")
      (node (ref "F76") (pin "2") (pinfunction "2_2") (pintype "bidirectional"))
      (node (ref "J7") (pin "1") (pinfunction "1_1") (pintype "passive"))
      (node (ref "J7") (pin "2") (pinfunction "2_2") (pintype "passive"))
      (node (ref "J9") (pin "1") (pinfunction "1_1") (pintype "passive"))
      (node (ref "J9") (pin "2") (pinfunction "2_2") (pintype "passive"))
    )
    (net (code "100") (name "Net-(I2C_1A-S)") (class "Default")
      (node (ref "F5") (pin "2") (pinfunction "2_2") (pintype "bidirectional"))
      (node (ref "I2C_1") (pin "1") (pinfunction "S_1") (pintype "passive"))
    )
    (net (code "101") (name "Net-(I2C_1B-S)") (class "Default")
      (node (ref "F6") (pin "2") (pinfunction "2_2") (pintype "bidirectional"))
      (node (ref "I2C_1") (pin "2") (pinfunction "S_2") (pintype "passive"))
    )
    (net (code "102") (name "Net-(I2C_2A-S)") (class "Default")
      (node (ref "F7") (pin "2") (pinfunction "2_2") (pintype "bidirectional"))
      (node (ref "I2C_2") (pin "1") (pinfunction "S_1") (pintype "passive"))
    )
    (net (code "103") (name "Net-(I2C_2B-S)") (class "Default")
      (node (ref "F8") (pin "2") (pinfunction "2_2") (pintype "bidirectional"))
      (node (ref "I2C_2") (pin "2") (pinfunction "S_2") (pintype "passive"))
    )
    (net (code "104") (name "Net-(I2C_3A-S)") (class "Default")
      (node (ref "F9") (pin "2") (pinfunction "2_2") (pintype "bidirectional"))
      (node (ref "I2C_3") (pin "1") (pinfunction "S_1") (pintype "passive"))
    )
    (net (code "105") (name "Net-(I2C_3B-S)") (class "Default")
      (node (ref "F10") (pin "2") (pinfunction "2_2") (pintype "bidirectional"))
      (node (ref "I2C_3") (pin "2") (pinfunction "S_2") (pintype "passive"))
    )
    (net (code "106") (name "Net-(I2C_4A-S)") (class "Default")
      (node (ref "F11") (pin "2") (pinfunction "2_2") (pintype "bidirectional"))
      (node (ref "I2C_4") (pin "1") (pinfunction "S_1") (pintype "passive"))
    )
    (net (code "107") (name "Net-(I2C_4B-S)") (class "Default")
      (node (ref "F12") (pin "2") (pinfunction "2_2") (pintype "bidirectional"))
      (node (ref "I2C_4") (pin "2") (pinfunction "S_2") (pintype "passive"))
    )
    (net (code "108") (name "Net-(I2C_5A-S)") (class "Default")
      (node (ref "F13") (pin "2") (pinfunction "2_2") (pintype "bidirectional"))
      (node (ref "I2C_5") (pin "1") (pinfunction "S_1") (pintype "passive"))
    )
    (net (code "109") (name "Net-(I2C_5B-S)") (class "Default")
      (node (ref "F14") (pin "2") (pinfunction "2_2") (pintype "bidirectional"))
      (node (ref "I2C_5") (pin "2") (pinfunction "S_2") (pintype "passive"))
    )
    (net (code "110") (name "Net-(I2C_6A-S)") (class "Default")
      (node (ref "F15") (pin "2") (pinfunction "2_2") (pintype "bidirectional"))
      (node (ref "I2C_6") (pin "1") (pinfunction "S_1") (pintype "passive"))
    )
    (net (code "111") (name "Net-(I2C_6B-S)") (class "Default")
      (node (ref "F16") (pin "2") (pinfunction "2_2") (pintype "bidirectional"))
      (node (ref "I2C_6") (pin "2") (pinfunction "S_2") (pintype "passive"))
    )
    (net (code "112") (name "Net-(I2C_7A-S)") (class "Default")
      (node (ref "F17") (pin "2") (pinfunction "2_2") (pintype "bidirectional"))
      (node (ref "I2C_7") (pin "1") (pinfunction "S_1") (pintype "passive"))
    )
    (net (code "113") (name "Net-(I2C_7B-S)") (class "Default")
      (node (ref "F18") (pin "2") (pinfunction "2_2") (pintype "bidirectional"))
      (node (ref "I2C_7") (pin "2") (pinfunction "S_2") (pintype "passive"))
    )
    (net (code "114") (name "Net-(I2C_8A-S)") (class "Default")
      (node (ref "F19") (pin "2") (pinfunction "2_2") (pintype "bidirectional"))
      (node (ref "I2C_8") (pin "1") (pinfunction "S_1") (pintype "passive"))
    )
    (net (code "115") (name "Net-(I2C_8B-S)") (class "Default")
      (node (ref "F20") (pin "2") (pinfunction "2_2") (pintype "bidirectional"))
      (node (ref "I2C_8") (pin "2") (pinfunction "S_2") (pintype "passive"))
    )
    (net (code "116") (name "Net-(I2C_9A-S)") (class "Default")
      (node (ref "F21") (pin "2") (pinfunction "2_2") (pintype "bidirectional"))
      (node (ref "I2C_9") (pin "1") (pinfunction "S_1") (pintype "passive"))
    )
    (net (code "117") (name "Net-(I2C_9B-S)") (class "Default")
      (node (ref "F22") (pin "2") (pinfunction "2_2") (pintype "bidirectional"))
      (node (ref "I2C_9") (pin "2") (pinfunction "S_2") (pintype "passive"))
    )
    (net (code "118") (name "Net-(I2C_10A-S)") (class "Default")
      (node (ref "F36") (pin "2") (pinfunction "2_2") (pintype "bidirectional"))
      (node (ref "I2C_10") (pin "1") (pinfunction "S_1") (pintype "passive"))
    )
    (net (code "119") (name "Net-(I2C_10B-S)") (class "Default")
      (node (ref "F37") (pin "2") (pinfunction "2_2") (pintype "bidirectional"))
      (node (ref "I2C_10") (pin "2") (pinfunction "S_2") (pintype "passive"))
    )
    (net (code "120") (name "Net-(I_UART_HUB_1A-S)") (class "Default")
      (node (ref "F48") (pin "2") (pinfunction "2_2") (pintype "bidirectional"))
      (node (ref "I_UART_HUB_1") (pin "1") (pinfunction "S_1") (pintype "passive"))
    )
    (net (code "121") (name "Net-(I_UART_HUB_1B-S)") (class "Default")
      (node (ref "F49") (pin "2") (pinfunction "2_2") (pintype "bidirectional"))
      (node (ref "I_UART_HUB_1") (pin "2") (pinfunction "S_2") (pintype "passive"))
    )
    (net (code "122") (name "Net-(LOPY_I2CA-S)") (class "Default")
      (node (ref "F82") (pin "2") (pinfunction "2_2") (pintype "bidirectional"))
      (node (ref "LOPY_I2C") (pin "1") (pinfunction "S_1") (pintype "passive"))
    )
    (net (code "123") (name "Net-(LOPY_I2CB-S)") (class "Default")
      (node (ref "F83") (pin "2") (pinfunction "2_2") (pintype "bidirectional"))
      (node (ref "LOPY_I2C") (pin "2") (pinfunction "S_2") (pintype "passive"))
    )
    (net (code "124") (name "Net-(LOPY_SPIA-S)") (class "Default")
      (node (ref "F74") (pin "2") (pinfunction "2_2") (pintype "bidirectional"))
      (node (ref "LOPY_SPI") (pin "1") (pinfunction "S_1") (pintype "passive"))
    )
    (net (code "125") (name "Net-(LOPY_SPIB-S)") (class "Default")
      (node (ref "F75") (pin "2") (pinfunction "2_2") (pintype "bidirectional"))
      (node (ref "LOPY_SPI") (pin "2") (pinfunction "S_2") (pintype "passive"))
    )
    (net (code "126") (name "Net-(LOPY_UART0A-S)") (class "Default")
      (node (ref "F78") (pin "2") (pinfunction "2_2") (pintype "bidirectional"))
      (node (ref "LOPY_UART0") (pin "1") (pinfunction "S_1") (pintype "passive"))
    )
    (net (code "127") (name "Net-(LOPY_UART0B-S)") (class "Default")
      (node (ref "F79") (pin "2") (pinfunction "2_2") (pintype "bidirectional"))
      (node (ref "LOPY_UART0") (pin "2") (pinfunction "S_2") (pintype "passive"))
    )
    (net (code "128") (name "Net-(LOPY_UART1A-S)") (class "Default")
      (node (ref "F80") (pin "2") (pinfunction "2_2") (pintype "bidirectional"))
      (node (ref "LOPY_UART1") (pin "1") (pinfunction "S_1") (pintype "passive"))
    )
    (net (code "129") (name "Net-(LOPY_UART1B-S)") (class "Default")
      (node (ref "F81") (pin "2") (pinfunction "2_2") (pintype "bidirectional"))
      (node (ref "LOPY_UART1") (pin "2") (pinfunction "S_2") (pintype "passive"))
    )
    (net (code "130") (name "Net-(PCB1-GPIO5)") (class "Default")
      (node (ref "PCB1") (pin "P$29") (pinfunction "GPIO5_P$29") (pintype "bidirectional"))
      (node (ref "R41") (pin "2") (pinfunction "2_2") (pintype "passive"))
    )
    (net (code "131") (name "Net-(PCB1-GPIO6)") (class "Default")
      (node (ref "PCB1") (pin "P$31") (pinfunction "GPIO6_P$31") (pintype "bidirectional"))
      (node (ref "R17") (pin "2") (pinfunction "2_2") (pintype "passive"))
    )
    (net (code "132") (name "Net-(PI_ADC_1A-S)") (class "Default")
      (node (ref "F40") (pin "2") (pinfunction "2_2") (pintype "bidirectional"))
      (node (ref "PI_ADC_1") (pin "1") (pinfunction "S_1") (pintype "passive"))
    )
    (net (code "133") (name "Net-(PI_ADC_1B-S)") (class "Default")
      (node (ref "F41") (pin "2") (pinfunction "2_2") (pintype "bidirectional"))
      (node (ref "PI_ADC_1") (pin "2") (pinfunction "S_2") (pintype "passive"))
    )
    (net (code "134") (name "Net-(PI_ADC_2A-S)") (class "Default")
      (node (ref "F38") (pin "2") (pinfunction "2_2") (pintype "bidirectional"))
      (node (ref "PI_ADC_2") (pin "1") (pinfunction "S_1") (pintype "passive"))
    )
    (net (code "135") (name "Net-(PI_ADC_2B-S)") (class "Default")
      (node (ref "F39") (pin "2") (pinfunction "2_2") (pintype "bidirectional"))
      (node (ref "PI_ADC_2") (pin "2") (pinfunction "S_2") (pintype "passive"))
    )
    (net (code "136") (name "Net-(PI_ADC_3A-S)") (class "Default")
      (node (ref "F42") (pin "2") (pinfunction "2_2") (pintype "bidirectional"))
      (node (ref "PI_ADC_3") (pin "1") (pinfunction "S_1") (pintype "passive"))
    )
    (net (code "137") (name "Net-(PI_ADC_3B-S)") (class "Default")
      (node (ref "F43") (pin "2") (pinfunction "2_2") (pintype "bidirectional"))
      (node (ref "PI_ADC_3") (pin "2") (pinfunction "S_2") (pintype "passive"))
    )
    (net (code "138") (name "Net-(PI_ADC_4A-S)") (class "Default")
      (node (ref "F44") (pin "2") (pinfunction "2_2") (pintype "bidirectional"))
      (node (ref "PI_ADC_4") (pin "1") (pinfunction "S_1") (pintype "passive"))
    )
    (net (code "139") (name "Net-(PI_ADC_4B-S)") (class "Default")
      (node (ref "F45") (pin "2") (pinfunction "2_2") (pintype "bidirectional"))
      (node (ref "PI_ADC_4") (pin "2") (pinfunction "S_2") (pintype "passive"))
    )
    (net (code "140") (name "Net-(PI_RS_485A-S)") (class "Default")
      (node (ref "F46") (pin "2") (pinfunction "2_2") (pintype "bidirectional"))
      (node (ref "PI_RS_485") (pin "1") (pinfunction "S_1") (pintype "passive"))
    )
    (net (code "141") (name "Net-(PI_RS_485B-S)") (class "Default")
      (node (ref "F47") (pin "2") (pinfunction "2_2") (pintype "bidirectional"))
      (node (ref "PI_RS_485") (pin "2") (pinfunction "S_2") (pintype "passive"))
    )
    (net (code "142") (name "Net-(PI_UARTA-S)") (class "Default")
      (node (ref "F50") (pin "2") (pinfunction "2_2") (pintype "bidirectional"))
      (node (ref "PI_UART") (pin "1") (pinfunction "S_1") (pintype "passive"))
    )
    (net (code "143") (name "Net-(PI_UARTB-S)") (class "Default")
      (node (ref "F51") (pin "2") (pinfunction "2_2") (pintype "bidirectional"))
      (node (ref "PI_UART") (pin "2") (pinfunction "S_2") (pintype "passive"))
    )
    (net (code "144") (name "Net-(PI_UART_HUB_2A-S)") (class "Default")
      (node (ref "F52") (pin "2") (pinfunction "2_2") (pintype "bidirectional"))
      (node (ref "PI_UART_HUB_2") (pin "1") (pinfunction "S_1") (pintype "passive"))
    )
    (net (code "145") (name "Net-(PI_UART_HUB_2B-S)") (class "Default")
      (node (ref "F53") (pin "2") (pinfunction "2_2") (pintype "bidirectional"))
      (node (ref "PI_UART_HUB_2") (pin "2") (pinfunction "S_2") (pintype "passive"))
    )
    (net (code "146") (name "Net-(PI_UART_HUB_3A-S)") (class "Default")
      (node (ref "F54") (pin "2") (pinfunction "2_2") (pintype "bidirectional"))
      (node (ref "PI_UART_HUB_3") (pin "1") (pinfunction "S_1") (pintype "passive"))
    )
    (net (code "147") (name "Net-(PI_UART_HUB_3B-S)") (class "Default")
      (node (ref "F55") (pin "2") (pinfunction "2_2") (pintype "bidirectional"))
      (node (ref "PI_UART_HUB_3") (pin "2") (pinfunction "S_2") (pintype "passive"))
    )
    (net (code "148") (name "Net-(Q2-G)") (class "Default")
      (node (ref "Q2") (pin "1") (pinfunction "G_1") (pintype "passive"))
      (node (ref "Q4") (pin "3") (pinfunction "D_3") (pintype "passive"))
      (node (ref "R39") (pin "1") (pinfunction "1_1") (pintype "passive"))
      (node (ref "TP12") (pin "TP") (pinfunction "TP_TP") (pintype "input"))
    )
    (net (code "149") (name "Net-(Q2-S)") (class "Default")
      (node (ref "Q2") (pin "2") (pinfunction "S_2") (pintype "passive"))
      (node (ref "Q5") (pin "3") (pinfunction "D_3") (pintype "passive"))
      (node (ref "TP10") (pin "TP") (pinfunction "TP_TP") (pintype "input"))
    )
    (net (code "150") (name "Net-(Q3-D)") (class "Default")
      (node (ref "Q3") (pin "3") (pinfunction "D_3") (pintype "passive"))
      (node (ref "U3") (pin "P$1") (pinfunction "RST_P$1") (pintype "bidirectional"))
    )
    (net (code "151") (name "Net-(Q3-G)") (class "Default")
      (node (ref "Q3") (pin "1") (pinfunction "G_1") (pintype "passive"))
      (node (ref "R15") (pin "2") (pinfunction "2_2") (pintype "passive"))
      (node (ref "R43") (pin "2") (pinfunction "2_2") (pintype "passive"))
    )
    (net (code "152") (name "Net-(Q7-D)") (class "Default")
      (node (ref "Q7") (pin "3") (pinfunction "D_3") (pintype "passive"))
      (node (ref "Q8") (pin "1") (pinfunction "G_1") (pintype "passive"))
      (node (ref "R46") (pin "1") (pinfunction "1_1") (pintype "passive"))
    )
    (net (code "153") (name "Net-(R25-Pad1)") (class "Default")
      (node (ref "R25") (pin "1") (pinfunction "1_1") (pintype "passive"))
      (node (ref "SW1") (pin "B") (pinfunction "B_B") (pintype "bidirectional"))
    )
    (net (code "154") (name "Net-(SPI_1A-S)") (class "Default")
      (node (ref "F28") (pin "2") (pinfunction "2_2") (pintype "bidirectional"))
      (node (ref "SPI_1") (pin "1") (pinfunction "S_1") (pintype "passive"))
    )
    (net (code "155") (name "Net-(SPI_1B-S)") (class "Default")
      (node (ref "F29") (pin "2") (pinfunction "2_2") (pintype "bidirectional"))
      (node (ref "SPI_1") (pin "2") (pinfunction "S_2") (pintype "passive"))
    )
    (net (code "156") (name "Net-(SPI_2A-S)") (class "Default")
      (node (ref "F2") (pin "2") (pinfunction "2_2") (pintype "bidirectional"))
      (node (ref "SPI_2") (pin "1") (pinfunction "S_1") (pintype "passive"))
    )
    (net (code "157") (name "Net-(SPI_2B-S)") (class "Default")
      (node (ref "F3") (pin "2") (pinfunction "2_2") (pintype "bidirectional"))
      (node (ref "SPI_2") (pin "2") (pinfunction "S_2") (pintype "passive"))
    )
    (net (code "158") (name "Net-(SPI_3A-S)") (class "Default")
      (node (ref "F4") (pin "2") (pinfunction "2_2") (pintype "bidirectional"))
      (node (ref "SPI_3") (pin "1") (pinfunction "S_1") (pintype "passive"))
    )
    (net (code "159") (name "Net-(SPI_3B-S)") (class "Default")
      (node (ref "F23") (pin "2") (pinfunction "2_2") (pintype "bidirectional"))
      (node (ref "SPI_3") (pin "2") (pinfunction "S_2") (pintype "passive"))
    )
    (net (code "160") (name "Net-(SPI_4B-S)") (class "Default")
      (node (ref "F25") (pin "2") (pinfunction "2_2") (pintype "bidirectional"))
      (node (ref "SPI_4") (pin "2") (pinfunction "S_2") (pintype "passive"))
    )
    (net (code "161") (name "Net-(SPI_5A-S)") (class "Default")
      (node (ref "F26") (pin "2") (pinfunction "2_2") (pintype "bidirectional"))
      (node (ref "SPI_5") (pin "1") (pinfunction "S_1") (pintype "passive"))
    )
    (net (code "162") (name "Net-(SPI_5B-S)") (class "Default")
      (node (ref "F27") (pin "2") (pinfunction "2_2") (pintype "bidirectional"))
      (node (ref "SPI_5") (pin "2") (pinfunction "S_2") (pintype "passive"))
    )
    (net (code "163") (name "Net-(SPI_6A-S)") (class "Default")
      (node (ref "F30") (pin "2") (pinfunction "2_2") (pintype "bidirectional"))
      (node (ref "SPI_6") (pin "1") (pinfunction "S_1") (pintype "passive"))
    )
    (net (code "164") (name "Net-(SPI_6B-S)") (class "Default")
      (node (ref "F31") (pin "2") (pinfunction "2_2") (pintype "bidirectional"))
      (node (ref "SPI_6") (pin "2") (pinfunction "S_2") (pintype "passive"))
    )
    (net (code "165") (name "Net-(SPI_7A-S)") (class "Default")
      (node (ref "F32") (pin "2") (pinfunction "2_2") (pintype "bidirectional"))
      (node (ref "SPI_7") (pin "1") (pinfunction "S_1") (pintype "passive"))
    )
    (net (code "166") (name "Net-(SPI_7B-S)") (class "Default")
      (node (ref "F33") (pin "2") (pinfunction "2_2") (pintype "bidirectional"))
      (node (ref "SPI_7") (pin "2") (pinfunction "S_2") (pintype "passive"))
    )
    (net (code "167") (name "Net-(SPI_8A-S)") (class "Default")
      (node (ref "F34") (pin "2") (pinfunction "2_2") (pintype "bidirectional"))
      (node (ref "SPI_8") (pin "1") (pinfunction "S_1") (pintype "passive"))
    )
    (net (code "168") (name "Net-(SPI_8B-S)") (class "Default")
      (node (ref "F35") (pin "2") (pinfunction "2_2") (pintype "bidirectional"))
      (node (ref "SPI_8") (pin "2") (pinfunction "S_2") (pintype "passive"))
    )
    (net (code "169") (name "Net-(U$3-G1)") (class "Default")
      (node (ref "C18") (pin "2") (pinfunction "2_2") (pintype "passive"))
      (node (ref "R20") (pin "2") (pinfunction "2_2") (pintype "passive"))
      (node (ref "TP16") (pin "TP") (pinfunction "TP_TP") (pintype "input"))
      (node (ref "U$3") (pin "3") (pinfunction "G1_3") (pintype "passive"))
      (node (ref "U11") (pin "1") (pinfunction "ANODE_1") (pintype "passive"))
    )
    (net (code "170") (name "Net-(U$6-DRV)") (class "Default")
      (node (ref "R42") (pin "2") (pinfunction "2_2") (pintype "passive"))
      (node (ref "TP15") (pin "TP") (pinfunction "TP_TP") (pintype "input"))
      (node (ref "U$6") (pin "22") (pinfunction "DRV_22") (pintype "bidirectional"))
    )
    (net (code "171") (name "Net-(U$6-LED1)") (class "Default")
      (node (ref "TP13") (pin "TP") (pinfunction "TP_TP") (pintype "input"))
      (node (ref "U$6") (pin "23") (pinfunction "LED1_23") (pintype "bidirectional"))
    )
    (net (code "172") (name "Net-(U$6-LED2)") (class "Default")
      (node (ref "TP14") (pin "TP") (pinfunction "TP_TP") (pintype "input"))
      (node (ref "U$6") (pin "24") (pinfunction "LED2_24") (pintype "bidirectional"))
    )
    (net (code "173") (name "Net-(U$6-REXT)") (class "Default")
      (node (ref "R28") (pin "2") (pinfunction "2_2") (pintype "passive"))
      (node (ref "U$6") (pin "14") (pinfunction "REXT_14") (pintype "bidirectional"))
    )
    (net (code "174") (name "Net-(U$6-VD18)") (class "Default")
      (node (ref "C26") (pin "+") (pinfunction "+_+") (pintype "passive"))
      (node (ref "C35") (pin "2") (pinfunction "2_2") (pintype "passive"))
      (node (ref "U$6") (pin "12") (pinfunction "VD18_O_12") (pintype "bidirectional"))
      (node (ref "U$6") (pin "28") (pinfunction "VD18_28") (pintype "bidirectional"))
    )
    (net (code "175") (name "Net-(U$6-VD33)") (class "Default")
      (node (ref "C34") (pin "+") (pinfunction "+_+") (pintype "passive"))
      (node (ref "C36") (pin "2") (pinfunction "2_2") (pintype "passive"))
      (node (ref "U$6") (pin "13") (pinfunction "VD33_13") (pintype "bidirectional"))
      (node (ref "U$6") (pin "21") (pinfunction "VD33_O_21") (pintype "bidirectional"))
    )
    (net (code "176") (name "Net-(U$6-XIN)") (class "Default")
      (node (ref "U$6") (pin "3") (pinfunction "XIN_3") (pintype "bidirectional"))
      (node (ref "Y2") (pin "2") (pinfunction "2_2") (pintype "passive"))
    )
    (net (code "177") (name "Net-(U$6-XOUT)") (class "Default")
      (node (ref "U$6") (pin "2") (pinfunction "XOUT_2") (pintype "bidirectional"))
      (node (ref "Y2") (pin "1") (pinfunction "1_1") (pintype "passive"))
    )
    (net (code "178") (name "Net-(U1-*RESET)") (class "Default")
      (node (ref "R2") (pin "1") (pinfunction "1_1") (pintype "passive"))
      (node (ref "U1") (pin "18") (pinfunction "*RESET_18") (pintype "output"))
    )
    (net (code "179") (name "Net-(U1-GPA0)") (class "Default")
      (node (ref "J5") (pin "1") (pinfunction "1_1") (pintype "passive"))
      (node (ref "J6") (pin "1") (pinfunction "1_1") (pintype "passive"))
      (node (ref "U1") (pin "21") (pinfunction "GPA0_21") (pintype "bidirectional"))
    )
    (net (code "180") (name "Net-(U1-GPA1)") (class "Default")
      (node (ref "J5") (pin "2") (pinfunction "2_2") (pintype "passive"))
      (node (ref "J6") (pin "2") (pinfunction "2_2") (pintype "passive"))
      (node (ref "U1") (pin "22") (pinfunction "GPA1_22") (pintype "bidirectional"))
    )
    (net (code "181") (name "Net-(U1-GPA2)") (class "Default")
      (node (ref "J5") (pin "3") (pinfunction "3_3") (pintype "passive"))
      (node (ref "J6") (pin "3") (pinfunction "3_3") (pintype "passive"))
      (node (ref "U1") (pin "23") (pinfunction "GPA2_23") (pintype "bidirectional"))
    )
    (net (code "182") (name "Net-(U1-GPA3)") (class "Default")
      (node (ref "J5") (pin "4") (pinfunction "4_4") (pintype "passive"))
      (node (ref "J6") (pin "4") (pinfunction "4_4") (pintype "passive"))
      (node (ref "U1") (pin "24") (pinfunction "GPA3_24") (pintype "bidirectional"))
    )
    (net (code "183") (name "Net-(U1-GPA4)") (class "Default")
      (node (ref "J5") (pin "5") (pinfunction "5_5") (pintype "passive"))
      (node (ref "J6") (pin "5") (pinfunction "5_5") (pintype "passive"))
      (node (ref "U1") (pin "25") (pinfunction "GPA4_25") (pintype "bidirectional"))
    )
    (net (code "184") (name "Net-(U1-GPA5)") (class "Default")
      (node (ref "J5") (pin "6") (pinfunction "6_6") (pintype "passive"))
      (node (ref "J6") (pin "6") (pinfunction "6_6") (pintype "passive"))
      (node (ref "U1") (pin "26") (pinfunction "GPA5_26") (pintype "bidirectional"))
    )
    (net (code "185") (name "Net-(U1-GPA6)") (class "Default")
      (node (ref "J5") (pin "7") (pinfunction "7_7") (pintype "passive"))
      (node (ref "J6") (pin "7") (pinfunction "7_7") (pintype "passive"))
      (node (ref "U1") (pin "27") (pinfunction "GPA6_27") (pintype "bidirectional"))
    )
    (net (code "186") (name "Net-(U1-GPA7)") (class "Default")
      (node (ref "J5") (pin "8") (pinfunction "8_8") (pintype "passive"))
      (node (ref "J6") (pin "8") (pinfunction "8_8") (pintype "passive"))
      (node (ref "U1") (pin "28") (pinfunction "GPA7_28") (pintype "bidirectional"))
    )
    (net (code "187") (name "Net-(U1-GPB0)") (class "Default")
      (node (ref "J5") (pin "9") (pinfunction "9_9") (pintype "passive"))
      (node (ref "J6") (pin "9") (pinfunction "9_9") (pintype "passive"))
      (node (ref "U1") (pin "1") (pinfunction "GPB0_1") (pintype "bidirectional"))
    )
    (net (code "188") (name "Net-(U1-GPB1)") (class "Default")
      (node (ref "J5") (pin "10") (pinfunction "10_10") (pintype "passive"))
      (node (ref "J6") (pin "10") (pinfunction "10_10") (pintype "passive"))
      (node (ref "U1") (pin "2") (pinfunction "GPB1_2") (pintype "bidirectional"))
    )
    (net (code "189") (name "Net-(U1-GPB2)") (class "Default")
      (node (ref "J5") (pin "11") (pinfunction "11_11") (pintype "passive"))
      (node (ref "J6") (pin "11") (pinfunction "11_11") (pintype "passive"))
      (node (ref "U1") (pin "3") (pinfunction "GPB2_3") (pintype "bidirectional"))
    )
    (net (code "190") (name "Net-(U1-GPB3)") (class "Default")
      (node (ref "J5") (pin "12") (pinfunction "12_12") (pintype "passive"))
      (node (ref "J6") (pin "12") (pinfunction "12_12") (pintype "passive"))
      (node (ref "U1") (pin "4") (pinfunction "GPB3_4") (pintype "bidirectional"))
    )
    (net (code "191") (name "Net-(U1-GPB4)") (class "Default")
      (node (ref "J5") (pin "13") (pinfunction "13_13") (pintype "passive"))
      (node (ref "J6") (pin "13") (pinfunction "13_13") (pintype "passive"))
      (node (ref "U1") (pin "5") (pinfunction "GPB4_5") (pintype "bidirectional"))
    )
    (net (code "192") (name "Net-(U1-GPB5)") (class "Default")
      (node (ref "J5") (pin "14") (pinfunction "14_14") (pintype "passive"))
      (node (ref "J6") (pin "14") (pinfunction "14_14") (pintype "passive"))
      (node (ref "U1") (pin "6") (pinfunction "GPB5_6") (pintype "bidirectional"))
    )
    (net (code "193") (name "Net-(U1-GPB6)") (class "Default")
      (node (ref "J5") (pin "15") (pinfunction "15_15") (pintype "passive"))
      (node (ref "J6") (pin "15") (pinfunction "15_15") (pintype "passive"))
      (node (ref "U1") (pin "7") (pinfunction "GPB6_7") (pintype "bidirectional"))
    )
    (net (code "194") (name "Net-(U1-GPB7)") (class "Default")
      (node (ref "J5") (pin "16") (pinfunction "16_16") (pintype "passive"))
      (node (ref "J6") (pin "16") (pinfunction "16_16") (pintype "passive"))
      (node (ref "U1") (pin "8") (pinfunction "GPB7_8") (pintype "bidirectional"))
    )
    (net (code "195") (name "Net-(U4-C1+)") (class "Default")
      (node (ref "C21") (pin "1") (pinfunction "1_1") (pintype "passive"))
      (node (ref "U4") (pin "12") (pinfunction "C1+_12") (pintype "input"))
    )
    (net (code "196") (name "Net-(U4-C1-)") (class "Default")
      (node (ref "C21") (pin "2") (pinfunction "2_2") (pintype "passive"))
      (node (ref "U4") (pin "14") (pinfunction "C1-_14") (pintype "input"))
    )
    (net (code "197") (name "Net-(U4-C2+)") (class "Default")
      (node (ref "C24") (pin "2") (pinfunction "2_2") (pintype "passive"))
      (node (ref "U4") (pin "15") (pinfunction "C2+_15") (pintype "input"))
    )
    (net (code "198") (name "Net-(U4-C2-)") (class "Default")
      (node (ref "C24") (pin "1") (pinfunction "1_1") (pintype "passive"))
      (node (ref "U4") (pin "16") (pinfunction "C2-_16") (pintype "input"))
    )
    (net (code "199") (name "Net-(U4-V+)") (class "Default")
      (node (ref "C20") (pin "1") (pinfunction "1_1") (pintype "passive"))
      (node (ref "U4") (pin "13") (pinfunction "V+_13") (pintype "output"))
    )
    (net (code "200") (name "Net-(U4-V-)") (class "Default")
      (node (ref "C22") (pin "1") (pinfunction "1_1") (pintype "passive"))
      (node (ref "U4") (pin "17") (pinfunction "V-_17") (pintype "input"))
    )
    (net (code "201") (name "Net-(U5-CBUS0)") (class "Default")
      (node (ref "D7") (pin "-") (pinfunction "-_-") (pintype "passive"))
      (node (ref "U5") (pin "23") (pinfunction "CBUS0_23") (pintype "input"))
    )
    (net (code "202") (name "Net-(U5-CBUS1)") (class "Default")
      (node (ref "D15") (pin "-") (pinfunction "-_-") (pintype "passive"))
      (node (ref "U5") (pin "22") (pinfunction "CBUS1_22") (pintype "input"))
    )
    (net (code "203") (name "Net-(U6-CBUS0)") (class "Default")
      (node (ref "D2") (pin "-") (pinfunction "-_-") (pintype "passive"))
      (node (ref "U6") (pin "23") (pinfunction "CBUS0_23") (pintype "input"))
    )
    (net (code "204") (name "Net-(U6-CBUS1)") (class "Default")
      (node (ref "D3") (pin "-") (pinfunction "-_-") (pintype "passive"))
      (node (ref "U6") (pin "22") (pinfunction "CBUS1_22") (pintype "input"))
    )
    (net (code "205") (name "Net-(U6-RXD)") (class "Default")
      (node (ref "R14") (pin "1") (pinfunction "1_1") (pintype "passive"))
      (node (ref "U6") (pin "5") (pinfunction "RXD_5") (pintype "input"))
    )
    (net (code "206") (name "Net-(U6-TXD)") (class "Default")
      (node (ref "R13") (pin "1") (pinfunction "1_1") (pintype "passive"))
      (node (ref "U6") (pin "1") (pinfunction "TXD_1") (pintype "input"))
    )
    (net (code "207") (name "Net-(U8-WP)") (class "Default")
      (node (ref "J8") (pin "1") (pinfunction "1_1") (pintype "bidirectional"))
      (node (ref "R36") (pin "1") (pinfunction "1_1") (pintype "passive"))
      (node (ref "TP6") (pin "TP") (pinfunction "TP_TP") (pintype "input"))
      (node (ref "U8") (pin "7") (pinfunction "WP_7") (pintype "input"))
    )
    (net (code "208") (name "Net-(U13-CBUS0)") (class "Default")
      (node (ref "D16") (pin "-") (pinfunction "-_-") (pintype "passive"))
      (node (ref "U13") (pin "23") (pinfunction "CBUS0_23") (pintype "input"))
    )
    (net (code "209") (name "Net-(U13-CBUS1)") (class "Default")
      (node (ref "D17") (pin "-") (pinfunction "-_-") (pintype "passive"))
      (node (ref "U13") (pin "22") (pinfunction "CBUS1_22") (pintype "input"))
    )
    (net (code "210") (name "Net-(U14-CBUS0)") (class "Default")
      (node (ref "D18") (pin "-") (pinfunction "-_-") (pintype "passive"))
      (node (ref "U14") (pin "23") (pinfunction "CBUS0_23") (pintype "input"))
    )
    (net (code "211") (name "Net-(U14-CBUS1)") (class "Default")
      (node (ref "D19") (pin "-") (pinfunction "-_-") (pintype "passive"))
      (node (ref "U14") (pin "22") (pinfunction "CBUS1_22") (pintype "input"))
    )
    (net (code "212") (name "Net-(U15-CBUS0)") (class "Default")
      (node (ref "D20") (pin "-") (pinfunction "-_-") (pintype "passive"))
      (node (ref "U15") (pin "23") (pinfunction "CBUS0_23") (pintype "input"))
    )
    (net (code "213") (name "Net-(U15-CBUS1)") (class "Default")
      (node (ref "D21") (pin "-") (pinfunction "-_-") (pintype "passive"))
      (node (ref "U15") (pin "22") (pinfunction "CBUS1_22") (pintype "input"))
    )
    (net (code "214") (name "Net-(USB3-VBUS)") (class "Default")
      (node (ref "C9") (pin "2") (pinfunction "2_2") (pintype "passive"))
      (node (ref "L1") (pin "1") (pinfunction "1_1") (pintype "passive"))
      (node (ref "USB3") (pin "1") (pinfunction "VBUS_1") (pintype "power_in"))
    )
    (net (code "215") (name "P2_SIG") (class "Default")
      (node (ref "Q6") (pin "1") (pinfunction "G_1") (pintype "passive"))
      (node (ref "R41") (pin "1") (pinfunction "1_1") (pintype "passive"))
      (node (ref "R44") (pin "2") (pinfunction "2_2") (pintype "passive"))
    )
    (net (code "216") (name "P12_SIG") (class "Default")
      (node (ref "Q7") (pin "1") (pinfunction "G_1") (pintype "passive"))
      (node (ref "R17") (pin "1") (pinfunction "1_1") (pintype "passive"))
      (node (ref "R45") (pin "2") (pinfunction "2_2") (pintype "passive"))
    )
    (net (code "217") (name "PI_5V") (class "Default")
      (node (ref "C13") (pin "2") (pinfunction "2_2") (pintype "passive"))
      (node (ref "F11") (pin "1") (pinfunction "1_1") (pintype "bidirectional"))
      (node (ref "F13") (pin "1") (pinfunction "1_1") (pintype "bidirectional"))
      (node (ref "F15") (pin "1") (pinfunction "1_1") (pintype "bidirectional"))
      (node (ref "F17") (pin "1") (pinfunction "1_1") (pintype "bidirectional"))
      (node (ref "F19") (pin "1") (pinfunction "1_1") (pintype "bidirectional"))
      (node (ref "F2") (pin "1") (pinfunction "1_1") (pintype "bidirectional"))
      (node (ref "F21") (pin "1") (pinfunction "1_1") (pintype "bidirectional"))
      (node (ref "F24") (pin "1") (pinfunction "1_1") (pintype "bidirectional"))
      (node (ref "F26") (pin "1") (pinfunction "1_1") (pintype "bidirectional"))
      (node (ref "F28") (pin "1") (pinfunction "1_1") (pintype "bidirectional"))
      (node (ref "F30") (pin "1") (pinfunction "1_1") (pintype "bidirectional"))
      (node (ref "F32") (pin "1") (pinfunction "1_1") (pintype "bidirectional"))
      (node (ref "F34") (pin "1") (pinfunction "1_1") (pintype "bidirectional"))
      (node (ref "F36") (pin "1") (pinfunction "1_1") (pintype "bidirectional"))
      (node (ref "F38") (pin "1") (pinfunction "1_1") (pintype "bidirectional"))
      (node (ref "F4") (pin "1") (pinfunction "1_1") (pintype "bidirectional"))
      (node (ref "F40") (pin "1") (pinfunction "1_1") (pintype "bidirectional"))
      (node (ref "F42") (pin "1") (pinfunction "1_1") (pintype "bidirectional"))
      (node (ref "F44") (pin "1") (pinfunction "1_1") (pintype "bidirectional"))
      (node (ref "F46") (pin "1") (pinfunction "1_1") (pintype "bidirectional"))
      (node (ref "F48") (pin "1") (pinfunction "1_1") (pintype "bidirectional"))
      (node (ref "F5") (pin "1") (pinfunction "1_1") (pintype "bidirectional"))
      (node (ref "F50") (pin "1") (pinfunction "1_1") (pintype "bidirectional"))
      (node (ref "F52") (pin "1") (pinfunction "1_1") (pintype "bidirectional"))
      (node (ref "F54") (pin "1") (pinfunction "1_1") (pintype "bidirectional"))
      (node (ref "F60") (pin "1") (pinfunction "1_1") (pintype "bidirectional"))
      (node (ref "F7") (pin "1") (pinfunction "1_1") (pintype "bidirectional"))
      (node (ref "F9") (pin "1") (pinfunction "1_1") (pintype "bidirectional"))
      (node (ref "PCB1") (pin "P$2") (pinfunction "5V_P$2") (pintype "bidirectional"))
      (node (ref "PCB1") (pin "P$4") (pinfunction "5V_P$4") (pintype "bidirectional"))
      (node (ref "Q5") (pin "2") (pinfunction "S_2") (pintype "passive"))
      (node (ref "R21") (pin "2") (pinfunction "2_2") (pintype "passive"))
      (node (ref "TP11") (pin "TP") (pinfunction "TP_TP") (pintype "input"))
      (node (ref "U10") (pin "16") (pinfunction "VCC_16") (pintype "power_in"))
    )
    (net (code "218") (name "PI_PWR_CTRL") (class "Default")
      (node (ref "Q4") (pin "1") (pinfunction "G_1") (pintype "passive"))
      (node (ref "R4") (pin "2") (pinfunction "2_2") (pintype "passive"))
      (node (ref "R40") (pin "2") (pinfunction "2_2") (pintype "passive"))
      (node (ref "SW3") (pin "COM") (pinfunction "COM_COM") (pintype "bidirectional"))
      (node (ref "TP9") (pin "TP") (pinfunction "TP_TP") (pintype "input"))
      (node (ref "U3") (pin "P$15") (pinfunction "P13_P$15") (pintype "input"))
    )
    (net (code "219") (name "PI_TTL_RXD") (class "Default")
      (node (ref "PCB1") (pin "P$10") (pinfunction "GPIO15_P$10") (pintype "bidirectional"))
      (node (ref "PI_UART") (pin "4") (pinfunction "S_4") (pintype "passive"))
      (node (ref "R12") (pin "2") (pinfunction "2_2") (pintype "passive"))
    )
    (net (code "220") (name "PI_TTL_TXD") (class "Default")
      (node (ref "PCB1") (pin "P$8") (pinfunction "GPIO14_P$8") (pintype "bidirectional"))
      (node (ref "PI_UART") (pin "3") (pinfunction "S_3") (pintype "passive"))
      (node (ref "R8") (pin "2") (pinfunction "2_2") (pintype "passive"))
    )
    (net (code "221") (name "RPI_CS1") (class "Default")
      (node (ref "SPI_1") (pin "3") (pinfunction "S_3") (pintype "passive"))
      (node (ref "U10") (pin "4") (pinfunction "1~{Y0}_4") (pintype "output"))
    )
    (net (code "222") (name "RPI_CS2") (class "Default")
      (node (ref "SPI_2") (pin "3") (pinfunction "S_3") (pintype "passive"))
      (node (ref "U10") (pin "5") (pinfunction "1~{Y1}_5") (pintype "output"))
    )
    (net (code "223") (name "RPI_CS3") (class "Default")
      (node (ref "SPI_3") (pin "3") (pinfunction "S_3") (pintype "passive"))
      (node (ref "U10") (pin "6") (pinfunction "1~{Y2}_6") (pintype "output"))
    )
    (net (code "224") (name "RPI_CS4") (class "Default")
      (node (ref "SPI_4") (pin "3") (pinfunction "S_3") (pintype "passive"))
      (node (ref "U10") (pin "7") (pinfunction "1~{Y3}_7") (pintype "output"))
    )
    (net (code "225") (name "RPI_CS5") (class "Default")
      (node (ref "SPI_5") (pin "3") (pinfunction "S_3") (pintype "passive"))
      (node (ref "U10") (pin "12") (pinfunction "2~{Y0}_12") (pintype "output"))
    )
    (net (code "226") (name "RPI_CS6") (class "Default")
      (node (ref "SPI_6") (pin "3") (pinfunction "S_3") (pintype "passive"))
      (node (ref "U10") (pin "11") (pinfunction "2~{Y1}_11") (pintype "output"))
    )
    (net (code "227") (name "RPI_CS7") (class "Default")
      (node (ref "SPI_7") (pin "3") (pinfunction "S_3") (pintype "passive"))
      (node (ref "U10") (pin "10") (pinfunction "2~{Y2}_10") (pintype "output"))
    )
    (net (code "228") (name "RPI_CS8") (class "Default")
      (node (ref "SPI_8") (pin "3") (pinfunction "S_3") (pintype "passive"))
      (node (ref "U10") (pin "9") (pinfunction "2~{Y3}_9") (pintype "output"))
    )
    (net (code "229") (name "RS232_3_RXD") (class "Default")
      (node (ref "PI_UART_HUB_3") (pin "4") (pinfunction "S_4") (pintype "passive"))
      (node (ref "U4") (pin "27") (pinfunction "RIN3_27") (pintype "input"))
    )
    (net (code "230") (name "RS232_3_TXD") (class "Default")
      (node (ref "PI_UART_HUB_3") (pin "3") (pinfunction "S_3") (pintype "passive"))
      (node (ref "U4") (pin "1") (pinfunction "DOUT3_1") (pintype "output"))
    )
    (net (code "231") (name "RS485_A") (class "Default")
      (node (ref "PI_RS_485") (pin "3") (pinfunction "S_3") (pintype "passive"))
      (node (ref "SW1") (pin "COM") (pinfunction "COM_COM") (pintype "bidirectional"))
      (node (ref "U12") (pin "6") (pinfunction "A_6") (pintype "bidirectional"))
    )
    (net (code "232") (name "RS485_B") (class "Default")
      (node (ref "PI_RS_485") (pin "4") (pinfunction "S_4") (pintype "passive"))
      (node (ref "R25") (pin "2") (pinfunction "2_2") (pintype "passive"))
      (node (ref "U12") (pin "7") (pinfunction "B_7") (pintype "bidirectional"))
    )
    (net (code "233") (name "RTC_BATT") (class "Default")
      (node (ref "BAT1") (pin "+1") (pinfunction "V+_+1") (pintype "bidirectional"))
      (node (ref "BAT1") (pin "+2") (pinfunction "V+_+2") (pintype "bidirectional"))
      (node (ref "TP17") (pin "TP") (pinfunction "TP_TP") (pintype "input"))
      (node (ref "U2") (pin "3") (pinfunction "VBAT_3") (pintype "power_in"))
    )
    (net (code "234") (name "RXD1") (class "Default")
      (node (ref "I_UART_HUB_1") (pin "4") (pinfunction "S_4") (pintype "passive"))
      (node (ref "U13") (pin "5") (pinfunction "RXD_5") (pintype "input"))
    )
    (net (code "235") (name "RXD2") (class "Default")
      (node (ref "PI_UART_HUB_2") (pin "4") (pinfunction "S_4") (pintype "passive"))
      (node (ref "U14") (pin "5") (pinfunction "RXD_5") (pintype "input"))
    )
    (net (code "236") (name "RXD3") (class "Default")
      (node (ref "U15") (pin "5") (pinfunction "RXD_5") (pintype "input"))
      (node (ref "U4") (pin "26") (pinfunction "ROUT3_26") (pintype "output"))
    )
    (net (code "237") (name "SCL_3V3") (class "Default")
      (node (ref "I2C_1") (pin "4") (pinfunction "S_4") (pintype "passive"))
      (node (ref "I2C_10") (pin "4") (pinfunction "S_4") (pintype "passive"))
      (node (ref "I2C_2") (pin "4") (pinfunction "S_4") (pintype "passive"))
      (node (ref "I2C_3") (pin "4") (pinfunction "S_4") (pintype "passive"))
      (node (ref "I2C_4") (pin "4") (pinfunction "S_4") (pintype "passive"))
      (node (ref "I2C_5") (pin "4") (pinfunction "S_4") (pintype "passive"))
      (node (ref "I2C_6") (pin "4") (pinfunction "S_4") (pintype "passive"))
      (node (ref "I2C_7") (pin "4") (pinfunction "S_4") (pintype "passive"))
      (node (ref "I2C_8") (pin "4") (pinfunction "S_4") (pintype "passive"))
      (node (ref "I2C_9") (pin "4") (pinfunction "S_4") (pintype "passive"))
      (node (ref "PCB1") (pin "P$5") (pinfunction "GPIO3_P$5") (pintype "bidirectional"))
      (node (ref "R18") (pin "1") (pinfunction "1_1") (pintype "passive"))
      (node (ref "U$1") (pin "8") (pinfunction "SCL_8") (pintype "input"))
      (node (ref "U$2") (pin "8") (pinfunction "SCL_8") (pintype "input"))
      (node (ref "U1") (pin "12") (pinfunction "SCL_12") (pintype "input"))
      (node (ref "U2") (pin "6") (pinfunction "SCL_6") (pintype "passive"))
    )
    (net (code "238") (name "SDA_3V3") (class "Default")
      (node (ref "I2C_1") (pin "3") (pinfunction "S_3") (pintype "passive"))
      (node (ref "I2C_10") (pin "3") (pinfunction "S_3") (pintype "passive"))
      (node (ref "I2C_2") (pin "3") (pinfunction "S_3") (pintype "passive"))
      (node (ref "I2C_3") (pin "3") (pinfunction "S_3") (pintype "passive"))
      (node (ref "I2C_4") (pin "3") (pinfunction "S_3") (pintype "passive"))
      (node (ref "I2C_5") (pin "3") (pinfunction "S_3") (pintype "passive"))
      (node (ref "I2C_6") (pin "3") (pinfunction "S_3") (pintype "passive"))
      (node (ref "I2C_7") (pin "3") (pinfunction "S_3") (pintype "passive"))
      (node (ref "I2C_8") (pin "3") (pinfunction "S_3") (pintype "passive"))
      (node (ref "I2C_9") (pin "3") (pinfunction "S_3") (pintype "passive"))
      (node (ref "PCB1") (pin "P$3") (pinfunction "GPIO2_P$3") (pintype "bidirectional"))
      (node (ref "R19") (pin "1") (pinfunction "1_1") (pintype "passive"))
      (node (ref "U$1") (pin "7") (pinfunction "SDA_7") (pintype "bidirectional"))
      (node (ref "U$2") (pin "7") (pinfunction "SDA_7") (pintype "bidirectional"))
      (node (ref "U1") (pin "13") (pinfunction "SDA_13") (pintype "bidirectional"))
      (node (ref "U2") (pin "5") (pinfunction "SDA_5") (pintype "passive"))
    )
    (net (code "239") (name "SPI0_CS0") (class "Default")
      (node (ref "PCB1") (pin "P$24") (pinfunction "GPIO8_P$24") (pintype "bidirectional"))
      (node (ref "U10") (pin "1") (pinfunction "1~{E}_1") (pintype "input"))
    )
    (net (code "240") (name "SPI0_CS1") (class "Default")
      (node (ref "PCB1") (pin "P$26") (pinfunction "GPIO7_P$26") (pintype "bidirectional"))
      (node (ref "U10") (pin "15") (pinfunction "2~{E}_15") (pintype "input"))
    )
    (net (code "241") (name "SPI_5V_4_P") (class "Default")
      (node (ref "F24") (pin "2") (pinfunction "2_2") (pintype "bidirectional"))
      (node (ref "SPI_4") (pin "1") (pinfunction "S_1") (pintype "passive"))
    )
    (net (code "242") (name "SPI_GPIO1") (class "Default")
      (node (ref "PCB1") (pin "P$11") (pinfunction "GPIO17_P$11") (pintype "bidirectional"))
      (node (ref "U10") (pin "2") (pinfunction "1A0_2") (pintype "input"))
    )
    (net (code "243") (name "SPI_GPIO2") (class "Default")
      (node (ref "PCB1") (pin "P$13") (pinfunction "GPIO27_P$13") (pintype "bidirectional"))
      (node (ref "U10") (pin "3") (pinfunction "1A1_3") (pintype "input"))
    )
    (net (code "244") (name "SPI_GPIO3") (class "Default")
      (node (ref "PCB1") (pin "P$15") (pinfunction "GPIO22_P$15") (pintype "bidirectional"))
      (node (ref "U10") (pin "14") (pinfunction "2A0_14") (pintype "input"))
    )
    (net (code "245") (name "SPI_GPIO4") (class "Default")
      (node (ref "PCB1") (pin "P$16") (pinfunction "GPIO23_P$16") (pintype "bidirectional"))
      (node (ref "U10") (pin "13") (pinfunction "2A1_13") (pintype "input"))
    )
    (net (code "246") (name "SPI_MISO") (class "Default")
      (node (ref "PCB1") (pin "P$21") (pinfunction "GPIO9_P$21") (pintype "bidirectional"))
      (node (ref "SPI_1") (pin "5") (pinfunction "S_5") (pintype "passive"))
      (node (ref "SPI_2") (pin "5") (pinfunction "S_5") (pintype "passive"))
      (node (ref "SPI_3") (pin "5") (pinfunction "S_5") (pintype "passive"))
      (node (ref "SPI_4") (pin "5") (pinfunction "S_5") (pintype "passive"))
      (node (ref "SPI_5") (pin "5") (pinfunction "S_5") (pintype "passive"))
      (node (ref "SPI_6") (pin "5") (pinfunction "S_5") (pintype "passive"))
      (node (ref "SPI_7") (pin "5") (pinfunction "S_5") (pintype "passive"))
      (node (ref "SPI_8") (pin "5") (pinfunction "S_5") (pintype "passive"))
    )
    (net (code "247") (name "SPI_MOSI") (class "Default")
      (node (ref "PCB1") (pin "P$19") (pinfunction "GPIO10_P$19") (pintype "bidirectional"))
      (node (ref "SPI_1") (pin "4") (pinfunction "S_4") (pintype "passive"))
      (node (ref "SPI_2") (pin "4") (pinfunction "S_4") (pintype "passive"))
      (node (ref "SPI_3") (pin "4") (pinfunction "S_4") (pintype "passive"))
      (node (ref "SPI_4") (pin "4") (pinfunction "S_4") (pintype "passive"))
      (node (ref "SPI_5") (pin "4") (pinfunction "S_4") (pintype "passive"))
      (node (ref "SPI_6") (pin "4") (pinfunction "S_4") (pintype "passive"))
      (node (ref "SPI_7") (pin "4") (pinfunction "S_4") (pintype "passive"))
      (node (ref "SPI_8") (pin "4") (pinfunction "S_4") (pintype "passive"))
    )
    (net (code "248") (name "SPI_SCLK") (class "Default")
      (node (ref "PCB1") (pin "P$23") (pinfunction "GPIO11_P$23") (pintype "bidirectional"))
      (node (ref "SPI_1") (pin "6") (pinfunction "S_6") (pintype "passive"))
      (node (ref "SPI_2") (pin "6") (pinfunction "S_6") (pintype "passive"))
      (node (ref "SPI_3") (pin "6") (pinfunction "S_6") (pintype "passive"))
      (node (ref "SPI_4") (pin "6") (pinfunction "S_6") (pintype "passive"))
      (node (ref "SPI_5") (pin "6") (pinfunction "S_6") (pintype "passive"))
      (node (ref "SPI_6") (pin "6") (pinfunction "S_6") (pintype "passive"))
      (node (ref "SPI_7") (pin "6") (pinfunction "S_6") (pintype "passive"))
      (node (ref "SPI_8") (pin "6") (pinfunction "S_6") (pintype "passive"))
    )
    (net (code "249") (name "TXD1") (class "Default")
      (node (ref "I_UART_HUB_1") (pin "3") (pinfunction "S_3") (pintype "passive"))
      (node (ref "U13") (pin "1") (pinfunction "TXD_1") (pintype "input"))
    )
    (net (code "250") (name "TXD2") (class "Default")
      (node (ref "PI_UART_HUB_2") (pin "3") (pinfunction "S_3") (pintype "passive"))
      (node (ref "U14") (pin "1") (pinfunction "TXD_1") (pintype "input"))
    )
    (net (code "251") (name "TXD3") (class "Default")
      (node (ref "U15") (pin "1") (pinfunction "TXD_1") (pintype "input"))
      (node (ref "U4") (pin "20") (pinfunction "DIN3_20") (pintype "input"))
    )
    (net (code "252") (name "USB1_DM") (class "Default")
      (node (ref "U$6") (pin "10") (pinfunction "DM1_10") (pintype "bidirectional"))
      (node (ref "U5") (pin "16") (pinfunction "USBDM_16") (pintype "input"))
    )
    (net (code "253") (name "USB1_DP") (class "Default")
      (node (ref "U$6") (pin "11") (pinfunction "DP1_11") (pintype "bidirectional"))
      (node (ref "U5") (pin "15") (pinfunction "USBDP_15") (pintype "input"))
    )
    (net (code "254") (name "USB2_DM") (class "Default")
      (node (ref "U$6") (pin "8") (pinfunction "DM2_8") (pintype "bidirectional"))
      (node (ref "U13") (pin "16") (pinfunction "USBDM_16") (pintype "input"))
    )
    (net (code "255") (name "USB2_DP") (class "Default")
      (node (ref "U$6") (pin "9") (pinfunction "DP2_9") (pintype "bidirectional"))
      (node (ref "U13") (pin "15") (pinfunction "USBDP_15") (pintype "input"))
    )
    (net (code "256") (name "USB3_DM") (class "Default")
      (node (ref "U$6") (pin "4") (pinfunction "DM4_4") (pintype "bidirectional"))
      (node (ref "U14") (pin "16") (pinfunction "USBDM_16") (pintype "input"))
    )
    (net (code "257") (name "USB3_DP") (class "Default")
      (node (ref "U$6") (pin "5") (pinfunction "DP4_5") (pintype "bidirectional"))
      (node (ref "U14") (pin "15") (pinfunction "USBDP_15") (pintype "input"))
    )
    (net (code "258") (name "USB4_DM") (class "Default")
      (node (ref "U$6") (pin "6") (pinfunction "DM3_6") (pintype "bidirectional"))
      (node (ref "U15") (pin "16") (pinfunction "USBDM_16") (pintype "input"))
    )
    (net (code "259") (name "USB4_DP") (class "Default")
      (node (ref "U$6") (pin "7") (pinfunction "DP3_7") (pintype "bidirectional"))
      (node (ref "U15") (pin "15") (pinfunction "USBDP_15") (pintype "input"))
    )
    (net (code "260") (name "USB_DM") (class "Default")
      (node (ref "U6") (pin "16") (pinfunction "USBDM_16") (pintype "input"))
      (node (ref "USB3") (pin "2") (pinfunction "D-_2") (pintype "bidirectional"))
    )
    (net (code "261") (name "USB_DP") (class "Default")
      (node (ref "U6") (pin "15") (pinfunction "USBDP_15") (pintype "input"))
      (node (ref "USB3") (pin "3") (pinfunction "D+_3") (pintype "bidirectional"))
    )
    (net (code "262") (name "USB_HUB_DM") (class "Default")
      (node (ref "U$6") (pin "15") (pinfunction "DMU_15") (pintype "bidirectional"))
      (node (ref "USB1") (pin "2") (pinfunction "D-_2") (pintype "bidirectional"))
    )
    (net (code "263") (name "USB_HUB_DP") (class "Default")
      (node (ref "U$6") (pin "16") (pinfunction "DPU_16") (pintype "bidirectional"))
      (node (ref "USB1") (pin "3") (pinfunction "D+_3") (pintype "bidirectional"))
    )
    (net (code "264") (name "USB_HUB_VD33_O") (class "Default")
      (node (ref "U$6") (pin "17") (pinfunction "XRSTJ_17") (pintype "bidirectional"))
      (node (ref "U$6") (pin "18") (pinfunction "VBUSM_18") (pintype "bidirectional"))
      (node (ref "U$6") (pin "19") (pinfunction "BUSJ_19") (pintype "bidirectional"))
      (node (ref "U$6") (pin "26") (pinfunction "OVCJ_26") (pintype "bidirectional"))
    )
    (net (code "265") (name "X1_RTC") (class "Default")
      (node (ref "C1") (pin "1") (pinfunction "1_1") (pintype "passive"))
      (node (ref "Q1") (pin "1") (pinfunction "1_1") (pintype "passive"))
      (node (ref "U2") (pin "1") (pinfunction "X1_1") (pintype "input"))
    )
    (net (code "266") (name "X2_RTC") (class "Default")
      (node (ref "C3") (pin "1") (pinfunction "1_1") (pintype "passive"))
      (node (ref "Q1") (pin "4") (pinfunction "2_4") (pintype "passive"))
      (node (ref "U2") (pin "2") (pinfunction "X2_2") (pintype "input"))
    )
    (net (code "267") (name "unconnected-(J2-CDN-Pad9)") (class "Default")
      (node (ref "J2") (pin "9") (pinfunction "CDN_9") (pintype "bidirectional"))
    )
    (net (code "268") (name "unconnected-(J2-DATA1-Pad8)") (class "Default")
      (node (ref "J2") (pin "8") (pinfunction "DATA1_8") (pintype "bidirectional"))
    )
    (net (code "269") (name "unconnected-(J2-DATA2-Pad1)") (class "Default")
      (node (ref "J2") (pin "1") (pinfunction "DATA2_1") (pintype "bidirectional"))
    )
    (net (code "270") (name "unconnected-(PCB1-RUN_1-PadP$41)") (class "Default")
      (node (ref "PCB1") (pin "P$41") (pinfunction "RUN_1_P$41") (pintype "bidirectional"))
    )
    (net (code "271") (name "unconnected-(PCB1-RUN_2-PadP$42)") (class "Default")
      (node (ref "PCB1") (pin "P$42") (pinfunction "RUN_2_P$42") (pintype "bidirectional"))
    )
    (net (code "272") (name "unconnected-(SW1-PadA)") (class "Default")
      (node (ref "SW1") (pin "A") (pinfunction "A_A") (pintype "bidirectional"))
    )
    (net (code "273") (name "unconnected-(SW3-PadA)") (class "Default")
      (node (ref "SW3") (pin "A") (pinfunction "A_A") (pintype "bidirectional"))
    )
    (net (code "274") (name "unconnected-(SW4-PadA)") (class "Default")
      (node (ref "SW4") (pin "A") (pinfunction "A_A") (pintype "bidirectional"))
    )
    (net (code "275") (name "unconnected-(U$2-ADR1-Pad10)") (class "Default")
      (node (ref "U$2") (pin "10") (pinfunction "ADR1_10") (pintype "input"))
    )
    (net (code "276") (name "unconnected-(U$6-PWRJ-Pad25)") (class "Default")
      (node (ref "U$6") (pin "25") (pinfunction "PWRJ_25") (pintype "bidirectional"))
    )
    (net (code "277") (name "unconnected-(U$6-TESTJ-Pad27)") (class "Default")
      (node (ref "U$6") (pin "27") (pinfunction "TESTJ_27") (pintype "bidirectional"))
    )
    (net (code "278") (name "unconnected-(U$7-N.C.-Pad3)") (class "Default")
      (node (ref "U$7") (pin "3") (pinfunction "N.C._3") (pintype "passive"))
    )
    (net (code "279") (name "unconnected-(U1-NC-Pad11)") (class "Default")
      (node (ref "U1") (pin "11") (pinfunction "NC_11") (pintype "no_connect"))
    )
    (net (code "280") (name "unconnected-(U1-NC_2-Pad14)") (class "Default")
      (node (ref "U1") (pin "14") (pinfunction "NC_2_14") (pintype "no_connect"))
    )
    (net (code "281") (name "unconnected-(U2-MFP-Pad7)") (class "Default")
      (node (ref "U2") (pin "7") (pinfunction "MFP_7") (pintype "passive"))
    )
    (net (code "282") (name "unconnected-(U3-LORA_CLK-PadP$7)") (class "Default")
      (node (ref "U3") (pin "P$7") (pinfunction "LORA_CLK_P$7") (pintype "no_connect"))
    )
    (net (code "283") (name "unconnected-(U3-LORA_MISO-PadP$9)") (class "Default")
      (node (ref "U3") (pin "P$9") (pinfunction "LORA_MISO_P$9") (pintype "no_connect"))
    )
    (net (code "284") (name "unconnected-(U3-LORA_MOSI-PadP$8)") (class "Default")
      (node (ref "U3") (pin "P$8") (pinfunction "LORA_MOSI_P$8") (pintype "no_connect"))
    )
    (net (code "285") (name "unconnected-(U4-DIN1-Pad7)") (class "Default")
      (node (ref "U4") (pin "7") (pinfunction "DIN1_7") (pintype "input"))
    )
    (net (code "286") (name "unconnected-(U4-DIN2-Pad6)") (class "Default")
      (node (ref "U4") (pin "6") (pinfunction "DIN2_6") (pintype "input"))
    )
    (net (code "287") (name "unconnected-(U4-DIN4-Pad21)") (class "Default")
      (node (ref "U4") (pin "21") (pinfunction "DIN4_21") (pintype "input"))
    )
    (net (code "288") (name "unconnected-(U4-DOUT1-Pad2)") (class "Default")
      (node (ref "U4") (pin "2") (pinfunction "DOUT1_2") (pintype "output"))
    )
    (net (code "289") (name "unconnected-(U4-DOUT2-Pad3)") (class "Default")
      (node (ref "U4") (pin "3") (pinfunction "DOUT2_3") (pintype "output"))
    )
    (net (code "290") (name "unconnected-(U4-DOUT4-Pad28)") (class "Default")
      (node (ref "U4") (pin "28") (pinfunction "DOUT4_28") (pintype "output"))
    )
    (net (code "291") (name "unconnected-(U4-RIN1-Pad9)") (class "Default")
      (node (ref "U4") (pin "9") (pinfunction "RIN1_9") (pintype "input"))
    )
    (net (code "292") (name "unconnected-(U4-RIN2-Pad4)") (class "Default")
      (node (ref "U4") (pin "4") (pinfunction "RIN2_4") (pintype "input"))
    )
    (net (code "293") (name "unconnected-(U4-RIN4-Pad23)") (class "Default")
      (node (ref "U4") (pin "23") (pinfunction "RIN4_23") (pintype "input"))
    )
    (net (code "294") (name "unconnected-(U4-RIN5-Pad18)") (class "Default")
      (node (ref "U4") (pin "18") (pinfunction "RIN5_18") (pintype "input"))
    )
    (net (code "295") (name "unconnected-(U4-ROUT1-Pad8)") (class "Default")
      (node (ref "U4") (pin "8") (pinfunction "ROUT1_8") (pintype "output"))
    )
    (net (code "296") (name "unconnected-(U4-ROUT2-Pad5)") (class "Default")
      (node (ref "U4") (pin "5") (pinfunction "ROUT2_5") (pintype "output"))
    )
    (net (code "297") (name "unconnected-(U4-ROUT4-Pad22)") (class "Default")
      (node (ref "U4") (pin "22") (pinfunction "ROUT4_22") (pintype "output"))
    )
    (net (code "298") (name "unconnected-(U4-ROUT5-Pad19)") (class "Default")
      (node (ref "U4") (pin "19") (pinfunction "ROUT5_19") (pintype "output"))
    )
    (net (code "299") (name "unconnected-(U5-CBUS4-Pad12)") (class "Default")
      (node (ref "U5") (pin "12") (pinfunction "CBUS4_12") (pintype "input"))
    )
    (net (code "300") (name "unconnected-(U5-OSCI-Pad27)") (class "Default")
      (node (ref "U5") (pin "27") (pinfunction "OSCI_27") (pintype "input"))
    )
    (net (code "301") (name "unconnected-(U5-OSCO-Pad28)") (class "Default")
      (node (ref "U5") (pin "28") (pinfunction "OSCO_28") (pintype "input"))
    )
    (net (code "302") (name "unconnected-(U5-~{CTS}-Pad11)") (class "Default")
      (node (ref "U5") (pin "11") (pinfunction "~{CTS}_11") (pintype "input"))
    )
    (net (code "303") (name "unconnected-(U5-~{DCD}-Pad10)") (class "Default")
      (node (ref "U5") (pin "10") (pinfunction "~{DCD}_10") (pintype "input"))
    )
    (net (code "304") (name "unconnected-(U5-~{DSR}-Pad9)") (class "Default")
      (node (ref "U5") (pin "9") (pinfunction "~{DSR}_9") (pintype "input"))
    )
    (net (code "305") (name "unconnected-(U5-~{DTR}-Pad2)") (class "Default")
      (node (ref "U5") (pin "2") (pinfunction "~{DTR}_2") (pintype "input"))
    )
    (net (code "306") (name "unconnected-(U5-~{RESET}-Pad19)") (class "Default")
      (node (ref "U5") (pin "19") (pinfunction "~{RESET}_19") (pintype "input"))
    )
    (net (code "307") (name "unconnected-(U5-~{RI}-Pad6)") (class "Default")
      (node (ref "U5") (pin "6") (pinfunction "~{RI}_6") (pintype "input"))
    )
    (net (code "308") (name "unconnected-(U5-~{RTS}-Pad3)") (class "Default")
      (node (ref "U5") (pin "3") (pinfunction "~{RTS}_3") (pintype "input"))
    )
    (net (code "309") (name "unconnected-(U6-CBUS2-Pad13)") (class "Default")
      (node (ref "U6") (pin "13") (pinfunction "CBUS2_13") (pintype "input"))
    )
    (net (code "310") (name "unconnected-(U6-CBUS3-Pad14)") (class "Default")
      (node (ref "U6") (pin "14") (pinfunction "CBUS3_14") (pintype "input"))
    )
    (net (code "311") (name "unconnected-(U6-CBUS4-Pad12)") (class "Default")
      (node (ref "U6") (pin "12") (pinfunction "CBUS4_12") (pintype "input"))
    )
    (net (code "312") (name "unconnected-(U6-OSCI-Pad27)") (class "Default")
      (node (ref "U6") (pin "27") (pinfunction "OSCI_27") (pintype "input"))
    )
    (net (code "313") (name "unconnected-(U6-OSCO-Pad28)") (class "Default")
      (node (ref "U6") (pin "28") (pinfunction "OSCO_28") (pintype "input"))
    )
    (net (code "314") (name "unconnected-(U6-~{CTS}-Pad11)") (class "Default")
      (node (ref "U6") (pin "11") (pinfunction "~{CTS}_11") (pintype "input"))
    )
    (net (code "315") (name "unconnected-(U6-~{DCD}-Pad10)") (class "Default")
      (node (ref "U6") (pin "10") (pinfunction "~{DCD}_10") (pintype "input"))
    )
    (net (code "316") (name "unconnected-(U6-~{DSR}-Pad9)") (class "Default")
      (node (ref "U6") (pin "9") (pinfunction "~{DSR}_9") (pintype "input"))
    )
    (net (code "317") (name "unconnected-(U6-~{DTR}-Pad2)") (class "Default")
      (node (ref "U6") (pin "2") (pinfunction "~{DTR}_2") (pintype "input"))
    )
    (net (code "318") (name "unconnected-(U6-~{RESET}-Pad19)") (class "Default")
      (node (ref "U6") (pin "19") (pinfunction "~{RESET}_19") (pintype "input"))
    )
    (net (code "319") (name "unconnected-(U6-~{RI}-Pad6)") (class "Default")
      (node (ref "U6") (pin "6") (pinfunction "~{RI}_6") (pintype "input"))
    )
    (net (code "320") (name "unconnected-(U6-~{RTS}-Pad3)") (class "Default")
      (node (ref "U6") (pin "3") (pinfunction "~{RTS}_3") (pintype "input"))
    )
    (net (code "321") (name "unconnected-(U11-NC-Pad2)") (class "Default")
      (node (ref "U11") (pin "2") (pinfunction "NC_2") (pintype "no_connect"))
    )
    (net (code "322") (name "unconnected-(U13-CBUS2-Pad13)") (class "Default")
      (node (ref "U13") (pin "13") (pinfunction "CBUS2_13") (pintype "input"))
    )
    (net (code "323") (name "unconnected-(U13-CBUS3-Pad14)") (class "Default")
      (node (ref "U13") (pin "14") (pinfunction "CBUS3_14") (pintype "input"))
    )
    (net (code "324") (name "unconnected-(U13-CBUS4-Pad12)") (class "Default")
      (node (ref "U13") (pin "12") (pinfunction "CBUS4_12") (pintype "input"))
    )
    (net (code "325") (name "unconnected-(U13-OSCI-Pad27)") (class "Default")
      (node (ref "U13") (pin "27") (pinfunction "OSCI_27") (pintype "input"))
    )
    (net (code "326") (name "unconnected-(U13-OSCO-Pad28)") (class "Default")
      (node (ref "U13") (pin "28") (pinfunction "OSCO_28") (pintype "input"))
    )
    (net (code "327") (name "unconnected-(U13-~{CTS}-Pad11)") (class "Default")
      (node (ref "U13") (pin "11") (pinfunction "~{CTS}_11") (pintype "input"))
    )
    (net (code "328") (name "unconnected-(U13-~{DCD}-Pad10)") (class "Default")
      (node (ref "U13") (pin "10") (pinfunction "~{DCD}_10") (pintype "input"))
    )
    (net (code "329") (name "unconnected-(U13-~{DSR}-Pad9)") (class "Default")
      (node (ref "U13") (pin "9") (pinfunction "~{DSR}_9") (pintype "input"))
    )
    (net (code "330") (name "unconnected-(U13-~{DTR}-Pad2)") (class "Default")
      (node (ref "U13") (pin "2") (pinfunction "~{DTR}_2") (pintype "input"))
    )
    (net (code "331") (name "unconnected-(U13-~{RESET}-Pad19)") (class "Default")
      (node (ref "U13") (pin "19") (pinfunction "~{RESET}_19") (pintype "input"))
    )
    (net (code "332") (name "unconnected-(U13-~{RI}-Pad6)") (class "Default")
      (node (ref "U13") (pin "6") (pinfunction "~{RI}_6") (pintype "input"))
    )
    (net (code "333") (name "unconnected-(U13-~{RTS}-Pad3)") (class "Default")
      (node (ref "U13") (pin "3") (pinfunction "~{RTS}_3") (pintype "input"))
    )
    (net (code "334") (name "unconnected-(U14-CBUS2-Pad13)") (class "Default")
      (node (ref "U14") (pin "13") (pinfunction "CBUS2_13") (pintype "input"))
    )
    (net (code "335") (name "unconnected-(U14-CBUS3-Pad14)") (class "Default")
      (node (ref "U14") (pin "14") (pinfunction "CBUS3_14") (pintype "input"))
    )
    (net (code "336") (name "unconnected-(U14-CBUS4-Pad12)") (class "Default")
      (node (ref "U14") (pin "12") (pinfunction "CBUS4_12") (pintype "input"))
    )
    (net (code "337") (name "unconnected-(U14-OSCI-Pad27)") (class "Default")
      (node (ref "U14") (pin "27") (pinfunction "OSCI_27") (pintype "input"))
    )
    (net (code "338") (name "unconnected-(U14-OSCO-Pad28)") (class "Default")
      (node (ref "U14") (pin "28") (pinfunction "OSCO_28") (pintype "input"))
    )
    (net (code "339") (name "unconnected-(U14-~{CTS}-Pad11)") (class "Default")
      (node (ref "U14") (pin "11") (pinfunction "~{CTS}_11") (pintype "input"))
    )
    (net (code "340") (name "unconnected-(U14-~{DCD}-Pad10)") (class "Default")
      (node (ref "U14") (pin "10") (pinfunction "~{DCD}_10") (pintype "input"))
    )
    (net (code "341") (name "unconnected-(U14-~{DSR}-Pad9)") (class "Default")
      (node (ref "U14") (pin "9") (pinfunction "~{DSR}_9") (pintype "input"))
    )
    (net (code "342") (name "unconnected-(U14-~{DTR}-Pad2)") (class "Default")
      (node (ref "U14") (pin "2") (pinfunction "~{DTR}_2") (pintype "input"))
    )
    (net (code "343") (name "unconnected-(U14-~{RESET}-Pad19)") (class "Default")
      (node (ref "U14") (pin "19") (pinfunction "~{RESET}_19") (pintype "input"))
    )
    (net (code "344") (name "unconnected-(U14-~{RI}-Pad6)") (class "Default")
      (node (ref "U14") (pin "6") (pinfunction "~{RI}_6") (pintype "input"))
    )
    (net (code "345") (name "unconnected-(U14-~{RTS}-Pad3)") (class "Default")
      (node (ref "U14") (pin "3") (pinfunction "~{RTS}_3") (pintype "input"))
    )
    (net (code "346") (name "unconnected-(U15-CBUS2-Pad13)") (class "Default")
      (node (ref "U15") (pin "13") (pinfunction "CBUS2_13") (pintype "input"))
    )
    (net (code "347") (name "unconnected-(U15-CBUS3-Pad14)") (class "Default")
      (node (ref "U15") (pin "14") (pinfunction "CBUS3_14") (pintype "input"))
    )
    (net (code "348") (name "unconnected-(U15-CBUS4-Pad12)") (class "Default")
      (node (ref "U15") (pin "12") (pinfunction "CBUS4_12") (pintype "input"))
    )
    (net (code "349") (name "unconnected-(U15-OSCI-Pad27)") (class "Default")
      (node (ref "U15") (pin "27") (pinfunction "OSCI_27") (pintype "input"))
    )
    (net (code "350") (name "unconnected-(U15-OSCO-Pad28)") (class "Default")
      (node (ref "U15") (pin "28") (pinfunction "OSCO_28") (pintype "input"))
    )
    (net (code "351") (name "unconnected-(U15-~{CTS}-Pad11)") (class "Default")
      (node (ref "U15") (pin "11") (pinfunction "~{CTS}_11") (pintype "input"))
    )
    (net (code "352") (name "unconnected-(U15-~{DCD}-Pad10)") (class "Default")
      (node (ref "U15") (pin "10") (pinfunction "~{DCD}_10") (pintype "input"))
    )
    (net (code "353") (name "unconnected-(U15-~{DSR}-Pad9)") (class "Default")
      (node (ref "U15") (pin "9") (pinfunction "~{DSR}_9") (pintype "input"))
    )
    (net (code "354") (name "unconnected-(U15-~{DTR}-Pad2)") (class "Default")
      (node (ref "U15") (pin "2") (pinfunction "~{DTR}_2") (pintype "input"))
    )
    (net (code "355") (name "unconnected-(U15-~{RESET}-Pad19)") (class "Default")
      (node (ref "U15") (pin "19") (pinfunction "~{RESET}_19") (pintype "input"))
    )
    (net (code "356") (name "unconnected-(U15-~{RI}-Pad6)") (class "Default")
      (node (ref "U15") (pin "6") (pinfunction "~{RI}_6") (pintype "input"))
    )
    (net (code "357") (name "unconnected-(U15-~{RTS}-Pad3)") (class "Default")
      (node (ref "U15") (pin "3") (pinfunction "~{RTS}_3") (pintype "input"))
    )
    (net (code "358") (name "unconnected-(USB1-ID-Pad4)") (class "Default")
      (node (ref "USB1") (pin "4") (pinfunction "ID_4") (pintype "bidirectional"))
    )
    (net (code "359") (name "unconnected-(USB3-ID-Pad4)") (class "Default")
      (node (ref "USB3") (pin "4") (pinfunction "ID_4") (pintype "bidirectional"))
    )
  )
)
